# Cube-Panel.net
KiCad netlist of a schematic drawn in EAGLE
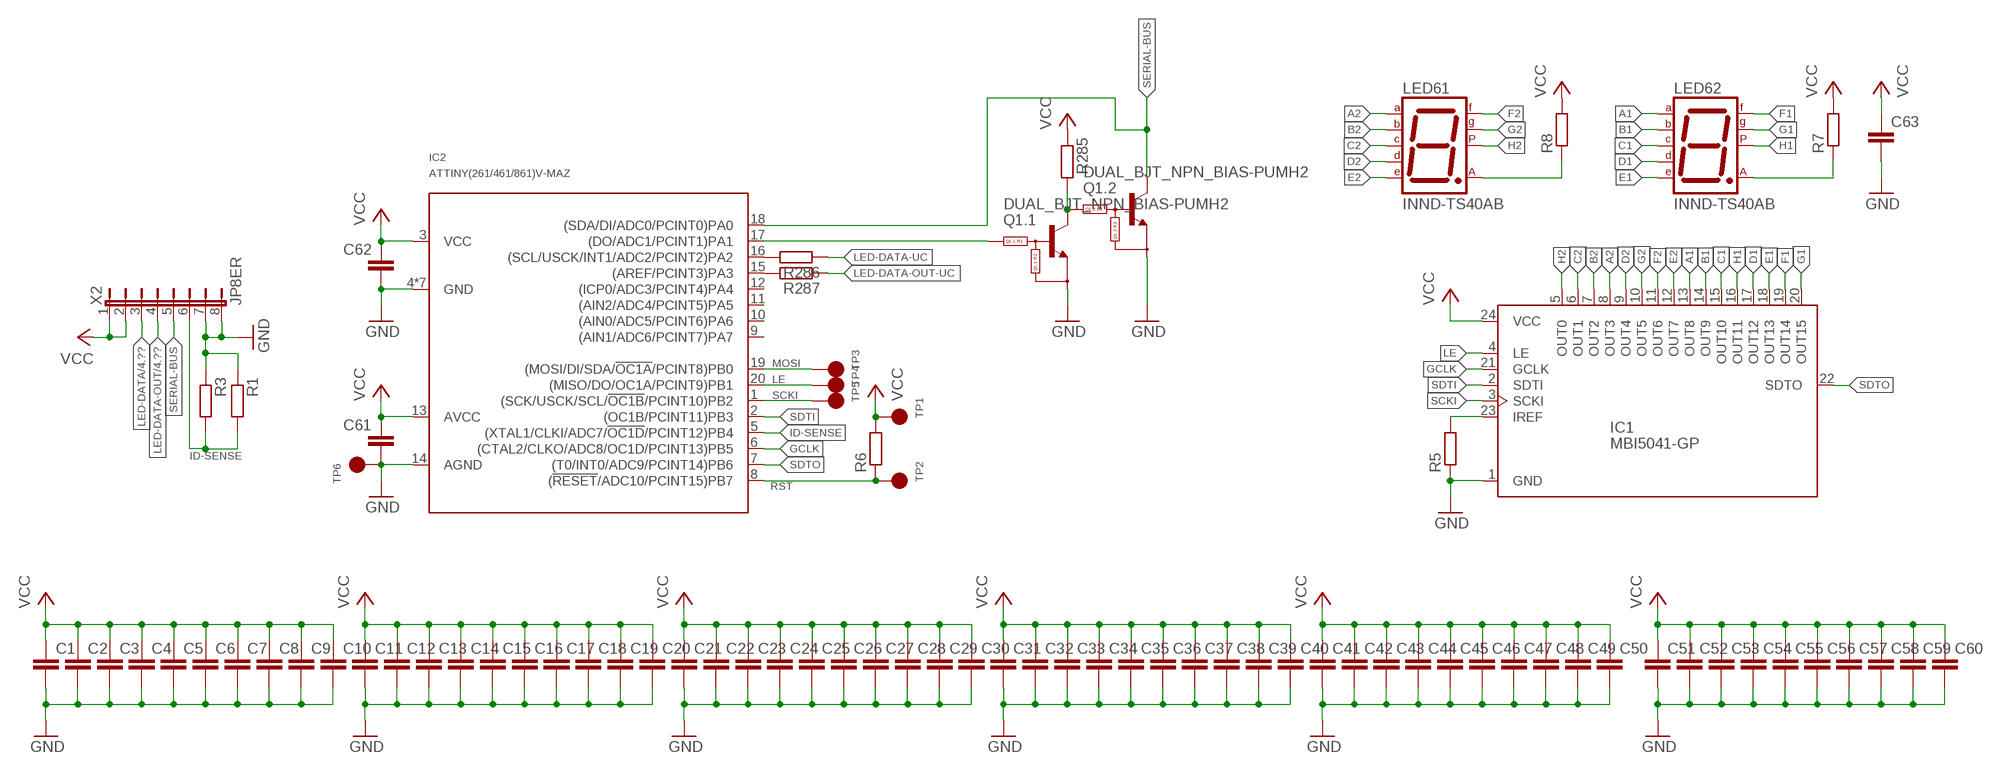
[diagram p0: schematic, sheet 1]
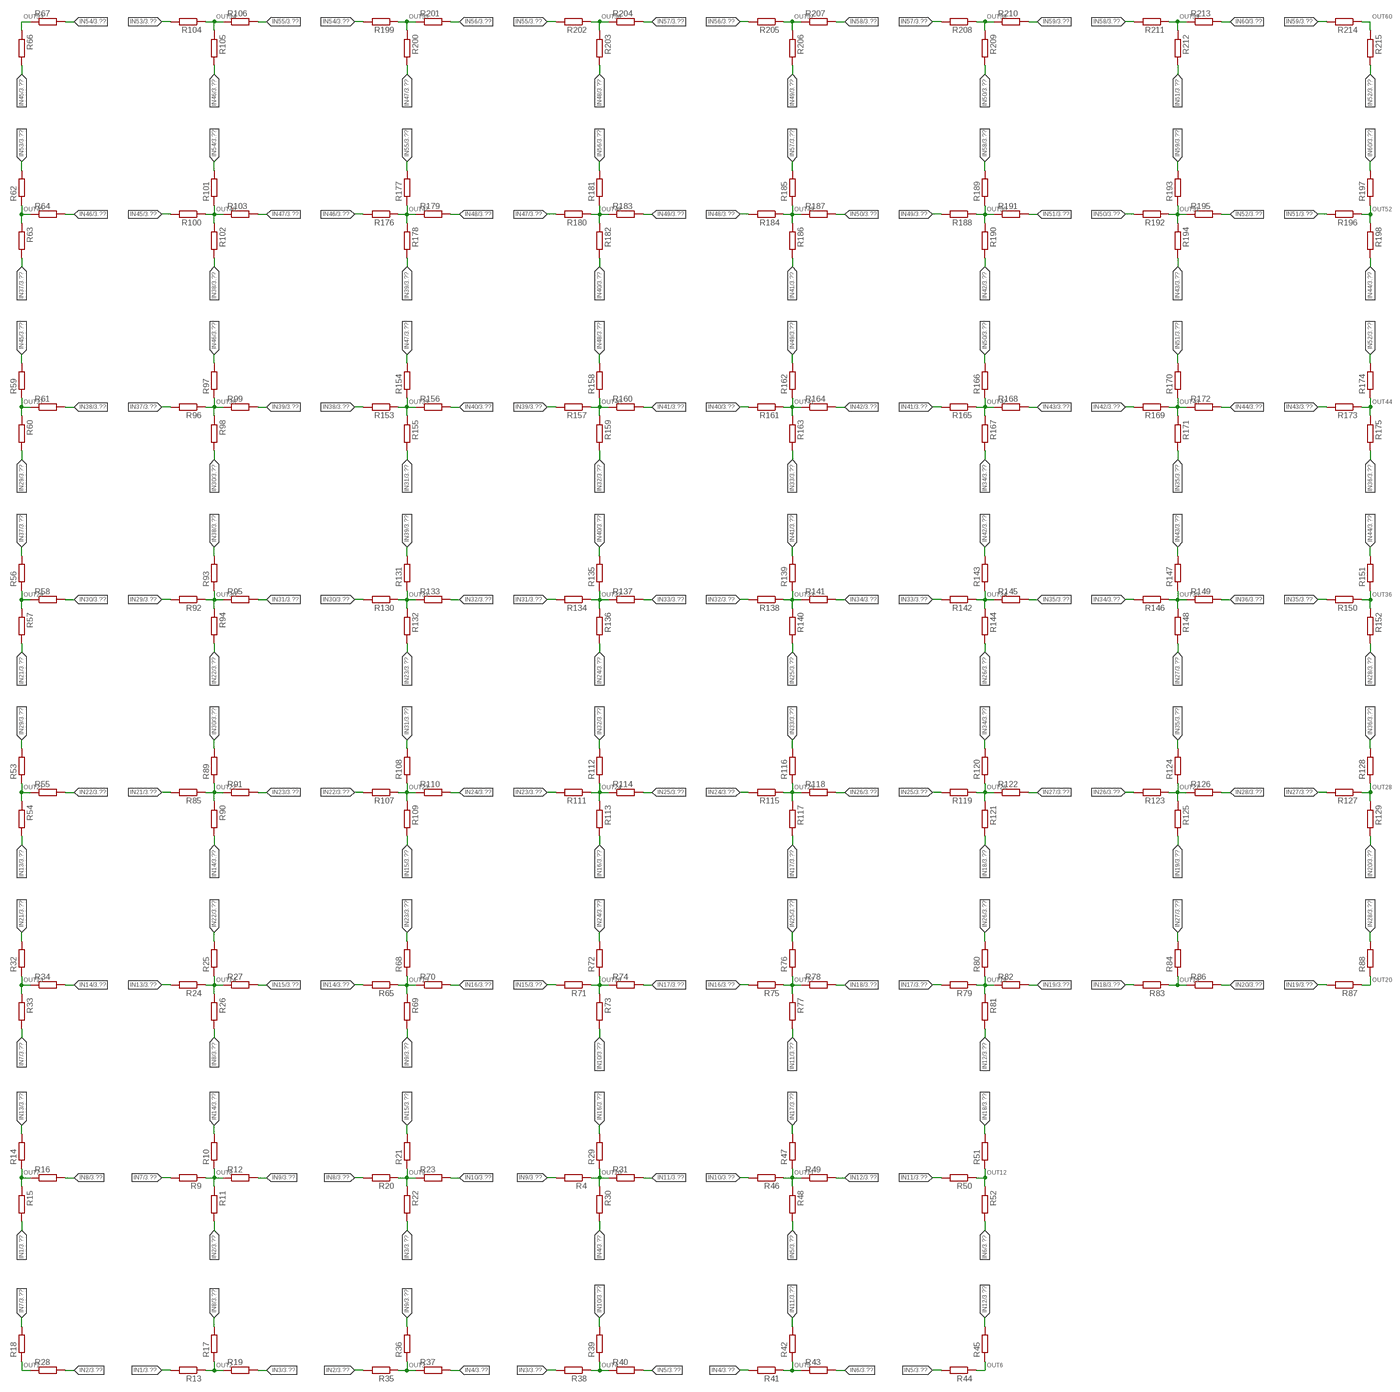
[diagram p1: schematic, sheet 2, overview]
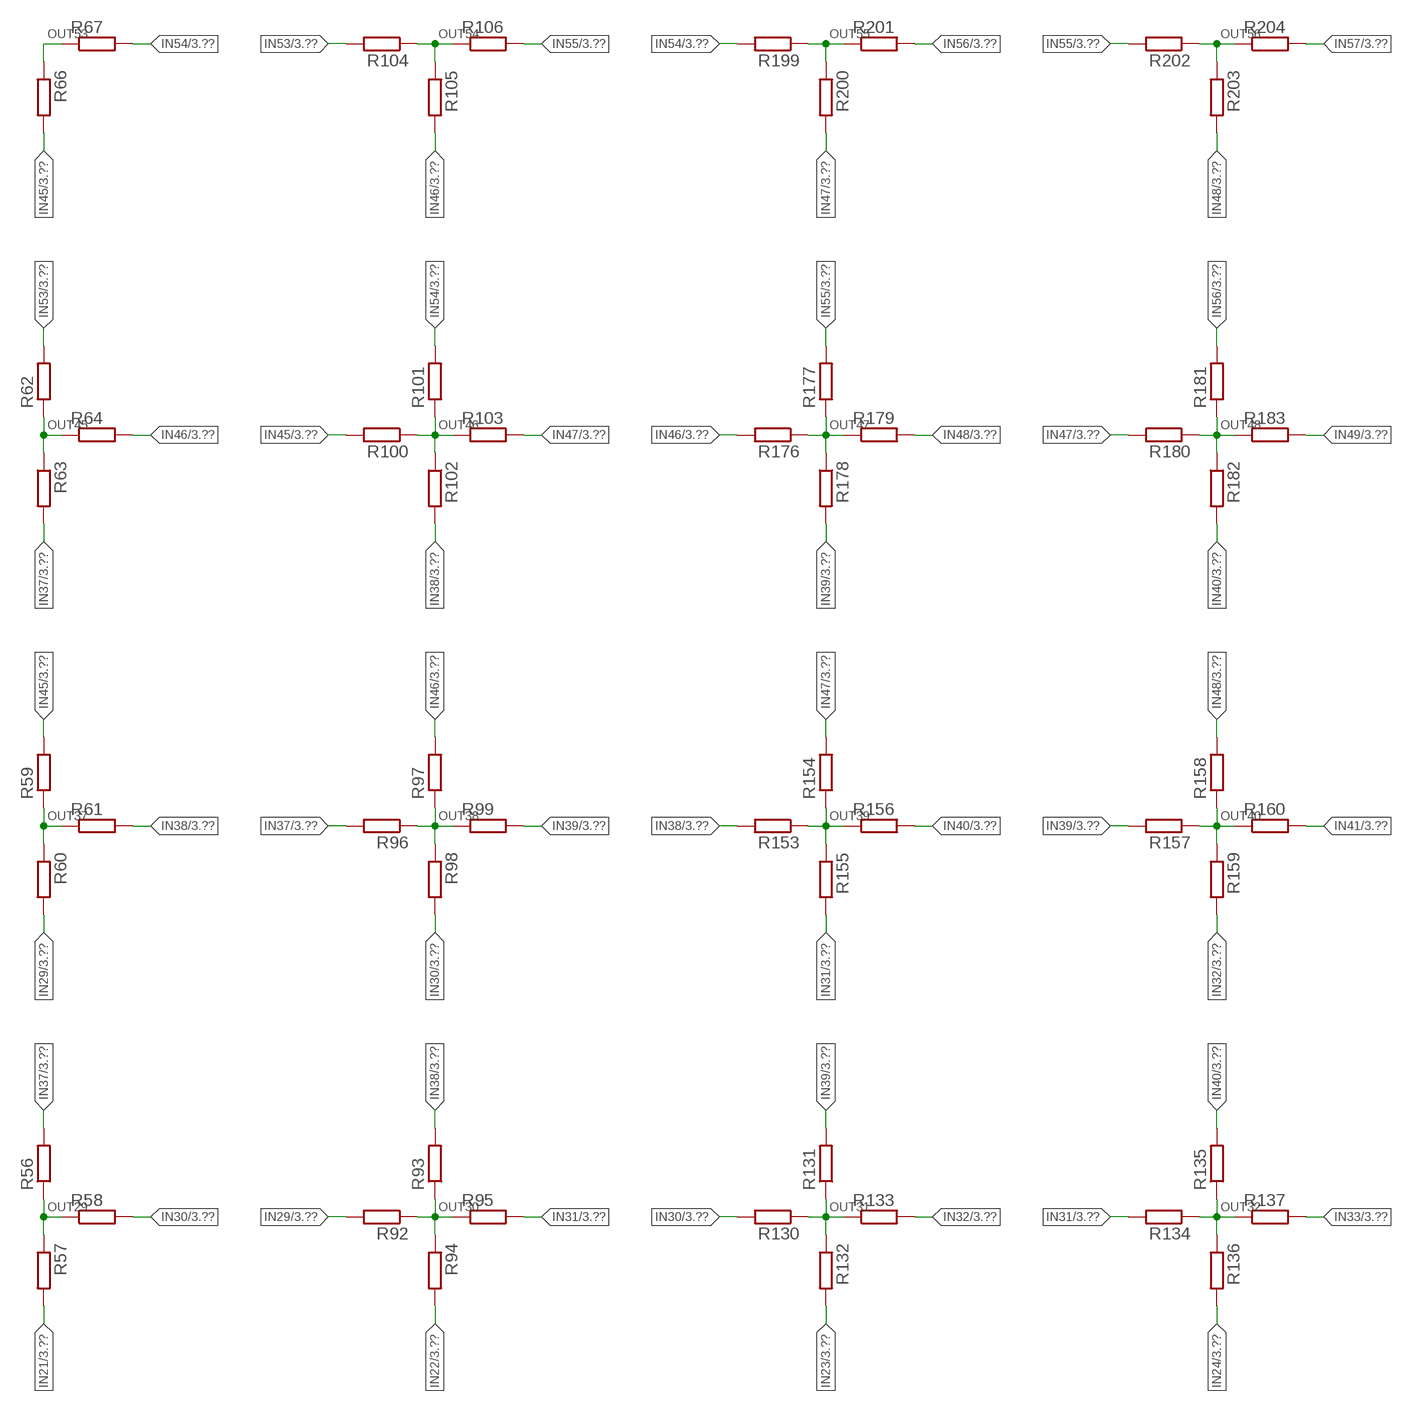
[diagram p2: schematic, sheet 2, part 1 of 4]
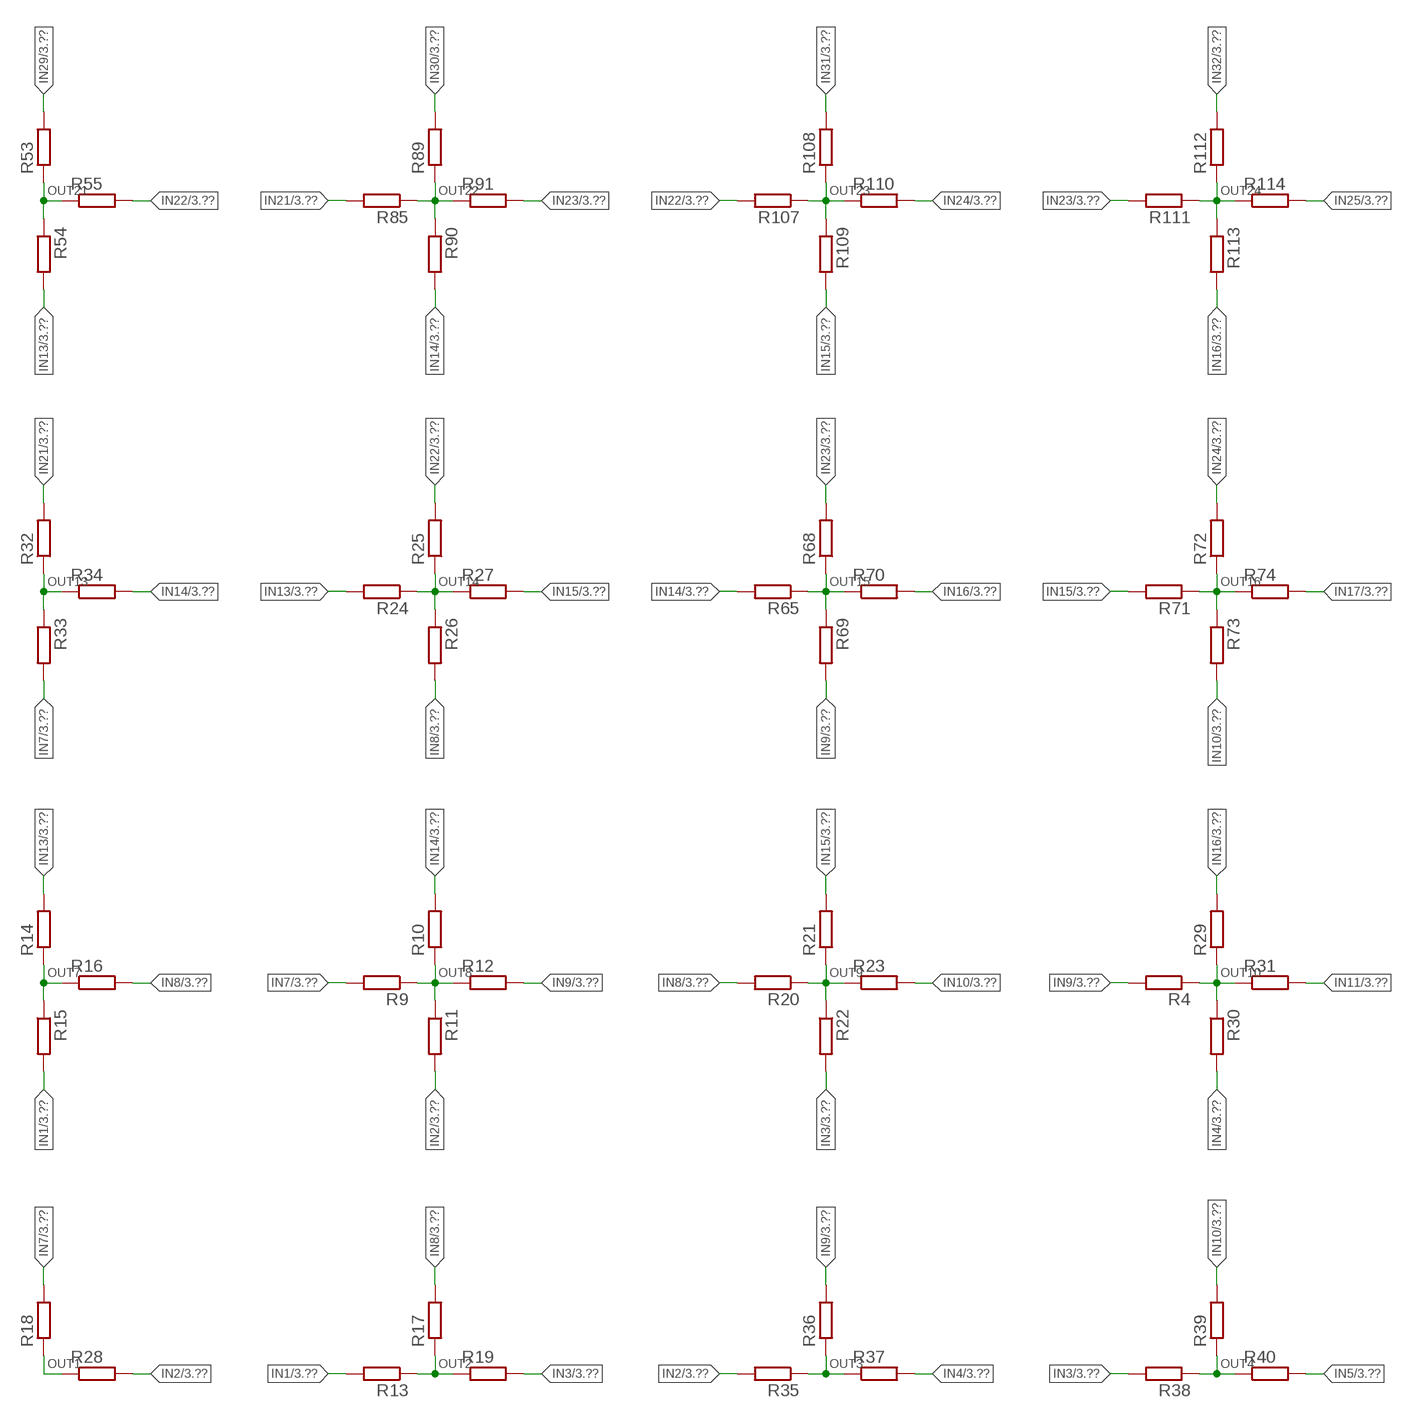
[diagram p3: schematic, sheet 2, part 2 of 4]
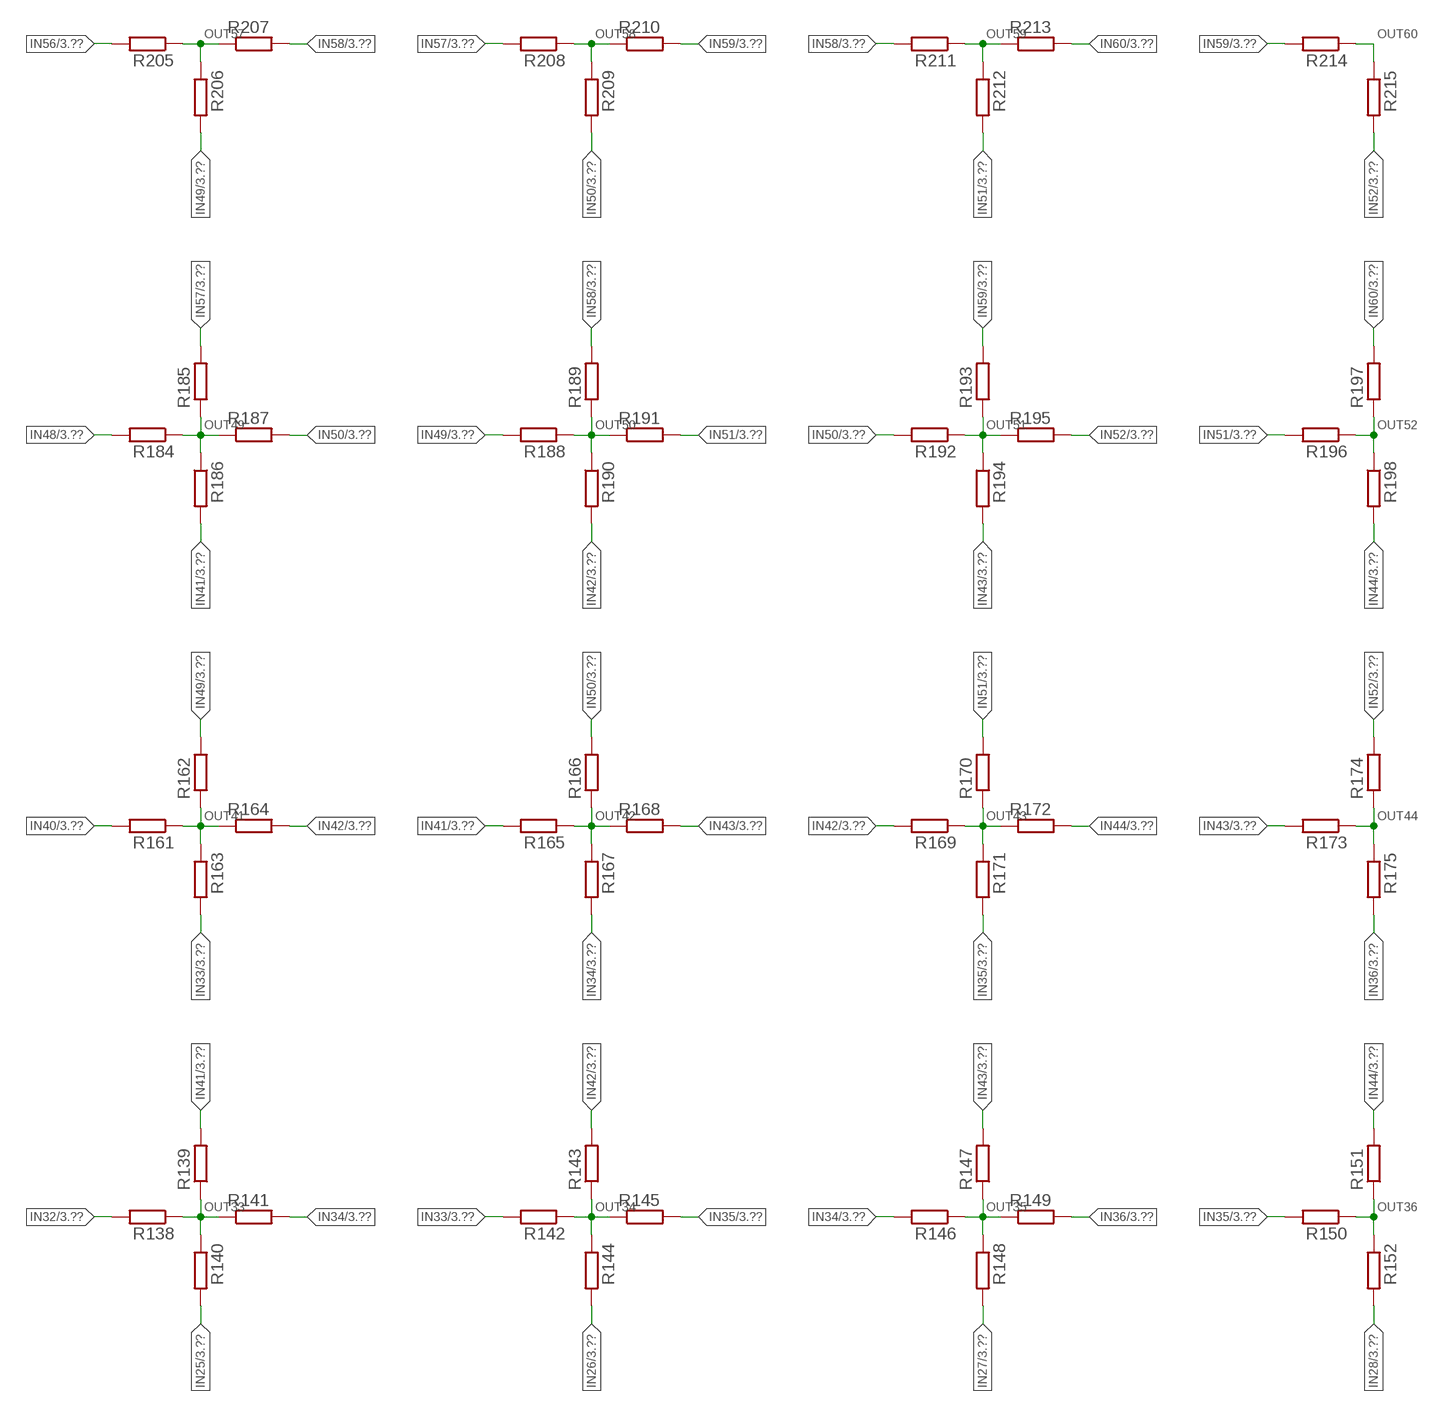
[diagram p4: schematic, sheet 2, part 3 of 4]
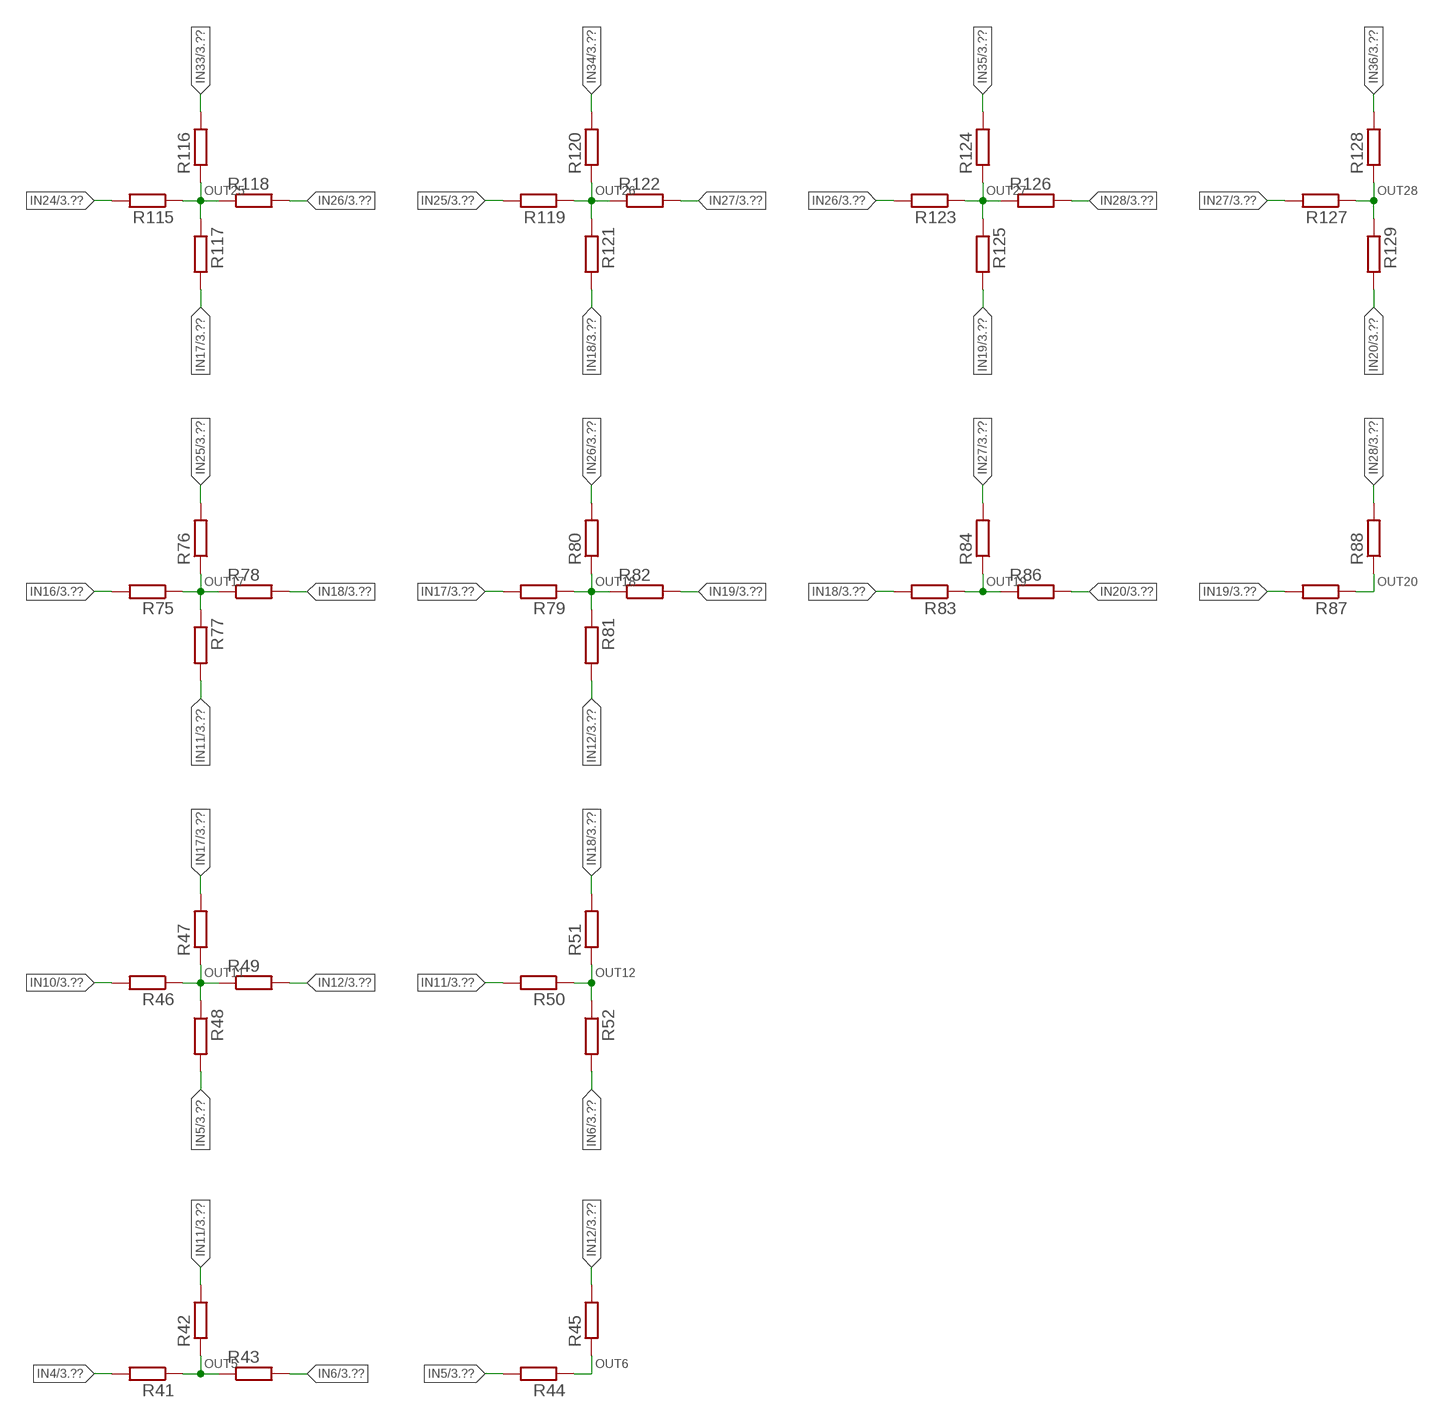
[diagram p5: schematic, sheet 2, part 4 of 4]
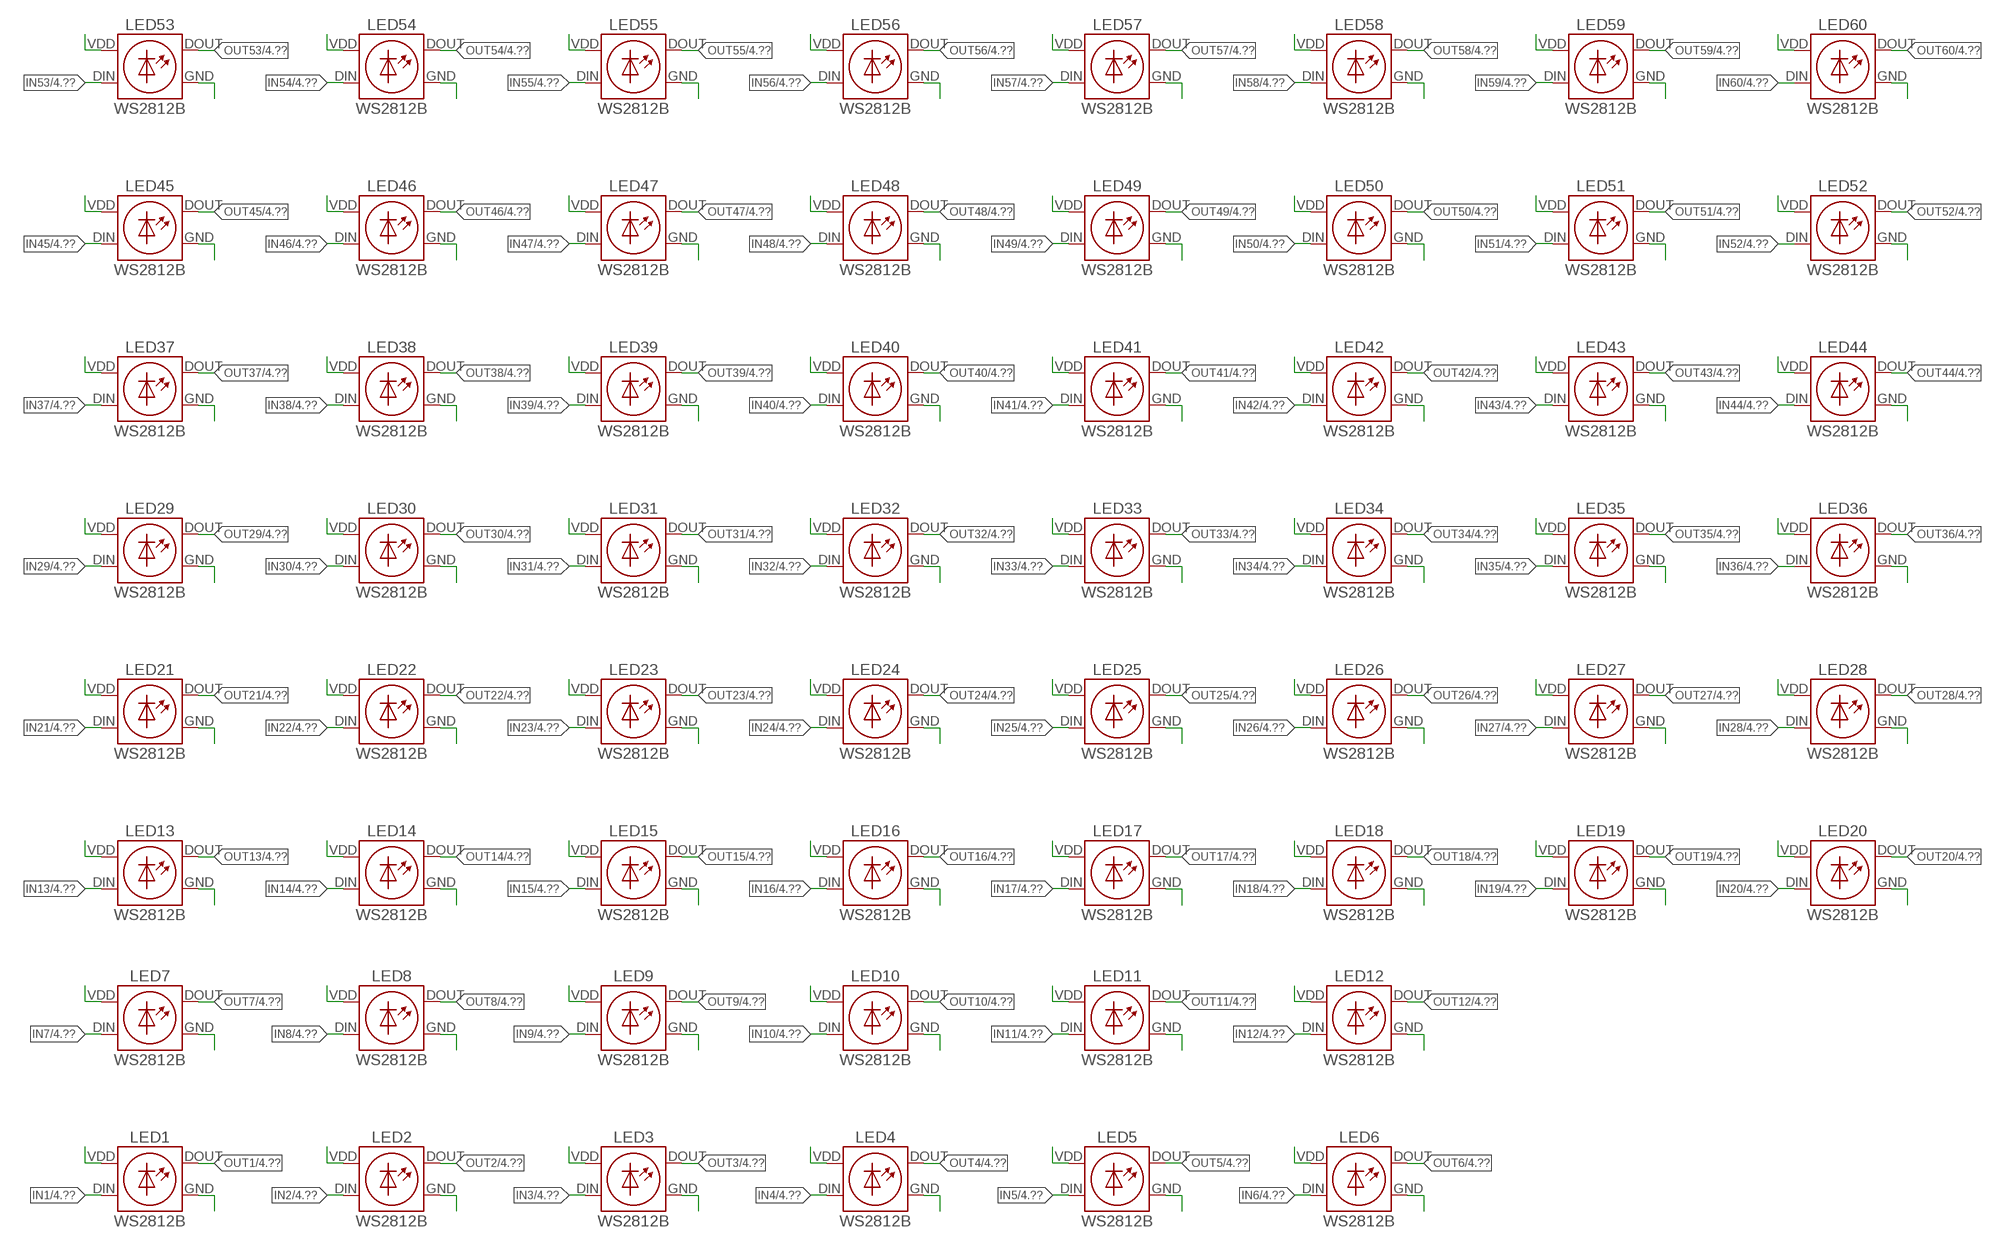
[diagram p6: schematic, sheet 3]
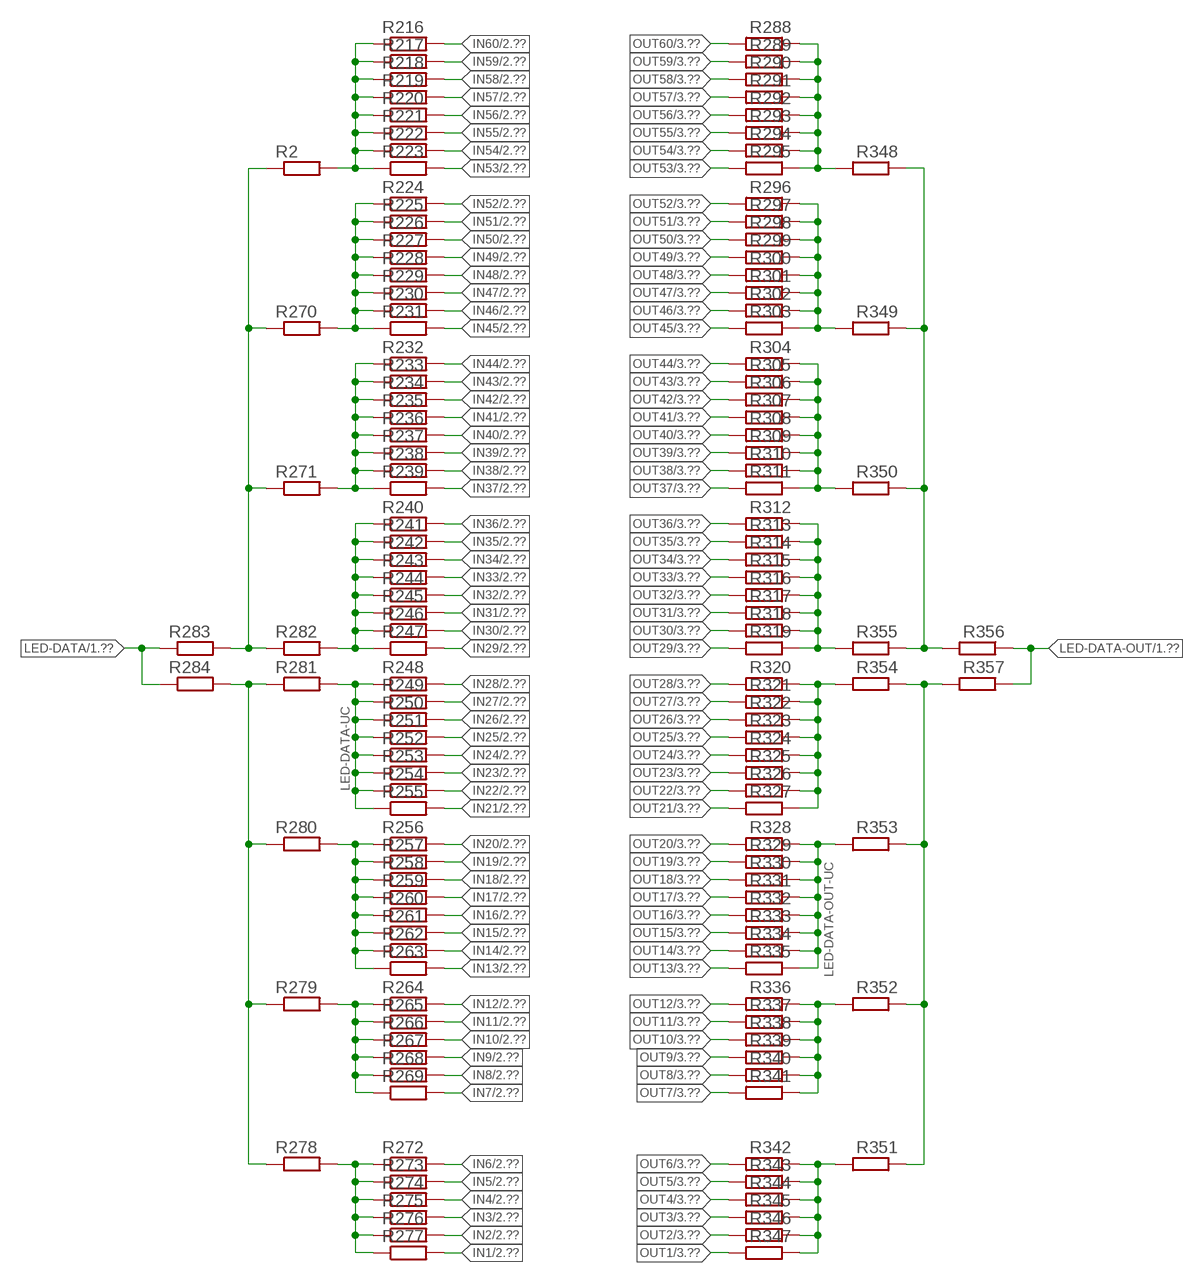
[diagram p7: schematic, sheet 4]

(export (version "E")
  (design (tool "Eeschema 10.0.6"))
  (components
    (comp (ref "R4")
      (value "WIDERSTAND-0603")
      (footprint "eagle-import:0603")
      (libsource (lib "eagle-import") (part "WIDERSTAND-0603"))
    )
    (comp (ref "R9")
      (value "WIDERSTAND-0603")
      (footprint "eagle-import:0603")
      (libsource (lib "eagle-import") (part "WIDERSTAND-0603"))
    )
    (comp (ref "R10")
      (value "WIDERSTAND-0603")
      (footprint "eagle-import:0603")
      (libsource (lib "eagle-import") (part "WIDERSTAND-0603"))
    )
    (comp (ref "R11")
      (value "WIDERSTAND-0603")
      (footprint "eagle-import:0603")
      (libsource (lib "eagle-import") (part "WIDERSTAND-0603"))
    )
    (comp (ref "R12")
      (value "WIDERSTAND-0603")
      (footprint "eagle-import:0603")
      (libsource (lib "eagle-import") (part "WIDERSTAND-0603"))
    )
    (comp (ref "R13")
      (value "WIDERSTAND-0603")
      (footprint "eagle-import:0603")
      (libsource (lib "eagle-import") (part "WIDERSTAND-0603"))
    )
    (comp (ref "R14")
      (value "WIDERSTAND-0603")
      (footprint "eagle-import:0603")
      (libsource (lib "eagle-import") (part "WIDERSTAND-0603"))
    )
    (comp (ref "R15")
      (value "WIDERSTAND-0603")
      (footprint "eagle-import:0603")
      (libsource (lib "eagle-import") (part "WIDERSTAND-0603"))
    )
    (comp (ref "R16")
      (value "WIDERSTAND-0603")
      (footprint "eagle-import:0603")
      (libsource (lib "eagle-import") (part "WIDERSTAND-0603"))
    )
    (comp (ref "R17")
      (value "WIDERSTAND-0603")
      (footprint "eagle-import:0603")
      (libsource (lib "eagle-import") (part "WIDERSTAND-0603"))
    )
    (comp (ref "R18")
      (value "WIDERSTAND-0603")
      (footprint "eagle-import:0603")
      (libsource (lib "eagle-import") (part "WIDERSTAND-0603"))
    )
    (comp (ref "R19")
      (value "WIDERSTAND-0603")
      (footprint "eagle-import:0603")
      (libsource (lib "eagle-import") (part "WIDERSTAND-0603"))
    )
    (comp (ref "R20")
      (value "WIDERSTAND-0603")
      (footprint "eagle-import:0603")
      (libsource (lib "eagle-import") (part "WIDERSTAND-0603"))
    )
    (comp (ref "R21")
      (value "WIDERSTAND-0603")
      (footprint "eagle-import:0603")
      (libsource (lib "eagle-import") (part "WIDERSTAND-0603"))
    )
    (comp (ref "R22")
      (value "WIDERSTAND-0603")
      (footprint "eagle-import:0603")
      (libsource (lib "eagle-import") (part "WIDERSTAND-0603"))
    )
    (comp (ref "R23")
      (value "WIDERSTAND-0603")
      (footprint "eagle-import:0603")
      (libsource (lib "eagle-import") (part "WIDERSTAND-0603"))
    )
    (comp (ref "R24")
      (value "WIDERSTAND-0603")
      (footprint "eagle-import:0603")
      (libsource (lib "eagle-import") (part "WIDERSTAND-0603"))
    )
    (comp (ref "R25")
      (value "WIDERSTAND-0603")
      (footprint "eagle-import:0603")
      (libsource (lib "eagle-import") (part "WIDERSTAND-0603"))
    )
    (comp (ref "R26")
      (value "WIDERSTAND-0603")
      (footprint "eagle-import:0603")
      (libsource (lib "eagle-import") (part "WIDERSTAND-0603"))
    )
    (comp (ref "R27")
      (value "WIDERSTAND-0603")
      (footprint "eagle-import:0603")
      (libsource (lib "eagle-import") (part "WIDERSTAND-0603"))
    )
    (comp (ref "R28")
      (value "WIDERSTAND-0603")
      (footprint "eagle-import:0603")
      (libsource (lib "eagle-import") (part "WIDERSTAND-0603"))
    )
    (comp (ref "R29")
      (value "WIDERSTAND-0603")
      (footprint "eagle-import:0603")
      (libsource (lib "eagle-import") (part "WIDERSTAND-0603"))
    )
    (comp (ref "R30")
      (value "WIDERSTAND-0603")
      (footprint "eagle-import:0603")
      (libsource (lib "eagle-import") (part "WIDERSTAND-0603"))
    )
    (comp (ref "R31")
      (value "WIDERSTAND-0603")
      (footprint "eagle-import:0603")
      (libsource (lib "eagle-import") (part "WIDERSTAND-0603"))
    )
    (comp (ref "R32")
      (value "WIDERSTAND-0603")
      (footprint "eagle-import:0603")
      (libsource (lib "eagle-import") (part "WIDERSTAND-0603"))
    )
    (comp (ref "R33")
      (value "WIDERSTAND-0603")
      (footprint "eagle-import:0603")
      (libsource (lib "eagle-import") (part "WIDERSTAND-0603"))
    )
    (comp (ref "R34")
      (value "WIDERSTAND-0603")
      (footprint "eagle-import:0603")
      (libsource (lib "eagle-import") (part "WIDERSTAND-0603"))
    )
    (comp (ref "R35")
      (value "WIDERSTAND-0603")
      (footprint "eagle-import:0603")
      (libsource (lib "eagle-import") (part "WIDERSTAND-0603"))
    )
    (comp (ref "R36")
      (value "WIDERSTAND-0603")
      (footprint "eagle-import:0603")
      (libsource (lib "eagle-import") (part "WIDERSTAND-0603"))
    )
    (comp (ref "R37")
      (value "WIDERSTAND-0603")
      (footprint "eagle-import:0603")
      (libsource (lib "eagle-import") (part "WIDERSTAND-0603"))
    )
    (comp (ref "R38")
      (value "WIDERSTAND-0603")
      (footprint "eagle-import:0603")
      (libsource (lib "eagle-import") (part "WIDERSTAND-0603"))
    )
    (comp (ref "R39")
      (value "WIDERSTAND-0603")
      (footprint "eagle-import:0603")
      (libsource (lib "eagle-import") (part "WIDERSTAND-0603"))
    )
    (comp (ref "R40")
      (value "WIDERSTAND-0603")
      (footprint "eagle-import:0603")
      (libsource (lib "eagle-import") (part "WIDERSTAND-0603"))
    )
    (comp (ref "R41")
      (value "WIDERSTAND-0603")
      (footprint "eagle-import:0603")
      (libsource (lib "eagle-import") (part "WIDERSTAND-0603"))
    )
    (comp (ref "R42")
      (value "WIDERSTAND-0603")
      (footprint "eagle-import:0603")
      (libsource (lib "eagle-import") (part "WIDERSTAND-0603"))
    )
    (comp (ref "R43")
      (value "WIDERSTAND-0603")
      (footprint "eagle-import:0603")
      (libsource (lib "eagle-import") (part "WIDERSTAND-0603"))
    )
    (comp (ref "R44")
      (value "WIDERSTAND-0603")
      (footprint "eagle-import:0603")
      (libsource (lib "eagle-import") (part "WIDERSTAND-0603"))
    )
    (comp (ref "R45")
      (value "WIDERSTAND-0603")
      (footprint "eagle-import:0603")
      (libsource (lib "eagle-import") (part "WIDERSTAND-0603"))
    )
    (comp (ref "R46")
      (value "WIDERSTAND-0603")
      (footprint "eagle-import:0603")
      (libsource (lib "eagle-import") (part "WIDERSTAND-0603"))
    )
    (comp (ref "R47")
      (value "WIDERSTAND-0603")
      (footprint "eagle-import:0603")
      (libsource (lib "eagle-import") (part "WIDERSTAND-0603"))
    )
    (comp (ref "R48")
      (value "WIDERSTAND-0603")
      (footprint "eagle-import:0603")
      (libsource (lib "eagle-import") (part "WIDERSTAND-0603"))
    )
    (comp (ref "R49")
      (value "WIDERSTAND-0603")
      (footprint "eagle-import:0603")
      (libsource (lib "eagle-import") (part "WIDERSTAND-0603"))
    )
    (comp (ref "R50")
      (value "WIDERSTAND-0603")
      (footprint "eagle-import:0603")
      (libsource (lib "eagle-import") (part "WIDERSTAND-0603"))
    )
    (comp (ref "R51")
      (value "WIDERSTAND-0603")
      (footprint "eagle-import:0603")
      (libsource (lib "eagle-import") (part "WIDERSTAND-0603"))
    )
    (comp (ref "R52")
      (value "WIDERSTAND-0603")
      (footprint "eagle-import:0603")
      (libsource (lib "eagle-import") (part "WIDERSTAND-0603"))
    )
    (comp (ref "R53")
      (value "WIDERSTAND-0603")
      (footprint "eagle-import:0603")
      (libsource (lib "eagle-import") (part "WIDERSTAND-0603"))
    )
    (comp (ref "R54")
      (value "WIDERSTAND-0603")
      (footprint "eagle-import:0603")
      (libsource (lib "eagle-import") (part "WIDERSTAND-0603"))
    )
    (comp (ref "R55")
      (value "WIDERSTAND-0603")
      (footprint "eagle-import:0603")
      (libsource (lib "eagle-import") (part "WIDERSTAND-0603"))
    )
    (comp (ref "R56")
      (value "WIDERSTAND-0603")
      (footprint "eagle-import:0603")
      (libsource (lib "eagle-import") (part "WIDERSTAND-0603"))
    )
    (comp (ref "R57")
      (value "WIDERSTAND-0603")
      (footprint "eagle-import:0603")
      (libsource (lib "eagle-import") (part "WIDERSTAND-0603"))
    )
    (comp (ref "R58")
      (value "WIDERSTAND-0603")
      (footprint "eagle-import:0603")
      (libsource (lib "eagle-import") (part "WIDERSTAND-0603"))
    )
    (comp (ref "R59")
      (value "WIDERSTAND-0603")
      (footprint "eagle-import:0603")
      (libsource (lib "eagle-import") (part "WIDERSTAND-0603"))
    )
    (comp (ref "R60")
      (value "WIDERSTAND-0603")
      (footprint "eagle-import:0603")
      (libsource (lib "eagle-import") (part "WIDERSTAND-0603"))
    )
    (comp (ref "R61")
      (value "WIDERSTAND-0603")
      (footprint "eagle-import:0603")
      (libsource (lib "eagle-import") (part "WIDERSTAND-0603"))
    )
    (comp (ref "R62")
      (value "WIDERSTAND-0603")
      (footprint "eagle-import:0603")
      (libsource (lib "eagle-import") (part "WIDERSTAND-0603"))
    )
    (comp (ref "R63")
      (value "WIDERSTAND-0603")
      (footprint "eagle-import:0603")
      (libsource (lib "eagle-import") (part "WIDERSTAND-0603"))
    )
    (comp (ref "R64")
      (value "WIDERSTAND-0603")
      (footprint "eagle-import:0603")
      (libsource (lib "eagle-import") (part "WIDERSTAND-0603"))
    )
    (comp (ref "R65")
      (value "WIDERSTAND-0603")
      (footprint "eagle-import:0603")
      (libsource (lib "eagle-import") (part "WIDERSTAND-0603"))
    )
    (comp (ref "R66")
      (value "WIDERSTAND-0603")
      (footprint "eagle-import:0603")
      (libsource (lib "eagle-import") (part "WIDERSTAND-0603"))
    )
    (comp (ref "R67")
      (value "WIDERSTAND-0603")
      (footprint "eagle-import:0603")
      (libsource (lib "eagle-import") (part "WIDERSTAND-0603"))
    )
    (comp (ref "R68")
      (value "WIDERSTAND-0603")
      (footprint "eagle-import:0603")
      (libsource (lib "eagle-import") (part "WIDERSTAND-0603"))
    )
    (comp (ref "R69")
      (value "WIDERSTAND-0603")
      (footprint "eagle-import:0603")
      (libsource (lib "eagle-import") (part "WIDERSTAND-0603"))
    )
    (comp (ref "R70")
      (value "WIDERSTAND-0603")
      (footprint "eagle-import:0603")
      (libsource (lib "eagle-import") (part "WIDERSTAND-0603"))
    )
    (comp (ref "R71")
      (value "WIDERSTAND-0603")
      (footprint "eagle-import:0603")
      (libsource (lib "eagle-import") (part "WIDERSTAND-0603"))
    )
    (comp (ref "R72")
      (value "WIDERSTAND-0603")
      (footprint "eagle-import:0603")
      (libsource (lib "eagle-import") (part "WIDERSTAND-0603"))
    )
    (comp (ref "R73")
      (value "WIDERSTAND-0603")
      (footprint "eagle-import:0603")
      (libsource (lib "eagle-import") (part "WIDERSTAND-0603"))
    )
    (comp (ref "R74")
      (value "WIDERSTAND-0603")
      (footprint "eagle-import:0603")
      (libsource (lib "eagle-import") (part "WIDERSTAND-0603"))
    )
    (comp (ref "R75")
      (value "WIDERSTAND-0603")
      (footprint "eagle-import:0603")
      (libsource (lib "eagle-import") (part "WIDERSTAND-0603"))
    )
    (comp (ref "R76")
      (value "WIDERSTAND-0603")
      (footprint "eagle-import:0603")
      (libsource (lib "eagle-import") (part "WIDERSTAND-0603"))
    )
    (comp (ref "R77")
      (value "WIDERSTAND-0603")
      (footprint "eagle-import:0603")
      (libsource (lib "eagle-import") (part "WIDERSTAND-0603"))
    )
    (comp (ref "R78")
      (value "WIDERSTAND-0603")
      (footprint "eagle-import:0603")
      (libsource (lib "eagle-import") (part "WIDERSTAND-0603"))
    )
    (comp (ref "R79")
      (value "WIDERSTAND-0603")
      (footprint "eagle-import:0603")
      (libsource (lib "eagle-import") (part "WIDERSTAND-0603"))
    )
    (comp (ref "R80")
      (value "WIDERSTAND-0603")
      (footprint "eagle-import:0603")
      (libsource (lib "eagle-import") (part "WIDERSTAND-0603"))
    )
    (comp (ref "R81")
      (value "WIDERSTAND-0603")
      (footprint "eagle-import:0603")
      (libsource (lib "eagle-import") (part "WIDERSTAND-0603"))
    )
    (comp (ref "R82")
      (value "WIDERSTAND-0603")
      (footprint "eagle-import:0603")
      (libsource (lib "eagle-import") (part "WIDERSTAND-0603"))
    )
    (comp (ref "R83")
      (value "WIDERSTAND-0603")
      (footprint "eagle-import:0603")
      (libsource (lib "eagle-import") (part "WIDERSTAND-0603"))
    )
    (comp (ref "R84")
      (value "WIDERSTAND-0603")
      (footprint "eagle-import:0603")
      (libsource (lib "eagle-import") (part "WIDERSTAND-0603"))
    )
    (comp (ref "R85")
      (value "WIDERSTAND-0603")
      (footprint "eagle-import:0603")
      (libsource (lib "eagle-import") (part "WIDERSTAND-0603"))
    )
    (comp (ref "R86")
      (value "WIDERSTAND-0603")
      (footprint "eagle-import:0603")
      (libsource (lib "eagle-import") (part "WIDERSTAND-0603"))
    )
    (comp (ref "R87")
      (value "WIDERSTAND-0603")
      (footprint "eagle-import:0603")
      (libsource (lib "eagle-import") (part "WIDERSTAND-0603"))
    )
    (comp (ref "R88")
      (value "WIDERSTAND-0603")
      (footprint "eagle-import:0603")
      (libsource (lib "eagle-import") (part "WIDERSTAND-0603"))
    )
    (comp (ref "R89")
      (value "WIDERSTAND-0603")
      (footprint "eagle-import:0603")
      (libsource (lib "eagle-import") (part "WIDERSTAND-0603"))
    )
    (comp (ref "R90")
      (value "WIDERSTAND-0603")
      (footprint "eagle-import:0603")
      (libsource (lib "eagle-import") (part "WIDERSTAND-0603"))
    )
    (comp (ref "R91")
      (value "WIDERSTAND-0603")
      (footprint "eagle-import:0603")
      (libsource (lib "eagle-import") (part "WIDERSTAND-0603"))
    )
    (comp (ref "R92")
      (value "WIDERSTAND-0603")
      (footprint "eagle-import:0603")
      (libsource (lib "eagle-import") (part "WIDERSTAND-0603"))
    )
    (comp (ref "R93")
      (value "WIDERSTAND-0603")
      (footprint "eagle-import:0603")
      (libsource (lib "eagle-import") (part "WIDERSTAND-0603"))
    )
    (comp (ref "R94")
      (value "WIDERSTAND-0603")
      (footprint "eagle-import:0603")
      (libsource (lib "eagle-import") (part "WIDERSTAND-0603"))
    )
    (comp (ref "R95")
      (value "WIDERSTAND-0603")
      (footprint "eagle-import:0603")
      (libsource (lib "eagle-import") (part "WIDERSTAND-0603"))
    )
    (comp (ref "R96")
      (value "WIDERSTAND-0603")
      (footprint "eagle-import:0603")
      (libsource (lib "eagle-import") (part "WIDERSTAND-0603"))
    )
    (comp (ref "R97")
      (value "WIDERSTAND-0603")
      (footprint "eagle-import:0603")
      (libsource (lib "eagle-import") (part "WIDERSTAND-0603"))
    )
    (comp (ref "R98")
      (value "WIDERSTAND-0603")
      (footprint "eagle-import:0603")
      (libsource (lib "eagle-import") (part "WIDERSTAND-0603"))
    )
    (comp (ref "R99")
      (value "WIDERSTAND-0603")
      (footprint "eagle-import:0603")
      (libsource (lib "eagle-import") (part "WIDERSTAND-0603"))
    )
    (comp (ref "R100")
      (value "WIDERSTAND-0603")
      (footprint "eagle-import:0603")
      (libsource (lib "eagle-import") (part "WIDERSTAND-0603"))
    )
    (comp (ref "R101")
      (value "WIDERSTAND-0603")
      (footprint "eagle-import:0603")
      (libsource (lib "eagle-import") (part "WIDERSTAND-0603"))
    )
    (comp (ref "R102")
      (value "WIDERSTAND-0603")
      (footprint "eagle-import:0603")
      (libsource (lib "eagle-import") (part "WIDERSTAND-0603"))
    )
    (comp (ref "R103")
      (value "WIDERSTAND-0603")
      (footprint "eagle-import:0603")
      (libsource (lib "eagle-import") (part "WIDERSTAND-0603"))
    )
    (comp (ref "R104")
      (value "WIDERSTAND-0603")
      (footprint "eagle-import:0603")
      (libsource (lib "eagle-import") (part "WIDERSTAND-0603"))
    )
    (comp (ref "R105")
      (value "WIDERSTAND-0603")
      (footprint "eagle-import:0603")
      (libsource (lib "eagle-import") (part "WIDERSTAND-0603"))
    )
    (comp (ref "R106")
      (value "WIDERSTAND-0603")
      (footprint "eagle-import:0603")
      (libsource (lib "eagle-import") (part "WIDERSTAND-0603"))
    )
    (comp (ref "R107")
      (value "WIDERSTAND-0603")
      (footprint "eagle-import:0603")
      (libsource (lib "eagle-import") (part "WIDERSTAND-0603"))
    )
    (comp (ref "R108")
      (value "WIDERSTAND-0603")
      (footprint "eagle-import:0603")
      (libsource (lib "eagle-import") (part "WIDERSTAND-0603"))
    )
    (comp (ref "R109")
      (value "WIDERSTAND-0603")
      (footprint "eagle-import:0603")
      (libsource (lib "eagle-import") (part "WIDERSTAND-0603"))
    )
    (comp (ref "R110")
      (value "WIDERSTAND-0603")
      (footprint "eagle-import:0603")
      (libsource (lib "eagle-import") (part "WIDERSTAND-0603"))
    )
    (comp (ref "R111")
      (value "WIDERSTAND-0603")
      (footprint "eagle-import:0603")
      (libsource (lib "eagle-import") (part "WIDERSTAND-0603"))
    )
    (comp (ref "R112")
      (value "WIDERSTAND-0603")
      (footprint "eagle-import:0603")
      (libsource (lib "eagle-import") (part "WIDERSTAND-0603"))
    )
    (comp (ref "R113")
      (value "WIDERSTAND-0603")
      (footprint "eagle-import:0603")
      (libsource (lib "eagle-import") (part "WIDERSTAND-0603"))
    )
    (comp (ref "R114")
      (value "WIDERSTAND-0603")
      (footprint "eagle-import:0603")
      (libsource (lib "eagle-import") (part "WIDERSTAND-0603"))
    )
    (comp (ref "R115")
      (value "WIDERSTAND-0603")
      (footprint "eagle-import:0603")
      (libsource (lib "eagle-import") (part "WIDERSTAND-0603"))
    )
    (comp (ref "R116")
      (value "WIDERSTAND-0603")
      (footprint "eagle-import:0603")
      (libsource (lib "eagle-import") (part "WIDERSTAND-0603"))
    )
    (comp (ref "R117")
      (value "WIDERSTAND-0603")
      (footprint "eagle-import:0603")
      (libsource (lib "eagle-import") (part "WIDERSTAND-0603"))
    )
    (comp (ref "R118")
      (value "WIDERSTAND-0603")
      (footprint "eagle-import:0603")
      (libsource (lib "eagle-import") (part "WIDERSTAND-0603"))
    )
    (comp (ref "R119")
      (value "WIDERSTAND-0603")
      (footprint "eagle-import:0603")
      (libsource (lib "eagle-import") (part "WIDERSTAND-0603"))
    )
    (comp (ref "R120")
      (value "WIDERSTAND-0603")
      (footprint "eagle-import:0603")
      (libsource (lib "eagle-import") (part "WIDERSTAND-0603"))
    )
    (comp (ref "R121")
      (value "WIDERSTAND-0603")
      (footprint "eagle-import:0603")
      (libsource (lib "eagle-import") (part "WIDERSTAND-0603"))
    )
    (comp (ref "R122")
      (value "WIDERSTAND-0603")
      (footprint "eagle-import:0603")
      (libsource (lib "eagle-import") (part "WIDERSTAND-0603"))
    )
    (comp (ref "R123")
      (value "WIDERSTAND-0603")
      (footprint "eagle-import:0603")
      (libsource (lib "eagle-import") (part "WIDERSTAND-0603"))
    )
    (comp (ref "R124")
      (value "WIDERSTAND-0603")
      (footprint "eagle-import:0603")
      (libsource (lib "eagle-import") (part "WIDERSTAND-0603"))
    )
    (comp (ref "R125")
      (value "WIDERSTAND-0603")
      (footprint "eagle-import:0603")
      (libsource (lib "eagle-import") (part "WIDERSTAND-0603"))
    )
    (comp (ref "R126")
      (value "WIDERSTAND-0603")
      (footprint "eagle-import:0603")
      (libsource (lib "eagle-import") (part "WIDERSTAND-0603"))
    )
    (comp (ref "R127")
      (value "WIDERSTAND-0603")
      (footprint "eagle-import:0603")
      (libsource (lib "eagle-import") (part "WIDERSTAND-0603"))
    )
    (comp (ref "R128")
      (value "WIDERSTAND-0603")
      (footprint "eagle-import:0603")
      (libsource (lib "eagle-import") (part "WIDERSTAND-0603"))
    )
    (comp (ref "R129")
      (value "WIDERSTAND-0603")
      (footprint "eagle-import:0603")
      (libsource (lib "eagle-import") (part "WIDERSTAND-0603"))
    )
    (comp (ref "R130")
      (value "WIDERSTAND-0603")
      (footprint "eagle-import:0603")
      (libsource (lib "eagle-import") (part "WIDERSTAND-0603"))
    )
    (comp (ref "R131")
      (value "WIDERSTAND-0603")
      (footprint "eagle-import:0603")
      (libsource (lib "eagle-import") (part "WIDERSTAND-0603"))
    )
    (comp (ref "R132")
      (value "WIDERSTAND-0603")
      (footprint "eagle-import:0603")
      (libsource (lib "eagle-import") (part "WIDERSTAND-0603"))
    )
    (comp (ref "R133")
      (value "WIDERSTAND-0603")
      (footprint "eagle-import:0603")
      (libsource (lib "eagle-import") (part "WIDERSTAND-0603"))
    )
    (comp (ref "R134")
      (value "WIDERSTAND-0603")
      (footprint "eagle-import:0603")
      (libsource (lib "eagle-import") (part "WIDERSTAND-0603"))
    )
    (comp (ref "R135")
      (value "WIDERSTAND-0603")
      (footprint "eagle-import:0603")
      (libsource (lib "eagle-import") (part "WIDERSTAND-0603"))
    )
    (comp (ref "R136")
      (value "WIDERSTAND-0603")
      (footprint "eagle-import:0603")
      (libsource (lib "eagle-import") (part "WIDERSTAND-0603"))
    )
    (comp (ref "R137")
      (value "WIDERSTAND-0603")
      (footprint "eagle-import:0603")
      (libsource (lib "eagle-import") (part "WIDERSTAND-0603"))
    )
    (comp (ref "R138")
      (value "WIDERSTAND-0603")
      (footprint "eagle-import:0603")
      (libsource (lib "eagle-import") (part "WIDERSTAND-0603"))
    )
    (comp (ref "R139")
      (value "WIDERSTAND-0603")
      (footprint "eagle-import:0603")
      (libsource (lib "eagle-import") (part "WIDERSTAND-0603"))
    )
    (comp (ref "R140")
      (value "WIDERSTAND-0603")
      (footprint "eagle-import:0603")
      (libsource (lib "eagle-import") (part "WIDERSTAND-0603"))
    )
    (comp (ref "R141")
      (value "WIDERSTAND-0603")
      (footprint "eagle-import:0603")
      (libsource (lib "eagle-import") (part "WIDERSTAND-0603"))
    )
    (comp (ref "R142")
      (value "WIDERSTAND-0603")
      (footprint "eagle-import:0603")
      (libsource (lib "eagle-import") (part "WIDERSTAND-0603"))
    )
    (comp (ref "R143")
      (value "WIDERSTAND-0603")
      (footprint "eagle-import:0603")
      (libsource (lib "eagle-import") (part "WIDERSTAND-0603"))
    )
    (comp (ref "R144")
      (value "WIDERSTAND-0603")
      (footprint "eagle-import:0603")
      (libsource (lib "eagle-import") (part "WIDERSTAND-0603"))
    )
    (comp (ref "R145")
      (value "WIDERSTAND-0603")
      (footprint "eagle-import:0603")
      (libsource (lib "eagle-import") (part "WIDERSTAND-0603"))
    )
    (comp (ref "R146")
      (value "WIDERSTAND-0603")
      (footprint "eagle-import:0603")
      (libsource (lib "eagle-import") (part "WIDERSTAND-0603"))
    )
    (comp (ref "R147")
      (value "WIDERSTAND-0603")
      (footprint "eagle-import:0603")
      (libsource (lib "eagle-import") (part "WIDERSTAND-0603"))
    )
    (comp (ref "R148")
      (value "WIDERSTAND-0603")
      (footprint "eagle-import:0603")
      (libsource (lib "eagle-import") (part "WIDERSTAND-0603"))
    )
    (comp (ref "R149")
      (value "WIDERSTAND-0603")
      (footprint "eagle-import:0603")
      (libsource (lib "eagle-import") (part "WIDERSTAND-0603"))
    )
    (comp (ref "R150")
      (value "WIDERSTAND-0603")
      (footprint "eagle-import:0603")
      (libsource (lib "eagle-import") (part "WIDERSTAND-0603"))
    )
    (comp (ref "R151")
      (value "WIDERSTAND-0603")
      (footprint "eagle-import:0603")
      (libsource (lib "eagle-import") (part "WIDERSTAND-0603"))
    )
    (comp (ref "R152")
      (value "WIDERSTAND-0603")
      (footprint "eagle-import:0603")
      (libsource (lib "eagle-import") (part "WIDERSTAND-0603"))
    )
    (comp (ref "R153")
      (value "WIDERSTAND-0603")
      (footprint "eagle-import:0603")
      (libsource (lib "eagle-import") (part "WIDERSTAND-0603"))
    )
    (comp (ref "R154")
      (value "WIDERSTAND-0603")
      (footprint "eagle-import:0603")
      (libsource (lib "eagle-import") (part "WIDERSTAND-0603"))
    )
    (comp (ref "R155")
      (value "WIDERSTAND-0603")
      (footprint "eagle-import:0603")
      (libsource (lib "eagle-import") (part "WIDERSTAND-0603"))
    )
    (comp (ref "R156")
      (value "WIDERSTAND-0603")
      (footprint "eagle-import:0603")
      (libsource (lib "eagle-import") (part "WIDERSTAND-0603"))
    )
    (comp (ref "R157")
      (value "WIDERSTAND-0603")
      (footprint "eagle-import:0603")
      (libsource (lib "eagle-import") (part "WIDERSTAND-0603"))
    )
    (comp (ref "R158")
      (value "WIDERSTAND-0603")
      (footprint "eagle-import:0603")
      (libsource (lib "eagle-import") (part "WIDERSTAND-0603"))
    )
    (comp (ref "R159")
      (value "WIDERSTAND-0603")
      (footprint "eagle-import:0603")
      (libsource (lib "eagle-import") (part "WIDERSTAND-0603"))
    )
    (comp (ref "R160")
      (value "WIDERSTAND-0603")
      (footprint "eagle-import:0603")
      (libsource (lib "eagle-import") (part "WIDERSTAND-0603"))
    )
    (comp (ref "R161")
      (value "WIDERSTAND-0603")
      (footprint "eagle-import:0603")
      (libsource (lib "eagle-import") (part "WIDERSTAND-0603"))
    )
    (comp (ref "R162")
      (value "WIDERSTAND-0603")
      (footprint "eagle-import:0603")
      (libsource (lib "eagle-import") (part "WIDERSTAND-0603"))
    )
    (comp (ref "R163")
      (value "WIDERSTAND-0603")
      (footprint "eagle-import:0603")
      (libsource (lib "eagle-import") (part "WIDERSTAND-0603"))
    )
    (comp (ref "R164")
      (value "WIDERSTAND-0603")
      (footprint "eagle-import:0603")
      (libsource (lib "eagle-import") (part "WIDERSTAND-0603"))
    )
    (comp (ref "R165")
      (value "WIDERSTAND-0603")
      (footprint "eagle-import:0603")
      (libsource (lib "eagle-import") (part "WIDERSTAND-0603"))
    )
    (comp (ref "R166")
      (value "WIDERSTAND-0603")
      (footprint "eagle-import:0603")
      (libsource (lib "eagle-import") (part "WIDERSTAND-0603"))
    )
    (comp (ref "R167")
      (value "WIDERSTAND-0603")
      (footprint "eagle-import:0603")
      (libsource (lib "eagle-import") (part "WIDERSTAND-0603"))
    )
    (comp (ref "R168")
      (value "WIDERSTAND-0603")
      (footprint "eagle-import:0603")
      (libsource (lib "eagle-import") (part "WIDERSTAND-0603"))
    )
    (comp (ref "R169")
      (value "WIDERSTAND-0603")
      (footprint "eagle-import:0603")
      (libsource (lib "eagle-import") (part "WIDERSTAND-0603"))
    )
    (comp (ref "R170")
      (value "WIDERSTAND-0603")
      (footprint "eagle-import:0603")
      (libsource (lib "eagle-import") (part "WIDERSTAND-0603"))
    )
    (comp (ref "R171")
      (value "WIDERSTAND-0603")
      (footprint "eagle-import:0603")
      (libsource (lib "eagle-import") (part "WIDERSTAND-0603"))
    )
    (comp (ref "R172")
      (value "WIDERSTAND-0603")
      (footprint "eagle-import:0603")
      (libsource (lib "eagle-import") (part "WIDERSTAND-0603"))
    )
    (comp (ref "R173")
      (value "WIDERSTAND-0603")
      (footprint "eagle-import:0603")
      (libsource (lib "eagle-import") (part "WIDERSTAND-0603"))
    )
    (comp (ref "R174")
      (value "WIDERSTAND-0603")
      (footprint "eagle-import:0603")
      (libsource (lib "eagle-import") (part "WIDERSTAND-0603"))
    )
    (comp (ref "R175")
      (value "WIDERSTAND-0603")
      (footprint "eagle-import:0603")
      (libsource (lib "eagle-import") (part "WIDERSTAND-0603"))
    )
    (comp (ref "R176")
      (value "WIDERSTAND-0603")
      (footprint "eagle-import:0603")
      (libsource (lib "eagle-import") (part "WIDERSTAND-0603"))
    )
    (comp (ref "R177")
      (value "WIDERSTAND-0603")
      (footprint "eagle-import:0603")
      (libsource (lib "eagle-import") (part "WIDERSTAND-0603"))
    )
    (comp (ref "R178")
      (value "WIDERSTAND-0603")
      (footprint "eagle-import:0603")
      (libsource (lib "eagle-import") (part "WIDERSTAND-0603"))
    )
    (comp (ref "R179")
      (value "WIDERSTAND-0603")
      (footprint "eagle-import:0603")
      (libsource (lib "eagle-import") (part "WIDERSTAND-0603"))
    )
    (comp (ref "R180")
      (value "WIDERSTAND-0603")
      (footprint "eagle-import:0603")
      (libsource (lib "eagle-import") (part "WIDERSTAND-0603"))
    )
    (comp (ref "R181")
      (value "WIDERSTAND-0603")
      (footprint "eagle-import:0603")
      (libsource (lib "eagle-import") (part "WIDERSTAND-0603"))
    )
    (comp (ref "R182")
      (value "WIDERSTAND-0603")
      (footprint "eagle-import:0603")
      (libsource (lib "eagle-import") (part "WIDERSTAND-0603"))
    )
    (comp (ref "R183")
      (value "WIDERSTAND-0603")
      (footprint "eagle-import:0603")
      (libsource (lib "eagle-import") (part "WIDERSTAND-0603"))
    )
    (comp (ref "R184")
      (value "WIDERSTAND-0603")
      (footprint "eagle-import:0603")
      (libsource (lib "eagle-import") (part "WIDERSTAND-0603"))
    )
    (comp (ref "R185")
      (value "WIDERSTAND-0603")
      (footprint "eagle-import:0603")
      (libsource (lib "eagle-import") (part "WIDERSTAND-0603"))
    )
    (comp (ref "R186")
      (value "WIDERSTAND-0603")
      (footprint "eagle-import:0603")
      (libsource (lib "eagle-import") (part "WIDERSTAND-0603"))
    )
    (comp (ref "R187")
      (value "WIDERSTAND-0603")
      (footprint "eagle-import:0603")
      (libsource (lib "eagle-import") (part "WIDERSTAND-0603"))
    )
    (comp (ref "R188")
      (value "WIDERSTAND-0603")
      (footprint "eagle-import:0603")
      (libsource (lib "eagle-import") (part "WIDERSTAND-0603"))
    )
    (comp (ref "R189")
      (value "WIDERSTAND-0603")
      (footprint "eagle-import:0603")
      (libsource (lib "eagle-import") (part "WIDERSTAND-0603"))
    )
    (comp (ref "R190")
      (value "WIDERSTAND-0603")
      (footprint "eagle-import:0603")
      (libsource (lib "eagle-import") (part "WIDERSTAND-0603"))
    )
    (comp (ref "R191")
      (value "WIDERSTAND-0603")
      (footprint "eagle-import:0603")
      (libsource (lib "eagle-import") (part "WIDERSTAND-0603"))
    )
    (comp (ref "R192")
      (value "WIDERSTAND-0603")
      (footprint "eagle-import:0603")
      (libsource (lib "eagle-import") (part "WIDERSTAND-0603"))
    )
    (comp (ref "R193")
      (value "WIDERSTAND-0603")
      (footprint "eagle-import:0603")
      (libsource (lib "eagle-import") (part "WIDERSTAND-0603"))
    )
    (comp (ref "R194")
      (value "WIDERSTAND-0603")
      (footprint "eagle-import:0603")
      (libsource (lib "eagle-import") (part "WIDERSTAND-0603"))
    )
    (comp (ref "R195")
      (value "WIDERSTAND-0603")
      (footprint "eagle-import:0603")
      (libsource (lib "eagle-import") (part "WIDERSTAND-0603"))
    )
    (comp (ref "R196")
      (value "WIDERSTAND-0603")
      (footprint "eagle-import:0603")
      (libsource (lib "eagle-import") (part "WIDERSTAND-0603"))
    )
    (comp (ref "R197")
      (value "WIDERSTAND-0603")
      (footprint "eagle-import:0603")
      (libsource (lib "eagle-import") (part "WIDERSTAND-0603"))
    )
    (comp (ref "R198")
      (value "WIDERSTAND-0603")
      (footprint "eagle-import:0603")
      (libsource (lib "eagle-import") (part "WIDERSTAND-0603"))
    )
    (comp (ref "R199")
      (value "WIDERSTAND-0603")
      (footprint "eagle-import:0603")
      (libsource (lib "eagle-import") (part "WIDERSTAND-0603"))
    )
    (comp (ref "R200")
      (value "WIDERSTAND-0603")
      (footprint "eagle-import:0603")
      (libsource (lib "eagle-import") (part "WIDERSTAND-0603"))
    )
    (comp (ref "R201")
      (value "WIDERSTAND-0603")
      (footprint "eagle-import:0603")
      (libsource (lib "eagle-import") (part "WIDERSTAND-0603"))
    )
    (comp (ref "R202")
      (value "WIDERSTAND-0603")
      (footprint "eagle-import:0603")
      (libsource (lib "eagle-import") (part "WIDERSTAND-0603"))
    )
    (comp (ref "R203")
      (value "WIDERSTAND-0603")
      (footprint "eagle-import:0603")
      (libsource (lib "eagle-import") (part "WIDERSTAND-0603"))
    )
    (comp (ref "R204")
      (value "WIDERSTAND-0603")
      (footprint "eagle-import:0603")
      (libsource (lib "eagle-import") (part "WIDERSTAND-0603"))
    )
    (comp (ref "R205")
      (value "WIDERSTAND-0603")
      (footprint "eagle-import:0603")
      (libsource (lib "eagle-import") (part "WIDERSTAND-0603"))
    )
    (comp (ref "R206")
      (value "WIDERSTAND-0603")
      (footprint "eagle-import:0603")
      (libsource (lib "eagle-import") (part "WIDERSTAND-0603"))
    )
    (comp (ref "R207")
      (value "WIDERSTAND-0603")
      (footprint "eagle-import:0603")
      (libsource (lib "eagle-import") (part "WIDERSTAND-0603"))
    )
    (comp (ref "R208")
      (value "WIDERSTAND-0603")
      (footprint "eagle-import:0603")
      (libsource (lib "eagle-import") (part "WIDERSTAND-0603"))
    )
    (comp (ref "R209")
      (value "WIDERSTAND-0603")
      (footprint "eagle-import:0603")
      (libsource (lib "eagle-import") (part "WIDERSTAND-0603"))
    )
    (comp (ref "R210")
      (value "WIDERSTAND-0603")
      (footprint "eagle-import:0603")
      (libsource (lib "eagle-import") (part "WIDERSTAND-0603"))
    )
    (comp (ref "R211")
      (value "WIDERSTAND-0603")
      (footprint "eagle-import:0603")
      (libsource (lib "eagle-import") (part "WIDERSTAND-0603"))
    )
    (comp (ref "R212")
      (value "WIDERSTAND-0603")
      (footprint "eagle-import:0603")
      (libsource (lib "eagle-import") (part "WIDERSTAND-0603"))
    )
    (comp (ref "R213")
      (value "WIDERSTAND-0603")
      (footprint "eagle-import:0603")
      (libsource (lib "eagle-import") (part "WIDERSTAND-0603"))
    )
    (comp (ref "R214")
      (value "WIDERSTAND-0603")
      (footprint "eagle-import:0603")
      (libsource (lib "eagle-import") (part "WIDERSTAND-0603"))
    )
    (comp (ref "R215")
      (value "WIDERSTAND-0603")
      (footprint "eagle-import:0603")
      (libsource (lib "eagle-import") (part "WIDERSTAND-0603"))
    )
    (comp (ref "LED1")
      (value "WS2812B")
      (footprint "eagle-import:WS2812B")
      (libsource (lib "eagle-import") (part "WS2812B"))
    )
    (comp (ref "LED2")
      (value "WS2812B")
      (footprint "eagle-import:WS2812B")
      (libsource (lib "eagle-import") (part "WS2812B"))
    )
    (comp (ref "LED3")
      (value "WS2812B")
      (footprint "eagle-import:WS2812B")
      (libsource (lib "eagle-import") (part "WS2812B"))
    )
    (comp (ref "LED4")
      (value "WS2812B")
      (footprint "eagle-import:WS2812B")
      (libsource (lib "eagle-import") (part "WS2812B"))
    )
    (comp (ref "LED5")
      (value "WS2812B")
      (footprint "eagle-import:WS2812B")
      (libsource (lib "eagle-import") (part "WS2812B"))
    )
    (comp (ref "LED6")
      (value "WS2812B")
      (footprint "eagle-import:WS2812B")
      (libsource (lib "eagle-import") (part "WS2812B"))
    )
    (comp (ref "LED7")
      (value "WS2812B")
      (footprint "eagle-import:WS2812B")
      (libsource (lib "eagle-import") (part "WS2812B"))
    )
    (comp (ref "LED8")
      (value "WS2812B")
      (footprint "eagle-import:WS2812B")
      (libsource (lib "eagle-import") (part "WS2812B"))
    )
    (comp (ref "LED9")
      (value "WS2812B")
      (footprint "eagle-import:WS2812B")
      (libsource (lib "eagle-import") (part "WS2812B"))
    )
    (comp (ref "LED10")
      (value "WS2812B")
      (footprint "eagle-import:WS2812B")
      (libsource (lib "eagle-import") (part "WS2812B"))
    )
    (comp (ref "LED11")
      (value "WS2812B")
      (footprint "eagle-import:WS2812B")
      (libsource (lib "eagle-import") (part "WS2812B"))
    )
    (comp (ref "LED12")
      (value "WS2812B")
      (footprint "eagle-import:WS2812B")
      (libsource (lib "eagle-import") (part "WS2812B"))
    )
    (comp (ref "LED13")
      (value "WS2812B")
      (footprint "eagle-import:WS2812B")
      (libsource (lib "eagle-import") (part "WS2812B"))
    )
    (comp (ref "LED14")
      (value "WS2812B")
      (footprint "eagle-import:WS2812B")
      (libsource (lib "eagle-import") (part "WS2812B"))
    )
    (comp (ref "LED15")
      (value "WS2812B")
      (footprint "eagle-import:WS2812B")
      (libsource (lib "eagle-import") (part "WS2812B"))
    )
    (comp (ref "LED16")
      (value "WS2812B")
      (footprint "eagle-import:WS2812B")
      (libsource (lib "eagle-import") (part "WS2812B"))
    )
    (comp (ref "LED17")
      (value "WS2812B")
      (footprint "eagle-import:WS2812B")
      (libsource (lib "eagle-import") (part "WS2812B"))
    )
    (comp (ref "LED18")
      (value "WS2812B")
      (footprint "eagle-import:WS2812B")
      (libsource (lib "eagle-import") (part "WS2812B"))
    )
    (comp (ref "LED19")
      (value "WS2812B")
      (footprint "eagle-import:WS2812B")
      (libsource (lib "eagle-import") (part "WS2812B"))
    )
    (comp (ref "LED20")
      (value "WS2812B")
      (footprint "eagle-import:WS2812B")
      (libsource (lib "eagle-import") (part "WS2812B"))
    )
    (comp (ref "LED21")
      (value "WS2812B")
      (footprint "eagle-import:WS2812B")
      (libsource (lib "eagle-import") (part "WS2812B"))
    )
    (comp (ref "LED22")
      (value "WS2812B")
      (footprint "eagle-import:WS2812B")
      (libsource (lib "eagle-import") (part "WS2812B"))
    )
    (comp (ref "LED23")
      (value "WS2812B")
      (footprint "eagle-import:WS2812B")
      (libsource (lib "eagle-import") (part "WS2812B"))
    )
    (comp (ref "LED24")
      (value "WS2812B")
      (footprint "eagle-import:WS2812B")
      (libsource (lib "eagle-import") (part "WS2812B"))
    )
    (comp (ref "LED25")
      (value "WS2812B")
      (footprint "eagle-import:WS2812B")
      (libsource (lib "eagle-import") (part "WS2812B"))
    )
    (comp (ref "LED26")
      (value "WS2812B")
      (footprint "eagle-import:WS2812B")
      (libsource (lib "eagle-import") (part "WS2812B"))
    )
    (comp (ref "LED27")
      (value "WS2812B")
      (footprint "eagle-import:WS2812B")
      (libsource (lib "eagle-import") (part "WS2812B"))
    )
    (comp (ref "LED28")
      (value "WS2812B")
      (footprint "eagle-import:WS2812B")
      (libsource (lib "eagle-import") (part "WS2812B"))
    )
    (comp (ref "LED29")
      (value "WS2812B")
      (footprint "eagle-import:WS2812B")
      (libsource (lib "eagle-import") (part "WS2812B"))
    )
    (comp (ref "LED30")
      (value "WS2812B")
      (footprint "eagle-import:WS2812B")
      (libsource (lib "eagle-import") (part "WS2812B"))
    )
    (comp (ref "LED31")
      (value "WS2812B")
      (footprint "eagle-import:WS2812B")
      (libsource (lib "eagle-import") (part "WS2812B"))
    )
    (comp (ref "LED32")
      (value "WS2812B")
      (footprint "eagle-import:WS2812B")
      (libsource (lib "eagle-import") (part "WS2812B"))
    )
    (comp (ref "LED33")
      (value "WS2812B")
      (footprint "eagle-import:WS2812B")
      (libsource (lib "eagle-import") (part "WS2812B"))
    )
    (comp (ref "LED34")
      (value "WS2812B")
      (footprint "eagle-import:WS2812B")
      (libsource (lib "eagle-import") (part "WS2812B"))
    )
    (comp (ref "LED35")
      (value "WS2812B")
      (footprint "eagle-import:WS2812B")
      (libsource (lib "eagle-import") (part "WS2812B"))
    )
    (comp (ref "LED36")
      (value "WS2812B")
      (footprint "eagle-import:WS2812B")
      (libsource (lib "eagle-import") (part "WS2812B"))
    )
    (comp (ref "LED37")
      (value "WS2812B")
      (footprint "eagle-import:WS2812B")
      (libsource (lib "eagle-import") (part "WS2812B"))
    )
    (comp (ref "LED38")
      (value "WS2812B")
      (footprint "eagle-import:WS2812B")
      (libsource (lib "eagle-import") (part "WS2812B"))
    )
    (comp (ref "LED39")
      (value "WS2812B")
      (footprint "eagle-import:WS2812B")
      (libsource (lib "eagle-import") (part "WS2812B"))
    )
    (comp (ref "LED40")
      (value "WS2812B")
      (footprint "eagle-import:WS2812B")
      (libsource (lib "eagle-import") (part "WS2812B"))
    )
    (comp (ref "LED41")
      (value "WS2812B")
      (footprint "eagle-import:WS2812B")
      (libsource (lib "eagle-import") (part "WS2812B"))
    )
    (comp (ref "LED42")
      (value "WS2812B")
      (footprint "eagle-import:WS2812B")
      (libsource (lib "eagle-import") (part "WS2812B"))
    )
    (comp (ref "LED43")
      (value "WS2812B")
      (footprint "eagle-import:WS2812B")
      (libsource (lib "eagle-import") (part "WS2812B"))
    )
    (comp (ref "LED44")
      (value "WS2812B")
      (footprint "eagle-import:WS2812B")
      (libsource (lib "eagle-import") (part "WS2812B"))
    )
    (comp (ref "LED45")
      (value "WS2812B")
      (footprint "eagle-import:WS2812B")
      (libsource (lib "eagle-import") (part "WS2812B"))
    )
    (comp (ref "LED46")
      (value "WS2812B")
      (footprint "eagle-import:WS2812B")
      (libsource (lib "eagle-import") (part "WS2812B"))
    )
    (comp (ref "LED47")
      (value "WS2812B")
      (footprint "eagle-import:WS2812B")
      (libsource (lib "eagle-import") (part "WS2812B"))
    )
    (comp (ref "LED48")
      (value "WS2812B")
      (footprint "eagle-import:WS2812B")
      (libsource (lib "eagle-import") (part "WS2812B"))
    )
    (comp (ref "LED49")
      (value "WS2812B")
      (footprint "eagle-import:WS2812B")
      (libsource (lib "eagle-import") (part "WS2812B"))
    )
    (comp (ref "LED50")
      (value "WS2812B")
      (footprint "eagle-import:WS2812B")
      (libsource (lib "eagle-import") (part "WS2812B"))
    )
    (comp (ref "LED51")
      (value "WS2812B")
      (footprint "eagle-import:WS2812B")
      (libsource (lib "eagle-import") (part "WS2812B"))
    )
    (comp (ref "LED52")
      (value "WS2812B")
      (footprint "eagle-import:WS2812B")
      (libsource (lib "eagle-import") (part "WS2812B"))
    )
    (comp (ref "LED53")
      (value "WS2812B")
      (footprint "eagle-import:WS2812B")
      (libsource (lib "eagle-import") (part "WS2812B"))
    )
    (comp (ref "LED54")
      (value "WS2812B")
      (footprint "eagle-import:WS2812B")
      (libsource (lib "eagle-import") (part "WS2812B"))
    )
    (comp (ref "LED55")
      (value "WS2812B")
      (footprint "eagle-import:WS2812B")
      (libsource (lib "eagle-import") (part "WS2812B"))
    )
    (comp (ref "LED56")
      (value "WS2812B")
      (footprint "eagle-import:WS2812B")
      (libsource (lib "eagle-import") (part "WS2812B"))
    )
    (comp (ref "LED57")
      (value "WS2812B")
      (footprint "eagle-import:WS2812B")
      (libsource (lib "eagle-import") (part "WS2812B"))
    )
    (comp (ref "LED58")
      (value "WS2812B")
      (footprint "eagle-import:WS2812B")
      (libsource (lib "eagle-import") (part "WS2812B"))
    )
    (comp (ref "LED59")
      (value "WS2812B")
      (footprint "eagle-import:WS2812B")
      (libsource (lib "eagle-import") (part "WS2812B"))
    )
    (comp (ref "LED60")
      (value "WS2812B")
      (footprint "eagle-import:WS2812B")
      (libsource (lib "eagle-import") (part "WS2812B"))
    )
    (comp (ref "R2")
      (value "WIDERSTAND-0603")
      (footprint "eagle-import:0603")
      (libsource (lib "eagle-import") (part "WIDERSTAND-0603"))
    )
    (comp (ref "R216")
      (value "WIDERSTAND-0603")
      (footprint "eagle-import:0603")
      (libsource (lib "eagle-import") (part "WIDERSTAND-0603"))
    )
    (comp (ref "R217")
      (value "WIDERSTAND-0603")
      (footprint "eagle-import:0603")
      (libsource (lib "eagle-import") (part "WIDERSTAND-0603"))
    )
    (comp (ref "R218")
      (value "WIDERSTAND-0603")
      (footprint "eagle-import:0603")
      (libsource (lib "eagle-import") (part "WIDERSTAND-0603"))
    )
    (comp (ref "R219")
      (value "WIDERSTAND-0603")
      (footprint "eagle-import:0603")
      (libsource (lib "eagle-import") (part "WIDERSTAND-0603"))
    )
    (comp (ref "R220")
      (value "WIDERSTAND-0603")
      (footprint "eagle-import:0603")
      (libsource (lib "eagle-import") (part "WIDERSTAND-0603"))
    )
    (comp (ref "R221")
      (value "WIDERSTAND-0603")
      (footprint "eagle-import:0603")
      (libsource (lib "eagle-import") (part "WIDERSTAND-0603"))
    )
    (comp (ref "R222")
      (value "WIDERSTAND-0603")
      (footprint "eagle-import:0603")
      (libsource (lib "eagle-import") (part "WIDERSTAND-0603"))
    )
    (comp (ref "R223")
      (value "WIDERSTAND-0603")
      (footprint "eagle-import:0603")
      (libsource (lib "eagle-import") (part "WIDERSTAND-0603"))
    )
    (comp (ref "R224")
      (value "WIDERSTAND-0603")
      (footprint "eagle-import:0603")
      (libsource (lib "eagle-import") (part "WIDERSTAND-0603"))
    )
    (comp (ref "R225")
      (value "WIDERSTAND-0603")
      (footprint "eagle-import:0603")
      (libsource (lib "eagle-import") (part "WIDERSTAND-0603"))
    )
    (comp (ref "R226")
      (value "WIDERSTAND-0603")
      (footprint "eagle-import:0603")
      (libsource (lib "eagle-import") (part "WIDERSTAND-0603"))
    )
    (comp (ref "R227")
      (value "WIDERSTAND-0603")
      (footprint "eagle-import:0603")
      (libsource (lib "eagle-import") (part "WIDERSTAND-0603"))
    )
    (comp (ref "R228")
      (value "WIDERSTAND-0603")
      (footprint "eagle-import:0603")
      (libsource (lib "eagle-import") (part "WIDERSTAND-0603"))
    )
    (comp (ref "R229")
      (value "WIDERSTAND-0603")
      (footprint "eagle-import:0603")
      (libsource (lib "eagle-import") (part "WIDERSTAND-0603"))
    )
    (comp (ref "R230")
      (value "WIDERSTAND-0603")
      (footprint "eagle-import:0603")
      (libsource (lib "eagle-import") (part "WIDERSTAND-0603"))
    )
    (comp (ref "R231")
      (value "WIDERSTAND-0603")
      (footprint "eagle-import:0603")
      (libsource (lib "eagle-import") (part "WIDERSTAND-0603"))
    )
    (comp (ref "R232")
      (value "WIDERSTAND-0603")
      (footprint "eagle-import:0603")
      (libsource (lib "eagle-import") (part "WIDERSTAND-0603"))
    )
    (comp (ref "R233")
      (value "WIDERSTAND-0603")
      (footprint "eagle-import:0603")
      (libsource (lib "eagle-import") (part "WIDERSTAND-0603"))
    )
    (comp (ref "R234")
      (value "WIDERSTAND-0603")
      (footprint "eagle-import:0603")
      (libsource (lib "eagle-import") (part "WIDERSTAND-0603"))
    )
    (comp (ref "R235")
      (value "WIDERSTAND-0603")
      (footprint "eagle-import:0603")
      (libsource (lib "eagle-import") (part "WIDERSTAND-0603"))
    )
    (comp (ref "R236")
      (value "WIDERSTAND-0603")
      (footprint "eagle-import:0603")
      (libsource (lib "eagle-import") (part "WIDERSTAND-0603"))
    )
    (comp (ref "R237")
      (value "WIDERSTAND-0603")
      (footprint "eagle-import:0603")
      (libsource (lib "eagle-import") (part "WIDERSTAND-0603"))
    )
    (comp (ref "R238")
      (value "WIDERSTAND-0603")
      (footprint "eagle-import:0603")
      (libsource (lib "eagle-import") (part "WIDERSTAND-0603"))
    )
    (comp (ref "R239")
      (value "WIDERSTAND-0603")
      (footprint "eagle-import:0603")
      (libsource (lib "eagle-import") (part "WIDERSTAND-0603"))
    )
    (comp (ref "R240")
      (value "WIDERSTAND-0603")
      (footprint "eagle-import:0603")
      (libsource (lib "eagle-import") (part "WIDERSTAND-0603"))
    )
    (comp (ref "R241")
      (value "WIDERSTAND-0603")
      (footprint "eagle-import:0603")
      (libsource (lib "eagle-import") (part "WIDERSTAND-0603"))
    )
    (comp (ref "R242")
      (value "WIDERSTAND-0603")
      (footprint "eagle-import:0603")
      (libsource (lib "eagle-import") (part "WIDERSTAND-0603"))
    )
    (comp (ref "R243")
      (value "WIDERSTAND-0603")
      (footprint "eagle-import:0603")
      (libsource (lib "eagle-import") (part "WIDERSTAND-0603"))
    )
    (comp (ref "R244")
      (value "WIDERSTAND-0603")
      (footprint "eagle-import:0603")
      (libsource (lib "eagle-import") (part "WIDERSTAND-0603"))
    )
    (comp (ref "R245")
      (value "WIDERSTAND-0603")
      (footprint "eagle-import:0603")
      (libsource (lib "eagle-import") (part "WIDERSTAND-0603"))
    )
    (comp (ref "R246")
      (value "WIDERSTAND-0603")
      (footprint "eagle-import:0603")
      (libsource (lib "eagle-import") (part "WIDERSTAND-0603"))
    )
    (comp (ref "R247")
      (value "WIDERSTAND-0603")
      (footprint "eagle-import:0603")
      (libsource (lib "eagle-import") (part "WIDERSTAND-0603"))
    )
    (comp (ref "R248")
      (value "WIDERSTAND-0603")
      (footprint "eagle-import:0603")
      (libsource (lib "eagle-import") (part "WIDERSTAND-0603"))
    )
    (comp (ref "R249")
      (value "WIDERSTAND-0603")
      (footprint "eagle-import:0603")
      (libsource (lib "eagle-import") (part "WIDERSTAND-0603"))
    )
    (comp (ref "R250")
      (value "WIDERSTAND-0603")
      (footprint "eagle-import:0603")
      (libsource (lib "eagle-import") (part "WIDERSTAND-0603"))
    )
    (comp (ref "R251")
      (value "WIDERSTAND-0603")
      (footprint "eagle-import:0603")
      (libsource (lib "eagle-import") (part "WIDERSTAND-0603"))
    )
    (comp (ref "R252")
      (value "WIDERSTAND-0603")
      (footprint "eagle-import:0603")
      (libsource (lib "eagle-import") (part "WIDERSTAND-0603"))
    )
    (comp (ref "R253")
      (value "WIDERSTAND-0603")
      (footprint "eagle-import:0603")
      (libsource (lib "eagle-import") (part "WIDERSTAND-0603"))
    )
    (comp (ref "R254")
      (value "WIDERSTAND-0603")
      (footprint "eagle-import:0603")
      (libsource (lib "eagle-import") (part "WIDERSTAND-0603"))
    )
    (comp (ref "R255")
      (value "WIDERSTAND-0603")
      (footprint "eagle-import:0603")
      (libsource (lib "eagle-import") (part "WIDERSTAND-0603"))
    )
    (comp (ref "R256")
      (value "WIDERSTAND-0603")
      (footprint "eagle-import:0603")
      (libsource (lib "eagle-import") (part "WIDERSTAND-0603"))
    )
    (comp (ref "R257")
      (value "WIDERSTAND-0603")
      (footprint "eagle-import:0603")
      (libsource (lib "eagle-import") (part "WIDERSTAND-0603"))
    )
    (comp (ref "R258")
      (value "WIDERSTAND-0603")
      (footprint "eagle-import:0603")
      (libsource (lib "eagle-import") (part "WIDERSTAND-0603"))
    )
    (comp (ref "R259")
      (value "WIDERSTAND-0603")
      (footprint "eagle-import:0603")
      (libsource (lib "eagle-import") (part "WIDERSTAND-0603"))
    )
    (comp (ref "R260")
      (value "WIDERSTAND-0603")
      (footprint "eagle-import:0603")
      (libsource (lib "eagle-import") (part "WIDERSTAND-0603"))
    )
    (comp (ref "R261")
      (value "WIDERSTAND-0603")
      (footprint "eagle-import:0603")
      (libsource (lib "eagle-import") (part "WIDERSTAND-0603"))
    )
    (comp (ref "R262")
      (value "WIDERSTAND-0603")
      (footprint "eagle-import:0603")
      (libsource (lib "eagle-import") (part "WIDERSTAND-0603"))
    )
    (comp (ref "R263")
      (value "WIDERSTAND-0603")
      (footprint "eagle-import:0603")
      (libsource (lib "eagle-import") (part "WIDERSTAND-0603"))
    )
    (comp (ref "R264")
      (value "WIDERSTAND-0603")
      (footprint "eagle-import:0603")
      (libsource (lib "eagle-import") (part "WIDERSTAND-0603"))
    )
    (comp (ref "R265")
      (value "WIDERSTAND-0603")
      (footprint "eagle-import:0603")
      (libsource (lib "eagle-import") (part "WIDERSTAND-0603"))
    )
    (comp (ref "R266")
      (value "WIDERSTAND-0603")
      (footprint "eagle-import:0603")
      (libsource (lib "eagle-import") (part "WIDERSTAND-0603"))
    )
    (comp (ref "R267")
      (value "WIDERSTAND-0603")
      (footprint "eagle-import:0603")
      (libsource (lib "eagle-import") (part "WIDERSTAND-0603"))
    )
    (comp (ref "R268")
      (value "WIDERSTAND-0603")
      (footprint "eagle-import:0603")
      (libsource (lib "eagle-import") (part "WIDERSTAND-0603"))
    )
    (comp (ref "R269")
      (value "WIDERSTAND-0603")
      (footprint "eagle-import:0603")
      (libsource (lib "eagle-import") (part "WIDERSTAND-0603"))
    )
    (comp (ref "R270")
      (value "WIDERSTAND-0603")
      (footprint "eagle-import:0603")
      (libsource (lib "eagle-import") (part "WIDERSTAND-0603"))
    )
    (comp (ref "R271")
      (value "WIDERSTAND-0603")
      (footprint "eagle-import:0603")
      (libsource (lib "eagle-import") (part "WIDERSTAND-0603"))
    )
    (comp (ref "R272")
      (value "WIDERSTAND-0603")
      (footprint "eagle-import:0603")
      (libsource (lib "eagle-import") (part "WIDERSTAND-0603"))
    )
    (comp (ref "R273")
      (value "WIDERSTAND-0603")
      (footprint "eagle-import:0603")
      (libsource (lib "eagle-import") (part "WIDERSTAND-0603"))
    )
    (comp (ref "R274")
      (value "WIDERSTAND-0603")
      (footprint "eagle-import:0603")
      (libsource (lib "eagle-import") (part "WIDERSTAND-0603"))
    )
    (comp (ref "R275")
      (value "WIDERSTAND-0603")
      (footprint "eagle-import:0603")
      (libsource (lib "eagle-import") (part "WIDERSTAND-0603"))
    )
    (comp (ref "R276")
      (value "WIDERSTAND-0603")
      (footprint "eagle-import:0603")
      (libsource (lib "eagle-import") (part "WIDERSTAND-0603"))
    )
    (comp (ref "R277")
      (value "WIDERSTAND-0603")
      (footprint "eagle-import:0603")
      (libsource (lib "eagle-import") (part "WIDERSTAND-0603"))
    )
    (comp (ref "R278")
      (value "WIDERSTAND-0603")
      (footprint "eagle-import:0603")
      (libsource (lib "eagle-import") (part "WIDERSTAND-0603"))
    )
    (comp (ref "R279")
      (value "WIDERSTAND-0603")
      (footprint "eagle-import:0603")
      (libsource (lib "eagle-import") (part "WIDERSTAND-0603"))
    )
    (comp (ref "R280")
      (value "WIDERSTAND-0603")
      (footprint "eagle-import:0603")
      (libsource (lib "eagle-import") (part "WIDERSTAND-0603"))
    )
    (comp (ref "R281")
      (value "WIDERSTAND-0603")
      (footprint "eagle-import:0603")
      (libsource (lib "eagle-import") (part "WIDERSTAND-0603"))
    )
    (comp (ref "R282")
      (value "WIDERSTAND-0603")
      (footprint "eagle-import:0603")
      (libsource (lib "eagle-import") (part "WIDERSTAND-0603"))
    )
    (comp (ref "R283")
      (value "WIDERSTAND-0603")
      (footprint "eagle-import:0603")
      (libsource (lib "eagle-import") (part "WIDERSTAND-0603"))
    )
    (comp (ref "R284")
      (value "WIDERSTAND-0603")
      (footprint "eagle-import:0603")
      (libsource (lib "eagle-import") (part "WIDERSTAND-0603"))
    )
    (comp (ref "R288")
      (value "WIDERSTAND-0603")
      (footprint "eagle-import:0603")
      (libsource (lib "eagle-import") (part "WIDERSTAND-0603"))
    )
    (comp (ref "R289")
      (value "WIDERSTAND-0603")
      (footprint "eagle-import:0603")
      (libsource (lib "eagle-import") (part "WIDERSTAND-0603"))
    )
    (comp (ref "R290")
      (value "WIDERSTAND-0603")
      (footprint "eagle-import:0603")
      (libsource (lib "eagle-import") (part "WIDERSTAND-0603"))
    )
    (comp (ref "R291")
      (value "WIDERSTAND-0603")
      (footprint "eagle-import:0603")
      (libsource (lib "eagle-import") (part "WIDERSTAND-0603"))
    )
    (comp (ref "R292")
      (value "WIDERSTAND-0603")
      (footprint "eagle-import:0603")
      (libsource (lib "eagle-import") (part "WIDERSTAND-0603"))
    )
    (comp (ref "R293")
      (value "WIDERSTAND-0603")
      (footprint "eagle-import:0603")
      (libsource (lib "eagle-import") (part "WIDERSTAND-0603"))
    )
    (comp (ref "R294")
      (value "WIDERSTAND-0603")
      (footprint "eagle-import:0603")
      (libsource (lib "eagle-import") (part "WIDERSTAND-0603"))
    )
    (comp (ref "R295")
      (value "WIDERSTAND-0603")
      (footprint "eagle-import:0603")
      (libsource (lib "eagle-import") (part "WIDERSTAND-0603"))
    )
    (comp (ref "R296")
      (value "WIDERSTAND-0603")
      (footprint "eagle-import:0603")
      (libsource (lib "eagle-import") (part "WIDERSTAND-0603"))
    )
    (comp (ref "R297")
      (value "WIDERSTAND-0603")
      (footprint "eagle-import:0603")
      (libsource (lib "eagle-import") (part "WIDERSTAND-0603"))
    )
    (comp (ref "R298")
      (value "WIDERSTAND-0603")
      (footprint "eagle-import:0603")
      (libsource (lib "eagle-import") (part "WIDERSTAND-0603"))
    )
    (comp (ref "R299")
      (value "WIDERSTAND-0603")
      (footprint "eagle-import:0603")
      (libsource (lib "eagle-import") (part "WIDERSTAND-0603"))
    )
    (comp (ref "R300")
      (value "WIDERSTAND-0603")
      (footprint "eagle-import:0603")
      (libsource (lib "eagle-import") (part "WIDERSTAND-0603"))
    )
    (comp (ref "R301")
      (value "WIDERSTAND-0603")
      (footprint "eagle-import:0603")
      (libsource (lib "eagle-import") (part "WIDERSTAND-0603"))
    )
    (comp (ref "R302")
      (value "WIDERSTAND-0603")
      (footprint "eagle-import:0603")
      (libsource (lib "eagle-import") (part "WIDERSTAND-0603"))
    )
    (comp (ref "R303")
      (value "WIDERSTAND-0603")
      (footprint "eagle-import:0603")
      (libsource (lib "eagle-import") (part "WIDERSTAND-0603"))
    )
    (comp (ref "R304")
      (value "WIDERSTAND-0603")
      (footprint "eagle-import:0603")
      (libsource (lib "eagle-import") (part "WIDERSTAND-0603"))
    )
    (comp (ref "R305")
      (value "WIDERSTAND-0603")
      (footprint "eagle-import:0603")
      (libsource (lib "eagle-import") (part "WIDERSTAND-0603"))
    )
    (comp (ref "R306")
      (value "WIDERSTAND-0603")
      (footprint "eagle-import:0603")
      (libsource (lib "eagle-import") (part "WIDERSTAND-0603"))
    )
    (comp (ref "R307")
      (value "WIDERSTAND-0603")
      (footprint "eagle-import:0603")
      (libsource (lib "eagle-import") (part "WIDERSTAND-0603"))
    )
    (comp (ref "R308")
      (value "WIDERSTAND-0603")
      (footprint "eagle-import:0603")
      (libsource (lib "eagle-import") (part "WIDERSTAND-0603"))
    )
    (comp (ref "R309")
      (value "WIDERSTAND-0603")
      (footprint "eagle-import:0603")
      (libsource (lib "eagle-import") (part "WIDERSTAND-0603"))
    )
    (comp (ref "R310")
      (value "WIDERSTAND-0603")
      (footprint "eagle-import:0603")
      (libsource (lib "eagle-import") (part "WIDERSTAND-0603"))
    )
    (comp (ref "R311")
      (value "WIDERSTAND-0603")
      (footprint "eagle-import:0603")
      (libsource (lib "eagle-import") (part "WIDERSTAND-0603"))
    )
    (comp (ref "R312")
      (value "WIDERSTAND-0603")
      (footprint "eagle-import:0603")
      (libsource (lib "eagle-import") (part "WIDERSTAND-0603"))
    )
    (comp (ref "R313")
      (value "WIDERSTAND-0603")
      (footprint "eagle-import:0603")
      (libsource (lib "eagle-import") (part "WIDERSTAND-0603"))
    )
    (comp (ref "R314")
      (value "WIDERSTAND-0603")
      (footprint "eagle-import:0603")
      (libsource (lib "eagle-import") (part "WIDERSTAND-0603"))
    )
    (comp (ref "R315")
      (value "WIDERSTAND-0603")
      (footprint "eagle-import:0603")
      (libsource (lib "eagle-import") (part "WIDERSTAND-0603"))
    )
    (comp (ref "R316")
      (value "WIDERSTAND-0603")
      (footprint "eagle-import:0603")
      (libsource (lib "eagle-import") (part "WIDERSTAND-0603"))
    )
    (comp (ref "R317")
      (value "WIDERSTAND-0603")
      (footprint "eagle-import:0603")
      (libsource (lib "eagle-import") (part "WIDERSTAND-0603"))
    )
    (comp (ref "R318")
      (value "WIDERSTAND-0603")
      (footprint "eagle-import:0603")
      (libsource (lib "eagle-import") (part "WIDERSTAND-0603"))
    )
    (comp (ref "R319")
      (value "WIDERSTAND-0603")
      (footprint "eagle-import:0603")
      (libsource (lib "eagle-import") (part "WIDERSTAND-0603"))
    )
    (comp (ref "R320")
      (value "WIDERSTAND-0603")
      (footprint "eagle-import:0603")
      (libsource (lib "eagle-import") (part "WIDERSTAND-0603"))
    )
    (comp (ref "R321")
      (value "WIDERSTAND-0603")
      (footprint "eagle-import:0603")
      (libsource (lib "eagle-import") (part "WIDERSTAND-0603"))
    )
    (comp (ref "R322")
      (value "WIDERSTAND-0603")
      (footprint "eagle-import:0603")
      (libsource (lib "eagle-import") (part "WIDERSTAND-0603"))
    )
    (comp (ref "R323")
      (value "WIDERSTAND-0603")
      (footprint "eagle-import:0603")
      (libsource (lib "eagle-import") (part "WIDERSTAND-0603"))
    )
    (comp (ref "R324")
      (value "WIDERSTAND-0603")
      (footprint "eagle-import:0603")
      (libsource (lib "eagle-import") (part "WIDERSTAND-0603"))
    )
    (comp (ref "R325")
      (value "WIDERSTAND-0603")
      (footprint "eagle-import:0603")
      (libsource (lib "eagle-import") (part "WIDERSTAND-0603"))
    )
    (comp (ref "R326")
      (value "WIDERSTAND-0603")
      (footprint "eagle-import:0603")
      (libsource (lib "eagle-import") (part "WIDERSTAND-0603"))
    )
    (comp (ref "R327")
      (value "WIDERSTAND-0603")
      (footprint "eagle-import:0603")
      (libsource (lib "eagle-import") (part "WIDERSTAND-0603"))
    )
    (comp (ref "R328")
      (value "WIDERSTAND-0603")
      (footprint "eagle-import:0603")
      (libsource (lib "eagle-import") (part "WIDERSTAND-0603"))
    )
    (comp (ref "R329")
      (value "WIDERSTAND-0603")
      (footprint "eagle-import:0603")
      (libsource (lib "eagle-import") (part "WIDERSTAND-0603"))
    )
    (comp (ref "R330")
      (value "WIDERSTAND-0603")
      (footprint "eagle-import:0603")
      (libsource (lib "eagle-import") (part "WIDERSTAND-0603"))
    )
    (comp (ref "R331")
      (value "WIDERSTAND-0603")
      (footprint "eagle-import:0603")
      (libsource (lib "eagle-import") (part "WIDERSTAND-0603"))
    )
    (comp (ref "R332")
      (value "WIDERSTAND-0603")
      (footprint "eagle-import:0603")
      (libsource (lib "eagle-import") (part "WIDERSTAND-0603"))
    )
    (comp (ref "R333")
      (value "WIDERSTAND-0603")
      (footprint "eagle-import:0603")
      (libsource (lib "eagle-import") (part "WIDERSTAND-0603"))
    )
    (comp (ref "R334")
      (value "WIDERSTAND-0603")
      (footprint "eagle-import:0603")
      (libsource (lib "eagle-import") (part "WIDERSTAND-0603"))
    )
    (comp (ref "R335")
      (value "WIDERSTAND-0603")
      (footprint "eagle-import:0603")
      (libsource (lib "eagle-import") (part "WIDERSTAND-0603"))
    )
    (comp (ref "R336")
      (value "WIDERSTAND-0603")
      (footprint "eagle-import:0603")
      (libsource (lib "eagle-import") (part "WIDERSTAND-0603"))
    )
    (comp (ref "R337")
      (value "WIDERSTAND-0603")
      (footprint "eagle-import:0603")
      (libsource (lib "eagle-import") (part "WIDERSTAND-0603"))
    )
    (comp (ref "R338")
      (value "WIDERSTAND-0603")
      (footprint "eagle-import:0603")
      (libsource (lib "eagle-import") (part "WIDERSTAND-0603"))
    )
    (comp (ref "R339")
      (value "WIDERSTAND-0603")
      (footprint "eagle-import:0603")
      (libsource (lib "eagle-import") (part "WIDERSTAND-0603"))
    )
    (comp (ref "R340")
      (value "WIDERSTAND-0603")
      (footprint "eagle-import:0603")
      (libsource (lib "eagle-import") (part "WIDERSTAND-0603"))
    )
    (comp (ref "R341")
      (value "WIDERSTAND-0603")
      (footprint "eagle-import:0603")
      (libsource (lib "eagle-import") (part "WIDERSTAND-0603"))
    )
    (comp (ref "R342")
      (value "WIDERSTAND-0603")
      (footprint "eagle-import:0603")
      (libsource (lib "eagle-import") (part "WIDERSTAND-0603"))
    )
    (comp (ref "R343")
      (value "WIDERSTAND-0603")
      (footprint "eagle-import:0603")
      (libsource (lib "eagle-import") (part "WIDERSTAND-0603"))
    )
    (comp (ref "R344")
      (value "WIDERSTAND-0603")
      (footprint "eagle-import:0603")
      (libsource (lib "eagle-import") (part "WIDERSTAND-0603"))
    )
    (comp (ref "R345")
      (value "WIDERSTAND-0603")
      (footprint "eagle-import:0603")
      (libsource (lib "eagle-import") (part "WIDERSTAND-0603"))
    )
    (comp (ref "R346")
      (value "WIDERSTAND-0603")
      (footprint "eagle-import:0603")
      (libsource (lib "eagle-import") (part "WIDERSTAND-0603"))
    )
    (comp (ref "R347")
      (value "WIDERSTAND-0603")
      (footprint "eagle-import:0603")
      (libsource (lib "eagle-import") (part "WIDERSTAND-0603"))
    )
    (comp (ref "R348")
      (value "WIDERSTAND-0603")
      (footprint "eagle-import:0603")
      (libsource (lib "eagle-import") (part "WIDERSTAND-0603"))
    )
    (comp (ref "R349")
      (value "WIDERSTAND-0603")
      (footprint "eagle-import:0603")
      (libsource (lib "eagle-import") (part "WIDERSTAND-0603"))
    )
    (comp (ref "R350")
      (value "WIDERSTAND-0603")
      (footprint "eagle-import:0603")
      (libsource (lib "eagle-import") (part "WIDERSTAND-0603"))
    )
    (comp (ref "R351")
      (value "WIDERSTAND-0603")
      (footprint "eagle-import:0603")
      (libsource (lib "eagle-import") (part "WIDERSTAND-0603"))
    )
    (comp (ref "R352")
      (value "WIDERSTAND-0603")
      (footprint "eagle-import:0603")
      (libsource (lib "eagle-import") (part "WIDERSTAND-0603"))
    )
    (comp (ref "R353")
      (value "WIDERSTAND-0603")
      (footprint "eagle-import:0603")
      (libsource (lib "eagle-import") (part "WIDERSTAND-0603"))
    )
    (comp (ref "R354")
      (value "WIDERSTAND-0603")
      (footprint "eagle-import:0603")
      (libsource (lib "eagle-import") (part "WIDERSTAND-0603"))
    )
    (comp (ref "R355")
      (value "WIDERSTAND-0603")
      (footprint "eagle-import:0603")
      (libsource (lib "eagle-import") (part "WIDERSTAND-0603"))
    )
    (comp (ref "R356")
      (value "WIDERSTAND-0603")
      (footprint "eagle-import:0603")
      (libsource (lib "eagle-import") (part "WIDERSTAND-0603"))
    )
    (comp (ref "R357")
      (value "WIDERSTAND-0603")
      (footprint "eagle-import:0603")
      (libsource (lib "eagle-import") (part "WIDERSTAND-0603"))
    )
    (comp (ref "C1")
      (value "KONDENSATOR-0603")
      (footprint "eagle-import:0603")
      (libsource (lib "eagle-import") (part "KONDENSATOR-0603"))
    )
    (comp (ref "C2")
      (value "KONDENSATOR-0603")
      (footprint "eagle-import:0603")
      (libsource (lib "eagle-import") (part "KONDENSATOR-0603"))
    )
    (comp (ref "C3")
      (value "KONDENSATOR-0603")
      (footprint "eagle-import:0603")
      (libsource (lib "eagle-import") (part "KONDENSATOR-0603"))
    )
    (comp (ref "C4")
      (value "KONDENSATOR-0603")
      (footprint "eagle-import:0603")
      (libsource (lib "eagle-import") (part "KONDENSATOR-0603"))
    )
    (comp (ref "C5")
      (value "KONDENSATOR-0603")
      (footprint "eagle-import:0603")
      (libsource (lib "eagle-import") (part "KONDENSATOR-0603"))
    )
    (comp (ref "C6")
      (value "KONDENSATOR-0603")
      (footprint "eagle-import:0603")
      (libsource (lib "eagle-import") (part "KONDENSATOR-0603"))
    )
    (comp (ref "C7")
      (value "KONDENSATOR-0603")
      (footprint "eagle-import:0603")
      (libsource (lib "eagle-import") (part "KONDENSATOR-0603"))
    )
    (comp (ref "C8")
      (value "KONDENSATOR-0603")
      (footprint "eagle-import:0603")
      (libsource (lib "eagle-import") (part "KONDENSATOR-0603"))
    )
    (comp (ref "C9")
      (value "KONDENSATOR-0603")
      (footprint "eagle-import:0603")
      (libsource (lib "eagle-import") (part "KONDENSATOR-0603"))
    )
    (comp (ref "C10")
      (value "KONDENSATOR-0603")
      (footprint "eagle-import:0603")
      (libsource (lib "eagle-import") (part "KONDENSATOR-0603"))
    )
    (comp (ref "C11")
      (value "KONDENSATOR-0603")
      (footprint "eagle-import:0603")
      (libsource (lib "eagle-import") (part "KONDENSATOR-0603"))
    )
    (comp (ref "C12")
      (value "KONDENSATOR-0603")
      (footprint "eagle-import:0603")
      (libsource (lib "eagle-import") (part "KONDENSATOR-0603"))
    )
    (comp (ref "C13")
      (value "KONDENSATOR-0603")
      (footprint "eagle-import:0603")
      (libsource (lib "eagle-import") (part "KONDENSATOR-0603"))
    )
    (comp (ref "C14")
      (value "KONDENSATOR-0603")
      (footprint "eagle-import:0603")
      (libsource (lib "eagle-import") (part "KONDENSATOR-0603"))
    )
    (comp (ref "C15")
      (value "KONDENSATOR-0603")
      (footprint "eagle-import:0603")
      (libsource (lib "eagle-import") (part "KONDENSATOR-0603"))
    )
    (comp (ref "C16")
      (value "KONDENSATOR-0603")
      (footprint "eagle-import:0603")
      (libsource (lib "eagle-import") (part "KONDENSATOR-0603"))
    )
    (comp (ref "C17")
      (value "KONDENSATOR-0603")
      (footprint "eagle-import:0603")
      (libsource (lib "eagle-import") (part "KONDENSATOR-0603"))
    )
    (comp (ref "C18")
      (value "KONDENSATOR-0603")
      (footprint "eagle-import:0603")
      (libsource (lib "eagle-import") (part "KONDENSATOR-0603"))
    )
    (comp (ref "C19")
      (value "KONDENSATOR-0603")
      (footprint "eagle-import:0603")
      (libsource (lib "eagle-import") (part "KONDENSATOR-0603"))
    )
    (comp (ref "C20")
      (value "KONDENSATOR-0603")
      (footprint "eagle-import:0603")
      (libsource (lib "eagle-import") (part "KONDENSATOR-0603"))
    )
    (comp (ref "C21")
      (value "KONDENSATOR-0603")
      (footprint "eagle-import:0603")
      (libsource (lib "eagle-import") (part "KONDENSATOR-0603"))
    )
    (comp (ref "C22")
      (value "KONDENSATOR-0603")
      (footprint "eagle-import:0603")
      (libsource (lib "eagle-import") (part "KONDENSATOR-0603"))
    )
    (comp (ref "C23")
      (value "KONDENSATOR-0603")
      (footprint "eagle-import:0603")
      (libsource (lib "eagle-import") (part "KONDENSATOR-0603"))
    )
    (comp (ref "C24")
      (value "KONDENSATOR-0603")
      (footprint "eagle-import:0603")
      (libsource (lib "eagle-import") (part "KONDENSATOR-0603"))
    )
    (comp (ref "C25")
      (value "KONDENSATOR-0603")
      (footprint "eagle-import:0603")
      (libsource (lib "eagle-import") (part "KONDENSATOR-0603"))
    )
    (comp (ref "C26")
      (value "KONDENSATOR-0603")
      (footprint "eagle-import:0603")
      (libsource (lib "eagle-import") (part "KONDENSATOR-0603"))
    )
    (comp (ref "C27")
      (value "KONDENSATOR-0603")
      (footprint "eagle-import:0603")
      (libsource (lib "eagle-import") (part "KONDENSATOR-0603"))
    )
    (comp (ref "C28")
      (value "KONDENSATOR-0603")
      (footprint "eagle-import:0603")
      (libsource (lib "eagle-import") (part "KONDENSATOR-0603"))
    )
    (comp (ref "C29")
      (value "KONDENSATOR-0603")
      (footprint "eagle-import:0603")
      (libsource (lib "eagle-import") (part "KONDENSATOR-0603"))
    )
    (comp (ref "C30")
      (value "KONDENSATOR-0603")
      (footprint "eagle-import:0603")
      (libsource (lib "eagle-import") (part "KONDENSATOR-0603"))
    )
    (comp (ref "C31")
      (value "KONDENSATOR-0603")
      (footprint "eagle-import:0603")
      (libsource (lib "eagle-import") (part "KONDENSATOR-0603"))
    )
    (comp (ref "C32")
      (value "KONDENSATOR-0603")
      (footprint "eagle-import:0603")
      (libsource (lib "eagle-import") (part "KONDENSATOR-0603"))
    )
    (comp (ref "C33")
      (value "KONDENSATOR-0603")
      (footprint "eagle-import:0603")
      (libsource (lib "eagle-import") (part "KONDENSATOR-0603"))
    )
    (comp (ref "C34")
      (value "KONDENSATOR-0603")
      (footprint "eagle-import:0603")
      (libsource (lib "eagle-import") (part "KONDENSATOR-0603"))
    )
    (comp (ref "C35")
      (value "KONDENSATOR-0603")
      (footprint "eagle-import:0603")
      (libsource (lib "eagle-import") (part "KONDENSATOR-0603"))
    )
    (comp (ref "C36")
      (value "KONDENSATOR-0603")
      (footprint "eagle-import:0603")
      (libsource (lib "eagle-import") (part "KONDENSATOR-0603"))
    )
    (comp (ref "C37")
      (value "KONDENSATOR-0603")
      (footprint "eagle-import:0603")
      (libsource (lib "eagle-import") (part "KONDENSATOR-0603"))
    )
    (comp (ref "C38")
      (value "KONDENSATOR-0603")
      (footprint "eagle-import:0603")
      (libsource (lib "eagle-import") (part "KONDENSATOR-0603"))
    )
    (comp (ref "C39")
      (value "KONDENSATOR-0603")
      (footprint "eagle-import:0603")
      (libsource (lib "eagle-import") (part "KONDENSATOR-0603"))
    )
    (comp (ref "C40")
      (value "KONDENSATOR-0603")
      (footprint "eagle-import:0603")
      (libsource (lib "eagle-import") (part "KONDENSATOR-0603"))
    )
    (comp (ref "C41")
      (value "KONDENSATOR-0603")
      (footprint "eagle-import:0603")
      (libsource (lib "eagle-import") (part "KONDENSATOR-0603"))
    )
    (comp (ref "C42")
      (value "KONDENSATOR-0603")
      (footprint "eagle-import:0603")
      (libsource (lib "eagle-import") (part "KONDENSATOR-0603"))
    )
    (comp (ref "C43")
      (value "KONDENSATOR-0603")
      (footprint "eagle-import:0603")
      (libsource (lib "eagle-import") (part "KONDENSATOR-0603"))
    )
    (comp (ref "C44")
      (value "KONDENSATOR-0603")
      (footprint "eagle-import:0603")
      (libsource (lib "eagle-import") (part "KONDENSATOR-0603"))
    )
    (comp (ref "C45")
      (value "KONDENSATOR-0603")
      (footprint "eagle-import:0603")
      (libsource (lib "eagle-import") (part "KONDENSATOR-0603"))
    )
    (comp (ref "C46")
      (value "KONDENSATOR-0603")
      (footprint "eagle-import:0603")
      (libsource (lib "eagle-import") (part "KONDENSATOR-0603"))
    )
    (comp (ref "C47")
      (value "KONDENSATOR-0603")
      (footprint "eagle-import:0603")
      (libsource (lib "eagle-import") (part "KONDENSATOR-0603"))
    )
    (comp (ref "C48")
      (value "KONDENSATOR-0603")
      (footprint "eagle-import:0603")
      (libsource (lib "eagle-import") (part "KONDENSATOR-0603"))
    )
    (comp (ref "C49")
      (value "KONDENSATOR-0603")
      (footprint "eagle-import:0603")
      (libsource (lib "eagle-import") (part "KONDENSATOR-0603"))
    )
    (comp (ref "C50")
      (value "KONDENSATOR-0603")
      (footprint "eagle-import:0603")
      (libsource (lib "eagle-import") (part "KONDENSATOR-0603"))
    )
    (comp (ref "C51")
      (value "KONDENSATOR-0603")
      (footprint "eagle-import:0603")
      (libsource (lib "eagle-import") (part "KONDENSATOR-0603"))
    )
    (comp (ref "C52")
      (value "KONDENSATOR-0603")
      (footprint "eagle-import:0603")
      (libsource (lib "eagle-import") (part "KONDENSATOR-0603"))
    )
    (comp (ref "C53")
      (value "KONDENSATOR-0603")
      (footprint "eagle-import:0603")
      (libsource (lib "eagle-import") (part "KONDENSATOR-0603"))
    )
    (comp (ref "C54")
      (value "KONDENSATOR-0603")
      (footprint "eagle-import:0603")
      (libsource (lib "eagle-import") (part "KONDENSATOR-0603"))
    )
    (comp (ref "C55")
      (value "KONDENSATOR-0603")
      (footprint "eagle-import:0603")
      (libsource (lib "eagle-import") (part "KONDENSATOR-0603"))
    )
    (comp (ref "C56")
      (value "KONDENSATOR-0603")
      (footprint "eagle-import:0603")
      (libsource (lib "eagle-import") (part "KONDENSATOR-0603"))
    )
    (comp (ref "C57")
      (value "KONDENSATOR-0603")
      (footprint "eagle-import:0603")
      (libsource (lib "eagle-import") (part "KONDENSATOR-0603"))
    )
    (comp (ref "C58")
      (value "KONDENSATOR-0603")
      (footprint "eagle-import:0603")
      (libsource (lib "eagle-import") (part "KONDENSATOR-0603"))
    )
    (comp (ref "C59")
      (value "KONDENSATOR-0603")
      (footprint "eagle-import:0603")
      (libsource (lib "eagle-import") (part "KONDENSATOR-0603"))
    )
    (comp (ref "C60")
      (value "KONDENSATOR-0603")
      (footprint "eagle-import:0603")
      (libsource (lib "eagle-import") (part "KONDENSATOR-0603"))
    )
    (comp (ref "C61")
      (value "KONDENSATOR-0603")
      (footprint "eagle-import:0603")
      (libsource (lib "eagle-import") (part "KONDENSATOR-0603"))
    )
    (comp (ref "C62")
      (value "KONDENSATOR-0603")
      (footprint "eagle-import:0603")
      (libsource (lib "eagle-import") (part "KONDENSATOR-0603"))
    )
    (comp (ref "C63")
      (value "KONDENSATOR-0603")
      (footprint "eagle-import:0603")
      (libsource (lib "eagle-import") (part "KONDENSATOR-0603"))
    )
    (comp (ref "IC1")
      (value "MBI5041-GP")
      (footprint "eagle-import:SSOP24-150-0.635")
      (libsource (lib "eagle-import") (part "MBI5041-GP"))
    )
    (comp (ref "IC2")
      (value "ATTINY(261/461/861)V-MAZ")
      (footprint "eagle-import:QFN-20")
      (libsource (lib "eagle-import") (part "ATTINY(261/461/861)V-MAZ"))
    )
    (comp (ref "LED61")
      (value "INND-TS40AB")
      (footprint "eagle-import:7SEG-13")
      (libsource (lib "eagle-import") (part "INND-TS40AB"))
    )
    (comp (ref "LED62")
      (value "INND-TS40AB")
      (footprint "eagle-import:7SEG-13")
      (libsource (lib "eagle-import") (part "INND-TS40AB"))
    )
    (comp (ref "Q1")
      (value "DUAL_BJT_NPN_BIAS-PUMH2")
      (footprint "eagle-import:SOT-363(SC-88)")
      (fields (field (name "MF") "Nexperia") (field (name "MPN") "PUMH2,115"))
      (libsource (lib "eagle-import") (part "DUAL_BJT_NPN_BIAS-PUMH2"))
    )
    (comp (ref "R1")
      (value "WIDERSTAND-0603")
      (footprint "eagle-import:0603")
      (libsource (lib "eagle-import") (part "WIDERSTAND-0603"))
    )
    (comp (ref "R3")
      (value "WIDERSTAND-0603")
      (footprint "eagle-import:0603")
      (libsource (lib "eagle-import") (part "WIDERSTAND-0603"))
    )
    (comp (ref "R5")
      (value "WIDERSTAND-0603")
      (footprint "eagle-import:0603")
      (libsource (lib "eagle-import") (part "WIDERSTAND-0603"))
    )
    (comp (ref "R6")
      (value "WIDERSTAND-0603")
      (footprint "eagle-import:0603")
      (libsource (lib "eagle-import") (part "WIDERSTAND-0603"))
    )
    (comp (ref "R7")
      (value "WIDERSTAND-0603")
      (footprint "eagle-import:0603")
      (libsource (lib "eagle-import") (part "WIDERSTAND-0603"))
    )
    (comp (ref "R8")
      (value "WIDERSTAND-0603")
      (footprint "eagle-import:0603")
      (libsource (lib "eagle-import") (part "WIDERSTAND-0603"))
    )
    (comp (ref "R285")
      (value "WIDERSTAND-0603")
      (footprint "eagle-import:0603")
      (libsource (lib "eagle-import") (part "WIDERSTAND-0603"))
    )
    (comp (ref "R286")
      (value "WIDERSTAND-0603")
      (footprint "eagle-import:0603")
      (libsource (lib "eagle-import") (part "WIDERSTAND-0603"))
    )
    (comp (ref "R287")
      (value "WIDERSTAND-0603")
      (footprint "eagle-import:0603")
      (libsource (lib "eagle-import") (part "WIDERSTAND-0603"))
    )
    (comp (ref "TP1")
      (value "TP")
      (footprint "eagle-import:TP[1.5][R]")
      (libsource (lib "eagle-import") (part "TP"))
    )
    (comp (ref "TP2")
      (value "TP")
      (footprint "eagle-import:TP[1.5][R]")
      (libsource (lib "eagle-import") (part "TP"))
    )
    (comp (ref "TP3")
      (value "TP")
      (footprint "eagle-import:TP[1.5][R]")
      (libsource (lib "eagle-import") (part "TP"))
    )
    (comp (ref "TP4")
      (value "TP")
      (footprint "eagle-import:TP[1.5][R]")
      (libsource (lib "eagle-import") (part "TP"))
    )
    (comp (ref "TP5")
      (value "TP")
      (footprint "eagle-import:TP[1.5][R]")
      (libsource (lib "eagle-import") (part "TP"))
    )
    (comp (ref "TP6")
      (value "TP")
      (footprint "eagle-import:TP[1.5][R]")
      (libsource (lib "eagle-import") (part "TP"))
    )
    (comp (ref "X2")
      (value "JP8ER")
      (footprint "eagle-import:JP8")
      (libsource (lib "eagle-import") (part "JP8ER"))
    )
  )
  (nets
    (net (code "1") (name "A1") (class "Default")
      (node (ref "IC1") (pin "13") (pinfunction "OUT8_13") (pintype "open_collector"))
      (node (ref "LED62") (pin "10") (pinfunction "A_10") (pintype "passive"))
    )
    (net (code "2") (name "A2") (class "Default")
      (node (ref "IC1") (pin "8") (pinfunction "OUT3_8") (pintype "open_collector"))
      (node (ref "LED61") (pin "10") (pinfunction "A_10") (pintype "passive"))
    )
    (net (code "3") (name "B1") (class "Default")
      (node (ref "IC1") (pin "14") (pinfunction "OUT9_14") (pintype "open_collector"))
      (node (ref "LED62") (pin "9") (pinfunction "B_9") (pintype "passive"))
    )
    (net (code "4") (name "B2") (class "Default")
      (node (ref "IC1") (pin "7") (pinfunction "OUT2_7") (pintype "open_collector"))
      (node (ref "LED61") (pin "9") (pinfunction "B_9") (pintype "passive"))
    )
    (net (code "5") (name "C1") (class "Default")
      (node (ref "IC1") (pin "15") (pinfunction "OUT10_15") (pintype "open_collector"))
      (node (ref "LED62") (pin "8") (pinfunction "C_8") (pintype "passive"))
    )
    (net (code "6") (name "C2") (class "Default")
      (node (ref "IC1") (pin "6") (pinfunction "OUT1_6") (pintype "open_collector"))
      (node (ref "LED61") (pin "8") (pinfunction "C_8") (pintype "passive"))
    )
    (net (code "7") (name "D1") (class "Default")
      (node (ref "IC1") (pin "17") (pinfunction "OUT12_17") (pintype "open_collector"))
      (node (ref "LED62") (pin "5") (pinfunction "D_5") (pintype "passive"))
    )
    (net (code "8") (name "D2") (class "Default")
      (node (ref "IC1") (pin "9") (pinfunction "OUT4_9") (pintype "open_collector"))
      (node (ref "LED61") (pin "5") (pinfunction "D_5") (pintype "passive"))
    )
    (net (code "9") (name "E1") (class "Default")
      (node (ref "IC1") (pin "18") (pinfunction "OUT13_18") (pintype "open_collector"))
      (node (ref "LED62") (pin "1") (pinfunction "E_1") (pintype "passive"))
    )
    (net (code "10") (name "E2") (class "Default")
      (node (ref "IC1") (pin "12") (pinfunction "OUT7_12") (pintype "open_collector"))
      (node (ref "LED61") (pin "1") (pinfunction "E_1") (pintype "passive"))
    )
    (net (code "11") (name "F1") (class "Default")
      (node (ref "IC1") (pin "19") (pinfunction "OUT14_19") (pintype "open_collector"))
      (node (ref "LED62") (pin "2") (pinfunction "F_2") (pintype "passive"))
    )
    (net (code "12") (name "F2") (class "Default")
      (node (ref "IC1") (pin "11") (pinfunction "OUT6_11") (pintype "open_collector"))
      (node (ref "LED61") (pin "2") (pinfunction "F_2") (pintype "passive"))
    )
    (net (code "13") (name "G1") (class "Default")
      (node (ref "IC1") (pin "20") (pinfunction "OUT15_20") (pintype "open_collector"))
      (node (ref "LED62") (pin "3") (pinfunction "G_3") (pintype "passive"))
    )
    (net (code "14") (name "G2") (class "Default")
      (node (ref "IC1") (pin "10") (pinfunction "OUT5_10") (pintype "open_collector"))
      (node (ref "LED61") (pin "3") (pinfunction "G_3") (pintype "passive"))
    )
    (net (code "15") (name "GCLK") (class "Default")
      (node (ref "IC1") (pin "21") (pinfunction "GCLK_21") (pintype "input"))
      (node (ref "IC2") (pin "6") (pinfunction "(CTAL2/CLKO/ADC8/OC1D/PCINT13)PB5_6") (pintype "bidirectional"))
    )
    (net (code "16") (name "GND") (class "Default")
      (node (ref "C1") (pin "P$2") (pinfunction "2_P$2") (pintype "passive"))
      (node (ref "C10") (pin "P$2") (pinfunction "2_P$2") (pintype "passive"))
      (node (ref "C11") (pin "P$2") (pinfunction "2_P$2") (pintype "passive"))
      (node (ref "C12") (pin "P$2") (pinfunction "2_P$2") (pintype "passive"))
      (node (ref "C13") (pin "P$2") (pinfunction "2_P$2") (pintype "passive"))
      (node (ref "C14") (pin "P$2") (pinfunction "2_P$2") (pintype "passive"))
      (node (ref "C15") (pin "P$2") (pinfunction "2_P$2") (pintype "passive"))
      (node (ref "C16") (pin "P$2") (pinfunction "2_P$2") (pintype "passive"))
      (node (ref "C17") (pin "P$2") (pinfunction "2_P$2") (pintype "passive"))
      (node (ref "C18") (pin "P$2") (pinfunction "2_P$2") (pintype "passive"))
      (node (ref "C19") (pin "P$2") (pinfunction "2_P$2") (pintype "passive"))
      (node (ref "C2") (pin "P$2") (pinfunction "2_P$2") (pintype "passive"))
      (node (ref "C20") (pin "P$2") (pinfunction "2_P$2") (pintype "passive"))
      (node (ref "C21") (pin "P$2") (pinfunction "2_P$2") (pintype "passive"))
      (node (ref "C22") (pin "P$2") (pinfunction "2_P$2") (pintype "passive"))
      (node (ref "C23") (pin "P$2") (pinfunction "2_P$2") (pintype "passive"))
      (node (ref "C24") (pin "P$2") (pinfunction "2_P$2") (pintype "passive"))
      (node (ref "C25") (pin "P$2") (pinfunction "2_P$2") (pintype "passive"))
      (node (ref "C26") (pin "P$2") (pinfunction "2_P$2") (pintype "passive"))
      (node (ref "C27") (pin "P$2") (pinfunction "2_P$2") (pintype "passive"))
      (node (ref "C28") (pin "P$2") (pinfunction "2_P$2") (pintype "passive"))
      (node (ref "C29") (pin "P$2") (pinfunction "2_P$2") (pintype "passive"))
      (node (ref "C3") (pin "P$2") (pinfunction "2_P$2") (pintype "passive"))
      (node (ref "C30") (pin "P$2") (pinfunction "2_P$2") (pintype "passive"))
      (node (ref "C31") (pin "P$2") (pinfunction "2_P$2") (pintype "passive"))
      (node (ref "C32") (pin "P$2") (pinfunction "2_P$2") (pintype "passive"))
      (node (ref "C33") (pin "P$2") (pinfunction "2_P$2") (pintype "passive"))
      (node (ref "C34") (pin "P$2") (pinfunction "2_P$2") (pintype "passive"))
      (node (ref "C35") (pin "P$2") (pinfunction "2_P$2") (pintype "passive"))
      (node (ref "C36") (pin "P$2") (pinfunction "2_P$2") (pintype "passive"))
      (node (ref "C37") (pin "P$2") (pinfunction "2_P$2") (pintype "passive"))
      (node (ref "C38") (pin "P$2") (pinfunction "2_P$2") (pintype "passive"))
      (node (ref "C39") (pin "P$2") (pinfunction "2_P$2") (pintype "passive"))
      (node (ref "C4") (pin "P$2") (pinfunction "2_P$2") (pintype "passive"))
      (node (ref "C40") (pin "P$2") (pinfunction "2_P$2") (pintype "passive"))
      (node (ref "C41") (pin "P$2") (pinfunction "2_P$2") (pintype "passive"))
      (node (ref "C42") (pin "P$2") (pinfunction "2_P$2") (pintype "passive"))
      (node (ref "C43") (pin "P$2") (pinfunction "2_P$2") (pintype "passive"))
      (node (ref "C44") (pin "P$2") (pinfunction "2_P$2") (pintype "passive"))
      (node (ref "C45") (pin "P$2") (pinfunction "2_P$2") (pintype "passive"))
      (node (ref "C46") (pin "P$2") (pinfunction "2_P$2") (pintype "passive"))
      (node (ref "C47") (pin "P$2") (pinfunction "2_P$2") (pintype "passive"))
      (node (ref "C48") (pin "P$2") (pinfunction "2_P$2") (pintype "passive"))
      (node (ref "C49") (pin "P$2") (pinfunction "2_P$2") (pintype "passive"))
      (node (ref "C5") (pin "P$2") (pinfunction "2_P$2") (pintype "passive"))
      (node (ref "C50") (pin "P$2") (pinfunction "2_P$2") (pintype "passive"))
      (node (ref "C51") (pin "P$2") (pinfunction "2_P$2") (pintype "passive"))
      (node (ref "C52") (pin "P$2") (pinfunction "2_P$2") (pintype "passive"))
      (node (ref "C53") (pin "P$2") (pinfunction "2_P$2") (pintype "passive"))
      (node (ref "C54") (pin "P$2") (pinfunction "2_P$2") (pintype "passive"))
      (node (ref "C55") (pin "P$2") (pinfunction "2_P$2") (pintype "passive"))
      (node (ref "C56") (pin "P$2") (pinfunction "2_P$2") (pintype "passive"))
      (node (ref "C57") (pin "P$2") (pinfunction "2_P$2") (pintype "passive"))
      (node (ref "C58") (pin "P$2") (pinfunction "2_P$2") (pintype "passive"))
      (node (ref "C59") (pin "P$2") (pinfunction "2_P$2") (pintype "passive"))
      (node (ref "C6") (pin "P$2") (pinfunction "2_P$2") (pintype "passive"))
      (node (ref "C60") (pin "P$2") (pinfunction "2_P$2") (pintype "passive"))
      (node (ref "C61") (pin "P$2") (pinfunction "2_P$2") (pintype "passive"))
      (node (ref "C62") (pin "P$2") (pinfunction "2_P$2") (pintype "passive"))
      (node (ref "C63") (pin "P$2") (pinfunction "2_P$2") (pintype "passive"))
      (node (ref "C7") (pin "P$2") (pinfunction "2_P$2") (pintype "passive"))
      (node (ref "C8") (pin "P$2") (pinfunction "2_P$2") (pintype "passive"))
      (node (ref "C9") (pin "P$2") (pinfunction "2_P$2") (pintype "passive"))
      (node (ref "IC1") (pin "1") (pinfunction "GND_1") (pintype "power_in"))
      (node (ref "IC2") (pin "14") (pinfunction "AGND_14") (pintype "bidirectional"))
      (node (ref "IC2") (pin "4") (pinfunction "GND_4") (pintype "bidirectional"))
      (node (ref "IC2") (pin "PAD") (pinfunction "GND_PAD") (pintype "bidirectional"))
      (node (ref "IC2") (pin "PAD$1") (pinfunction "GND_PAD$1") (pintype "bidirectional"))
      (node (ref "IC2") (pin "PAD$2") (pinfunction "GND_PAD$2") (pintype "bidirectional"))
      (node (ref "IC2") (pin "PAD$3") (pinfunction "GND_PAD$3") (pintype "bidirectional"))
      (node (ref "IC2") (pin "PAD$4") (pinfunction "GND_PAD$4") (pintype "bidirectional"))
      (node (ref "IC2") (pin "PAD$5") (pinfunction "GND_PAD$5") (pintype "bidirectional"))
      (node (ref "LED1") (pin "GND") (pinfunction "GND_GND") (pintype "power_in"))
      (node (ref "LED10") (pin "GND") (pinfunction "GND_GND") (pintype "power_in"))
      (node (ref "LED11") (pin "GND") (pinfunction "GND_GND") (pintype "power_in"))
      (node (ref "LED12") (pin "GND") (pinfunction "GND_GND") (pintype "power_in"))
      (node (ref "LED13") (pin "GND") (pinfunction "GND_GND") (pintype "power_in"))
      (node (ref "LED14") (pin "GND") (pinfunction "GND_GND") (pintype "power_in"))
      (node (ref "LED15") (pin "GND") (pinfunction "GND_GND") (pintype "power_in"))
      (node (ref "LED16") (pin "GND") (pinfunction "GND_GND") (pintype "power_in"))
      (node (ref "LED17") (pin "GND") (pinfunction "GND_GND") (pintype "power_in"))
      (node (ref "LED18") (pin "GND") (pinfunction "GND_GND") (pintype "power_in"))
      (node (ref "LED19") (pin "GND") (pinfunction "GND_GND") (pintype "power_in"))
      (node (ref "LED2") (pin "GND") (pinfunction "GND_GND") (pintype "power_in"))
      (node (ref "LED20") (pin "GND") (pinfunction "GND_GND") (pintype "power_in"))
      (node (ref "LED21") (pin "GND") (pinfunction "GND_GND") (pintype "power_in"))
      (node (ref "LED22") (pin "GND") (pinfunction "GND_GND") (pintype "power_in"))
      (node (ref "LED23") (pin "GND") (pinfunction "GND_GND") (pintype "power_in"))
      (node (ref "LED24") (pin "GND") (pinfunction "GND_GND") (pintype "power_in"))
      (node (ref "LED25") (pin "GND") (pinfunction "GND_GND") (pintype "power_in"))
      (node (ref "LED26") (pin "GND") (pinfunction "GND_GND") (pintype "power_in"))
      (node (ref "LED27") (pin "GND") (pinfunction "GND_GND") (pintype "power_in"))
      (node (ref "LED28") (pin "GND") (pinfunction "GND_GND") (pintype "power_in"))
      (node (ref "LED29") (pin "GND") (pinfunction "GND_GND") (pintype "power_in"))
      (node (ref "LED3") (pin "GND") (pinfunction "GND_GND") (pintype "power_in"))
      (node (ref "LED30") (pin "GND") (pinfunction "GND_GND") (pintype "power_in"))
      (node (ref "LED31") (pin "GND") (pinfunction "GND_GND") (pintype "power_in"))
      (node (ref "LED32") (pin "GND") (pinfunction "GND_GND") (pintype "power_in"))
      (node (ref "LED33") (pin "GND") (pinfunction "GND_GND") (pintype "power_in"))
      (node (ref "LED34") (pin "GND") (pinfunction "GND_GND") (pintype "power_in"))
      (node (ref "LED35") (pin "GND") (pinfunction "GND_GND") (pintype "power_in"))
      (node (ref "LED36") (pin "GND") (pinfunction "GND_GND") (pintype "power_in"))
      (node (ref "LED37") (pin "GND") (pinfunction "GND_GND") (pintype "power_in"))
      (node (ref "LED38") (pin "GND") (pinfunction "GND_GND") (pintype "power_in"))
      (node (ref "LED39") (pin "GND") (pinfunction "GND_GND") (pintype "power_in"))
      (node (ref "LED4") (pin "GND") (pinfunction "GND_GND") (pintype "power_in"))
      (node (ref "LED40") (pin "GND") (pinfunction "GND_GND") (pintype "power_in"))
      (node (ref "LED41") (pin "GND") (pinfunction "GND_GND") (pintype "power_in"))
      (node (ref "LED42") (pin "GND") (pinfunction "GND_GND") (pintype "power_in"))
      (node (ref "LED43") (pin "GND") (pinfunction "GND_GND") (pintype "power_in"))
      (node (ref "LED44") (pin "GND") (pinfunction "GND_GND") (pintype "power_in"))
      (node (ref "LED45") (pin "GND") (pinfunction "GND_GND") (pintype "power_in"))
      (node (ref "LED46") (pin "GND") (pinfunction "GND_GND") (pintype "power_in"))
      (node (ref "LED47") (pin "GND") (pinfunction "GND_GND") (pintype "power_in"))
      (node (ref "LED48") (pin "GND") (pinfunction "GND_GND") (pintype "power_in"))
      (node (ref "LED49") (pin "GND") (pinfunction "GND_GND") (pintype "power_in"))
      (node (ref "LED5") (pin "GND") (pinfunction "GND_GND") (pintype "power_in"))
      (node (ref "LED50") (pin "GND") (pinfunction "GND_GND") (pintype "power_in"))
      (node (ref "LED51") (pin "GND") (pinfunction "GND_GND") (pintype "power_in"))
      (node (ref "LED52") (pin "GND") (pinfunction "GND_GND") (pintype "power_in"))
      (node (ref "LED53") (pin "GND") (pinfunction "GND_GND") (pintype "power_in"))
      (node (ref "LED54") (pin "GND") (pinfunction "GND_GND") (pintype "power_in"))
      (node (ref "LED55") (pin "GND") (pinfunction "GND_GND") (pintype "power_in"))
      (node (ref "LED56") (pin "GND") (pinfunction "GND_GND") (pintype "power_in"))
      (node (ref "LED57") (pin "GND") (pinfunction "GND_GND") (pintype "power_in"))
      (node (ref "LED58") (pin "GND") (pinfunction "GND_GND") (pintype "power_in"))
      (node (ref "LED59") (pin "GND") (pinfunction "GND_GND") (pintype "power_in"))
      (node (ref "LED6") (pin "GND") (pinfunction "GND_GND") (pintype "power_in"))
      (node (ref "LED60") (pin "GND") (pinfunction "GND_GND") (pintype "power_in"))
      (node (ref "LED7") (pin "GND") (pinfunction "GND_GND") (pintype "power_in"))
      (node (ref "LED8") (pin "GND") (pinfunction "GND_GND") (pintype "power_in"))
      (node (ref "LED9") (pin "GND") (pinfunction "GND_GND") (pintype "power_in"))
      (node (ref "Q1") (pin "1") (pinfunction "E_1") (pintype "passive"))
      (node (ref "Q1") (pin "4") (pinfunction "E_4") (pintype "passive"))
      (node (ref "R1") (pin "P$1") (pinfunction "1_P$1") (pintype "passive"))
      (node (ref "R3") (pin "P$1") (pinfunction "1_P$1") (pintype "passive"))
      (node (ref "R5") (pin "P$1") (pinfunction "1_P$1") (pintype "passive"))
      (node (ref "TP6") (pin "P$1") (pinfunction "P$1_P$1") (pintype "bidirectional"))
      (node (ref "X2") (pin "7") (pinfunction "7_7") (pintype "passive"))
      (node (ref "X2") (pin "8") (pinfunction "8_8") (pintype "passive"))
    )
    (net (code "17") (name "H1") (class "Default")
      (node (ref "IC1") (pin "16") (pinfunction "OUT11_16") (pintype "open_collector"))
      (node (ref "LED62") (pin "7") (pinfunction "DP_7") (pintype "passive"))
    )
    (net (code "18") (name "H2") (class "Default")
      (node (ref "IC1") (pin "5") (pinfunction "OUT0_5") (pintype "open_collector"))
      (node (ref "LED61") (pin "7") (pinfunction "DP_7") (pintype "passive"))
    )
    (net (code "19") (name "ID-SENSE") (class "Default")
      (node (ref "IC2") (pin "5") (pinfunction "(XTAL1/CLKI/ADC7/~{OC1D}/PCINT12)PB4_5") (pintype "bidirectional"))
      (node (ref "R1") (pin "P$2") (pinfunction "2_P$2") (pintype "passive"))
      (node (ref "R3") (pin "P$2") (pinfunction "2_P$2") (pintype "passive"))
      (node (ref "X2") (pin "6") (pinfunction "6_6") (pintype "passive"))
    )
    (net (code "20") (name "IN1") (class "Default")
      (node (ref "LED1") (pin "DIN") (pinfunction "DIN_DIN") (pintype "input"))
      (node (ref "R13") (pin "P$2") (pinfunction "2_P$2") (pintype "passive"))
      (node (ref "R15") (pin "P$2") (pinfunction "2_P$2") (pintype "passive"))
      (node (ref "R277") (pin "P$2") (pinfunction "2_P$2") (pintype "passive"))
    )
    (net (code "21") (name "IN2") (class "Default")
      (node (ref "LED2") (pin "DIN") (pinfunction "DIN_DIN") (pintype "input"))
      (node (ref "R11") (pin "P$2") (pinfunction "2_P$2") (pintype "passive"))
      (node (ref "R276") (pin "P$2") (pinfunction "2_P$2") (pintype "passive"))
      (node (ref "R28") (pin "P$2") (pinfunction "2_P$2") (pintype "passive"))
      (node (ref "R35") (pin "P$2") (pinfunction "2_P$2") (pintype "passive"))
    )
    (net (code "22") (name "IN3") (class "Default")
      (node (ref "LED3") (pin "DIN") (pinfunction "DIN_DIN") (pintype "input"))
      (node (ref "R19") (pin "P$2") (pinfunction "2_P$2") (pintype "passive"))
      (node (ref "R22") (pin "P$2") (pinfunction "2_P$2") (pintype "passive"))
      (node (ref "R275") (pin "P$2") (pinfunction "2_P$2") (pintype "passive"))
      (node (ref "R38") (pin "P$2") (pinfunction "2_P$2") (pintype "passive"))
    )
    (net (code "23") (name "IN4") (class "Default")
      (node (ref "LED4") (pin "DIN") (pinfunction "DIN_DIN") (pintype "input"))
      (node (ref "R274") (pin "P$2") (pinfunction "2_P$2") (pintype "passive"))
      (node (ref "R30") (pin "P$2") (pinfunction "2_P$2") (pintype "passive"))
      (node (ref "R37") (pin "P$2") (pinfunction "2_P$2") (pintype "passive"))
      (node (ref "R41") (pin "P$2") (pinfunction "2_P$2") (pintype "passive"))
    )
    (net (code "24") (name "IN5") (class "Default")
      (node (ref "LED5") (pin "DIN") (pinfunction "DIN_DIN") (pintype "input"))
      (node (ref "R273") (pin "P$2") (pinfunction "2_P$2") (pintype "passive"))
      (node (ref "R40") (pin "P$2") (pinfunction "2_P$2") (pintype "passive"))
      (node (ref "R44") (pin "P$2") (pinfunction "2_P$2") (pintype "passive"))
      (node (ref "R48") (pin "P$2") (pinfunction "2_P$2") (pintype "passive"))
    )
    (net (code "25") (name "IN6") (class "Default")
      (node (ref "LED6") (pin "DIN") (pinfunction "DIN_DIN") (pintype "input"))
      (node (ref "R272") (pin "P$2") (pinfunction "2_P$2") (pintype "passive"))
      (node (ref "R43") (pin "P$2") (pinfunction "2_P$2") (pintype "passive"))
      (node (ref "R52") (pin "P$2") (pinfunction "2_P$2") (pintype "passive"))
    )
    (net (code "26") (name "IN7") (class "Default")
      (node (ref "LED7") (pin "DIN") (pinfunction "DIN_DIN") (pintype "input"))
      (node (ref "R18") (pin "P$2") (pinfunction "2_P$2") (pintype "passive"))
      (node (ref "R269") (pin "P$2") (pinfunction "2_P$2") (pintype "passive"))
      (node (ref "R33") (pin "P$2") (pinfunction "2_P$2") (pintype "passive"))
      (node (ref "R9") (pin "P$2") (pinfunction "2_P$2") (pintype "passive"))
    )
    (net (code "27") (name "IN8") (class "Default")
      (node (ref "LED8") (pin "DIN") (pinfunction "DIN_DIN") (pintype "input"))
      (node (ref "R16") (pin "P$2") (pinfunction "2_P$2") (pintype "passive"))
      (node (ref "R17") (pin "P$2") (pinfunction "2_P$2") (pintype "passive"))
      (node (ref "R20") (pin "P$2") (pinfunction "2_P$2") (pintype "passive"))
      (node (ref "R26") (pin "P$2") (pinfunction "2_P$2") (pintype "passive"))
      (node (ref "R268") (pin "P$2") (pinfunction "2_P$2") (pintype "passive"))
    )
    (net (code "28") (name "IN9") (class "Default")
      (node (ref "LED9") (pin "DIN") (pinfunction "DIN_DIN") (pintype "input"))
      (node (ref "R12") (pin "P$2") (pinfunction "2_P$2") (pintype "passive"))
      (node (ref "R267") (pin "P$2") (pinfunction "2_P$2") (pintype "passive"))
      (node (ref "R36") (pin "P$2") (pinfunction "2_P$2") (pintype "passive"))
      (node (ref "R4") (pin "P$2") (pinfunction "2_P$2") (pintype "passive"))
      (node (ref "R69") (pin "P$2") (pinfunction "2_P$2") (pintype "passive"))
    )
    (net (code "29") (name "IN10") (class "Default")
      (node (ref "LED10") (pin "DIN") (pinfunction "DIN_DIN") (pintype "input"))
      (node (ref "R23") (pin "P$2") (pinfunction "2_P$2") (pintype "passive"))
      (node (ref "R266") (pin "P$2") (pinfunction "2_P$2") (pintype "passive"))
      (node (ref "R39") (pin "P$2") (pinfunction "2_P$2") (pintype "passive"))
      (node (ref "R46") (pin "P$2") (pinfunction "2_P$2") (pintype "passive"))
      (node (ref "R73") (pin "P$2") (pinfunction "2_P$2") (pintype "passive"))
    )
    (net (code "30") (name "IN11") (class "Default")
      (node (ref "LED11") (pin "DIN") (pinfunction "DIN_DIN") (pintype "input"))
      (node (ref "R265") (pin "P$2") (pinfunction "2_P$2") (pintype "passive"))
      (node (ref "R31") (pin "P$2") (pinfunction "2_P$2") (pintype "passive"))
      (node (ref "R42") (pin "P$2") (pinfunction "2_P$2") (pintype "passive"))
      (node (ref "R50") (pin "P$2") (pinfunction "2_P$2") (pintype "passive"))
      (node (ref "R77") (pin "P$2") (pinfunction "2_P$2") (pintype "passive"))
    )
    (net (code "31") (name "IN12") (class "Default")
      (node (ref "LED12") (pin "DIN") (pinfunction "DIN_DIN") (pintype "input"))
      (node (ref "R264") (pin "P$2") (pinfunction "2_P$2") (pintype "passive"))
      (node (ref "R45") (pin "P$2") (pinfunction "2_P$2") (pintype "passive"))
      (node (ref "R49") (pin "P$2") (pinfunction "2_P$2") (pintype "passive"))
      (node (ref "R81") (pin "P$2") (pinfunction "2_P$2") (pintype "passive"))
    )
    (net (code "32") (name "IN13") (class "Default")
      (node (ref "LED13") (pin "DIN") (pinfunction "DIN_DIN") (pintype "input"))
      (node (ref "R14") (pin "P$2") (pinfunction "2_P$2") (pintype "passive"))
      (node (ref "R24") (pin "P$2") (pinfunction "2_P$2") (pintype "passive"))
      (node (ref "R263") (pin "P$2") (pinfunction "2_P$2") (pintype "passive"))
      (node (ref "R54") (pin "P$2") (pinfunction "2_P$2") (pintype "passive"))
    )
    (net (code "33") (name "IN14") (class "Default")
      (node (ref "LED14") (pin "DIN") (pinfunction "DIN_DIN") (pintype "input"))
      (node (ref "R10") (pin "P$2") (pinfunction "2_P$2") (pintype "passive"))
      (node (ref "R262") (pin "P$2") (pinfunction "2_P$2") (pintype "passive"))
      (node (ref "R34") (pin "P$2") (pinfunction "2_P$2") (pintype "passive"))
      (node (ref "R65") (pin "P$2") (pinfunction "2_P$2") (pintype "passive"))
      (node (ref "R90") (pin "P$2") (pinfunction "2_P$2") (pintype "passive"))
    )
    (net (code "34") (name "IN15") (class "Default")
      (node (ref "LED15") (pin "DIN") (pinfunction "DIN_DIN") (pintype "input"))
      (node (ref "R109") (pin "P$2") (pinfunction "2_P$2") (pintype "passive"))
      (node (ref "R21") (pin "P$2") (pinfunction "2_P$2") (pintype "passive"))
      (node (ref "R261") (pin "P$2") (pinfunction "2_P$2") (pintype "passive"))
      (node (ref "R27") (pin "P$2") (pinfunction "2_P$2") (pintype "passive"))
      (node (ref "R71") (pin "P$2") (pinfunction "2_P$2") (pintype "passive"))
    )
    (net (code "35") (name "IN16") (class "Default")
      (node (ref "LED16") (pin "DIN") (pinfunction "DIN_DIN") (pintype "input"))
      (node (ref "R113") (pin "P$2") (pinfunction "2_P$2") (pintype "passive"))
      (node (ref "R260") (pin "P$2") (pinfunction "2_P$2") (pintype "passive"))
      (node (ref "R29") (pin "P$2") (pinfunction "2_P$2") (pintype "passive"))
      (node (ref "R70") (pin "P$2") (pinfunction "2_P$2") (pintype "passive"))
      (node (ref "R75") (pin "P$2") (pinfunction "2_P$2") (pintype "passive"))
    )
    (net (code "36") (name "IN17") (class "Default")
      (node (ref "LED17") (pin "DIN") (pinfunction "DIN_DIN") (pintype "input"))
      (node (ref "R117") (pin "P$2") (pinfunction "2_P$2") (pintype "passive"))
      (node (ref "R259") (pin "P$2") (pinfunction "2_P$2") (pintype "passive"))
      (node (ref "R47") (pin "P$2") (pinfunction "2_P$2") (pintype "passive"))
      (node (ref "R74") (pin "P$2") (pinfunction "2_P$2") (pintype "passive"))
      (node (ref "R79") (pin "P$2") (pinfunction "2_P$2") (pintype "passive"))
    )
    (net (code "37") (name "IN18") (class "Default")
      (node (ref "LED18") (pin "DIN") (pinfunction "DIN_DIN") (pintype "input"))
      (node (ref "R121") (pin "P$2") (pinfunction "2_P$2") (pintype "passive"))
      (node (ref "R258") (pin "P$2") (pinfunction "2_P$2") (pintype "passive"))
      (node (ref "R51") (pin "P$2") (pinfunction "2_P$2") (pintype "passive"))
      (node (ref "R78") (pin "P$2") (pinfunction "2_P$2") (pintype "passive"))
      (node (ref "R83") (pin "P$2") (pinfunction "2_P$2") (pintype "passive"))
    )
    (net (code "38") (name "IN19") (class "Default")
      (node (ref "LED19") (pin "DIN") (pinfunction "DIN_DIN") (pintype "input"))
      (node (ref "R125") (pin "P$2") (pinfunction "2_P$2") (pintype "passive"))
      (node (ref "R257") (pin "P$2") (pinfunction "2_P$2") (pintype "passive"))
      (node (ref "R82") (pin "P$2") (pinfunction "2_P$2") (pintype "passive"))
      (node (ref "R87") (pin "P$2") (pinfunction "2_P$2") (pintype "passive"))
    )
    (net (code "39") (name "IN20") (class "Default")
      (node (ref "LED20") (pin "DIN") (pinfunction "DIN_DIN") (pintype "input"))
      (node (ref "R129") (pin "P$2") (pinfunction "2_P$2") (pintype "passive"))
      (node (ref "R256") (pin "P$2") (pinfunction "2_P$2") (pintype "passive"))
      (node (ref "R86") (pin "P$2") (pinfunction "2_P$2") (pintype "passive"))
    )
    (net (code "40") (name "IN21") (class "Default")
      (node (ref "LED21") (pin "DIN") (pinfunction "DIN_DIN") (pintype "input"))
      (node (ref "R255") (pin "P$2") (pinfunction "2_P$2") (pintype "passive"))
      (node (ref "R32") (pin "P$2") (pinfunction "2_P$2") (pintype "passive"))
      (node (ref "R57") (pin "P$2") (pinfunction "2_P$2") (pintype "passive"))
      (node (ref "R85") (pin "P$2") (pinfunction "2_P$2") (pintype "passive"))
    )
    (net (code "41") (name "IN22") (class "Default")
      (node (ref "LED22") (pin "DIN") (pinfunction "DIN_DIN") (pintype "input"))
      (node (ref "R107") (pin "P$2") (pinfunction "2_P$2") (pintype "passive"))
      (node (ref "R25") (pin "P$2") (pinfunction "2_P$2") (pintype "passive"))
      (node (ref "R254") (pin "P$2") (pinfunction "2_P$2") (pintype "passive"))
      (node (ref "R55") (pin "P$2") (pinfunction "2_P$2") (pintype "passive"))
      (node (ref "R94") (pin "P$2") (pinfunction "2_P$2") (pintype "passive"))
    )
    (net (code "42") (name "IN23") (class "Default")
      (node (ref "LED23") (pin "DIN") (pinfunction "DIN_DIN") (pintype "input"))
      (node (ref "R111") (pin "P$2") (pinfunction "2_P$2") (pintype "passive"))
      (node (ref "R132") (pin "P$2") (pinfunction "2_P$2") (pintype "passive"))
      (node (ref "R253") (pin "P$2") (pinfunction "2_P$2") (pintype "passive"))
      (node (ref "R68") (pin "P$2") (pinfunction "2_P$2") (pintype "passive"))
      (node (ref "R91") (pin "P$2") (pinfunction "2_P$2") (pintype "passive"))
    )
    (net (code "43") (name "IN24") (class "Default")
      (node (ref "LED24") (pin "DIN") (pinfunction "DIN_DIN") (pintype "input"))
      (node (ref "R110") (pin "P$2") (pinfunction "2_P$2") (pintype "passive"))
      (node (ref "R115") (pin "P$2") (pinfunction "2_P$2") (pintype "passive"))
      (node (ref "R136") (pin "P$2") (pinfunction "2_P$2") (pintype "passive"))
      (node (ref "R252") (pin "P$2") (pinfunction "2_P$2") (pintype "passive"))
      (node (ref "R72") (pin "P$2") (pinfunction "2_P$2") (pintype "passive"))
    )
    (net (code "44") (name "IN25") (class "Default")
      (node (ref "LED25") (pin "DIN") (pinfunction "DIN_DIN") (pintype "input"))
      (node (ref "R114") (pin "P$2") (pinfunction "2_P$2") (pintype "passive"))
      (node (ref "R119") (pin "P$2") (pinfunction "2_P$2") (pintype "passive"))
      (node (ref "R140") (pin "P$2") (pinfunction "2_P$2") (pintype "passive"))
      (node (ref "R251") (pin "P$2") (pinfunction "2_P$2") (pintype "passive"))
      (node (ref "R76") (pin "P$2") (pinfunction "2_P$2") (pintype "passive"))
    )
    (net (code "45") (name "IN26") (class "Default")
      (node (ref "LED26") (pin "DIN") (pinfunction "DIN_DIN") (pintype "input"))
      (node (ref "R118") (pin "P$2") (pinfunction "2_P$2") (pintype "passive"))
      (node (ref "R123") (pin "P$2") (pinfunction "2_P$2") (pintype "passive"))
      (node (ref "R144") (pin "P$2") (pinfunction "2_P$2") (pintype "passive"))
      (node (ref "R250") (pin "P$2") (pinfunction "2_P$2") (pintype "passive"))
      (node (ref "R80") (pin "P$2") (pinfunction "2_P$2") (pintype "passive"))
    )
    (net (code "46") (name "IN27") (class "Default")
      (node (ref "LED27") (pin "DIN") (pinfunction "DIN_DIN") (pintype "input"))
      (node (ref "R122") (pin "P$2") (pinfunction "2_P$2") (pintype "passive"))
      (node (ref "R127") (pin "P$2") (pinfunction "2_P$2") (pintype "passive"))
      (node (ref "R148") (pin "P$2") (pinfunction "2_P$2") (pintype "passive"))
      (node (ref "R249") (pin "P$2") (pinfunction "2_P$2") (pintype "passive"))
      (node (ref "R84") (pin "P$2") (pinfunction "2_P$2") (pintype "passive"))
    )
    (net (code "47") (name "IN28") (class "Default")
      (node (ref "LED28") (pin "DIN") (pinfunction "DIN_DIN") (pintype "input"))
      (node (ref "R126") (pin "P$2") (pinfunction "2_P$2") (pintype "passive"))
      (node (ref "R152") (pin "P$2") (pinfunction "2_P$2") (pintype "passive"))
      (node (ref "R248") (pin "P$2") (pinfunction "2_P$2") (pintype "passive"))
      (node (ref "R88") (pin "P$2") (pinfunction "2_P$2") (pintype "passive"))
    )
    (net (code "48") (name "IN29") (class "Default")
      (node (ref "LED29") (pin "DIN") (pinfunction "DIN_DIN") (pintype "input"))
      (node (ref "R247") (pin "P$2") (pinfunction "2_P$2") (pintype "passive"))
      (node (ref "R53") (pin "P$2") (pinfunction "2_P$2") (pintype "passive"))
      (node (ref "R60") (pin "P$2") (pinfunction "2_P$2") (pintype "passive"))
      (node (ref "R92") (pin "P$2") (pinfunction "2_P$2") (pintype "passive"))
    )
    (net (code "49") (name "IN30") (class "Default")
      (node (ref "LED30") (pin "DIN") (pinfunction "DIN_DIN") (pintype "input"))
      (node (ref "R130") (pin "P$2") (pinfunction "2_P$2") (pintype "passive"))
      (node (ref "R246") (pin "P$2") (pinfunction "2_P$2") (pintype "passive"))
      (node (ref "R58") (pin "P$2") (pinfunction "2_P$2") (pintype "passive"))
      (node (ref "R89") (pin "P$2") (pinfunction "2_P$2") (pintype "passive"))
      (node (ref "R98") (pin "P$2") (pinfunction "2_P$2") (pintype "passive"))
    )
    (net (code "50") (name "IN31") (class "Default")
      (node (ref "LED31") (pin "DIN") (pinfunction "DIN_DIN") (pintype "input"))
      (node (ref "R108") (pin "P$2") (pinfunction "2_P$2") (pintype "passive"))
      (node (ref "R134") (pin "P$2") (pinfunction "2_P$2") (pintype "passive"))
      (node (ref "R155") (pin "P$2") (pinfunction "2_P$2") (pintype "passive"))
      (node (ref "R245") (pin "P$2") (pinfunction "2_P$2") (pintype "passive"))
      (node (ref "R95") (pin "P$2") (pinfunction "2_P$2") (pintype "passive"))
    )
    (net (code "51") (name "IN32") (class "Default")
      (node (ref "LED32") (pin "DIN") (pinfunction "DIN_DIN") (pintype "input"))
      (node (ref "R112") (pin "P$2") (pinfunction "2_P$2") (pintype "passive"))
      (node (ref "R133") (pin "P$2") (pinfunction "2_P$2") (pintype "passive"))
      (node (ref "R138") (pin "P$2") (pinfunction "2_P$2") (pintype "passive"))
      (node (ref "R159") (pin "P$2") (pinfunction "2_P$2") (pintype "passive"))
      (node (ref "R244") (pin "P$2") (pinfunction "2_P$2") (pintype "passive"))
    )
    (net (code "52") (name "IN33") (class "Default")
      (node (ref "LED33") (pin "DIN") (pinfunction "DIN_DIN") (pintype "input"))
      (node (ref "R116") (pin "P$2") (pinfunction "2_P$2") (pintype "passive"))
      (node (ref "R137") (pin "P$2") (pinfunction "2_P$2") (pintype "passive"))
      (node (ref "R142") (pin "P$2") (pinfunction "2_P$2") (pintype "passive"))
      (node (ref "R163") (pin "P$2") (pinfunction "2_P$2") (pintype "passive"))
      (node (ref "R243") (pin "P$2") (pinfunction "2_P$2") (pintype "passive"))
    )
    (net (code "53") (name "IN34") (class "Default")
      (node (ref "LED34") (pin "DIN") (pinfunction "DIN_DIN") (pintype "input"))
      (node (ref "R120") (pin "P$2") (pinfunction "2_P$2") (pintype "passive"))
      (node (ref "R141") (pin "P$2") (pinfunction "2_P$2") (pintype "passive"))
      (node (ref "R146") (pin "P$2") (pinfunction "2_P$2") (pintype "passive"))
      (node (ref "R167") (pin "P$2") (pinfunction "2_P$2") (pintype "passive"))
      (node (ref "R242") (pin "P$2") (pinfunction "2_P$2") (pintype "passive"))
    )
    (net (code "54") (name "IN35") (class "Default")
      (node (ref "LED35") (pin "DIN") (pinfunction "DIN_DIN") (pintype "input"))
      (node (ref "R124") (pin "P$2") (pinfunction "2_P$2") (pintype "passive"))
      (node (ref "R145") (pin "P$2") (pinfunction "2_P$2") (pintype "passive"))
      (node (ref "R150") (pin "P$2") (pinfunction "2_P$2") (pintype "passive"))
      (node (ref "R171") (pin "P$2") (pinfunction "2_P$2") (pintype "passive"))
      (node (ref "R241") (pin "P$2") (pinfunction "2_P$2") (pintype "passive"))
    )
    (net (code "55") (name "IN36") (class "Default")
      (node (ref "LED36") (pin "DIN") (pinfunction "DIN_DIN") (pintype "input"))
      (node (ref "R128") (pin "P$2") (pinfunction "2_P$2") (pintype "passive"))
      (node (ref "R149") (pin "P$2") (pinfunction "2_P$2") (pintype "passive"))
      (node (ref "R175") (pin "P$2") (pinfunction "2_P$2") (pintype "passive"))
      (node (ref "R240") (pin "P$2") (pinfunction "2_P$2") (pintype "passive"))
    )
    (net (code "56") (name "IN37") (class "Default")
      (node (ref "LED37") (pin "DIN") (pinfunction "DIN_DIN") (pintype "input"))
      (node (ref "R239") (pin "P$2") (pinfunction "2_P$2") (pintype "passive"))
      (node (ref "R56") (pin "P$2") (pinfunction "2_P$2") (pintype "passive"))
      (node (ref "R63") (pin "P$2") (pinfunction "2_P$2") (pintype "passive"))
      (node (ref "R96") (pin "P$2") (pinfunction "2_P$2") (pintype "passive"))
    )
    (net (code "57") (name "IN38") (class "Default")
      (node (ref "LED38") (pin "DIN") (pinfunction "DIN_DIN") (pintype "input"))
      (node (ref "R102") (pin "P$2") (pinfunction "2_P$2") (pintype "passive"))
      (node (ref "R153") (pin "P$2") (pinfunction "2_P$2") (pintype "passive"))
      (node (ref "R238") (pin "P$2") (pinfunction "2_P$2") (pintype "passive"))
      (node (ref "R61") (pin "P$2") (pinfunction "2_P$2") (pintype "passive"))
      (node (ref "R93") (pin "P$2") (pinfunction "2_P$2") (pintype "passive"))
    )
    (net (code "58") (name "IN39") (class "Default")
      (node (ref "LED39") (pin "DIN") (pinfunction "DIN_DIN") (pintype "input"))
      (node (ref "R131") (pin "P$2") (pinfunction "2_P$2") (pintype "passive"))
      (node (ref "R157") (pin "P$2") (pinfunction "2_P$2") (pintype "passive"))
      (node (ref "R178") (pin "P$2") (pinfunction "2_P$2") (pintype "passive"))
      (node (ref "R237") (pin "P$2") (pinfunction "2_P$2") (pintype "passive"))
      (node (ref "R99") (pin "P$2") (pinfunction "2_P$2") (pintype "passive"))
    )
    (net (code "59") (name "IN40") (class "Default")
      (node (ref "LED40") (pin "DIN") (pinfunction "DIN_DIN") (pintype "input"))
      (node (ref "R135") (pin "P$2") (pinfunction "2_P$2") (pintype "passive"))
      (node (ref "R156") (pin "P$2") (pinfunction "2_P$2") (pintype "passive"))
      (node (ref "R161") (pin "P$2") (pinfunction "2_P$2") (pintype "passive"))
      (node (ref "R182") (pin "P$2") (pinfunction "2_P$2") (pintype "passive"))
      (node (ref "R236") (pin "P$2") (pinfunction "2_P$2") (pintype "passive"))
    )
    (net (code "60") (name "IN41") (class "Default")
      (node (ref "LED41") (pin "DIN") (pinfunction "DIN_DIN") (pintype "input"))
      (node (ref "R139") (pin "P$2") (pinfunction "2_P$2") (pintype "passive"))
      (node (ref "R160") (pin "P$2") (pinfunction "2_P$2") (pintype "passive"))
      (node (ref "R165") (pin "P$2") (pinfunction "2_P$2") (pintype "passive"))
      (node (ref "R186") (pin "P$2") (pinfunction "2_P$2") (pintype "passive"))
      (node (ref "R235") (pin "P$2") (pinfunction "2_P$2") (pintype "passive"))
    )
    (net (code "61") (name "IN42") (class "Default")
      (node (ref "LED42") (pin "DIN") (pinfunction "DIN_DIN") (pintype "input"))
      (node (ref "R143") (pin "P$2") (pinfunction "2_P$2") (pintype "passive"))
      (node (ref "R164") (pin "P$2") (pinfunction "2_P$2") (pintype "passive"))
      (node (ref "R169") (pin "P$2") (pinfunction "2_P$2") (pintype "passive"))
      (node (ref "R190") (pin "P$2") (pinfunction "2_P$2") (pintype "passive"))
      (node (ref "R234") (pin "P$2") (pinfunction "2_P$2") (pintype "passive"))
    )
    (net (code "62") (name "IN43") (class "Default")
      (node (ref "LED43") (pin "DIN") (pinfunction "DIN_DIN") (pintype "input"))
      (node (ref "R147") (pin "P$2") (pinfunction "2_P$2") (pintype "passive"))
      (node (ref "R168") (pin "P$2") (pinfunction "2_P$2") (pintype "passive"))
      (node (ref "R173") (pin "P$2") (pinfunction "2_P$2") (pintype "passive"))
      (node (ref "R194") (pin "P$2") (pinfunction "2_P$2") (pintype "passive"))
      (node (ref "R233") (pin "P$2") (pinfunction "2_P$2") (pintype "passive"))
    )
    (net (code "63") (name "IN44") (class "Default")
      (node (ref "LED44") (pin "DIN") (pinfunction "DIN_DIN") (pintype "input"))
      (node (ref "R151") (pin "P$2") (pinfunction "2_P$2") (pintype "passive"))
      (node (ref "R172") (pin "P$2") (pinfunction "2_P$2") (pintype "passive"))
      (node (ref "R198") (pin "P$2") (pinfunction "2_P$2") (pintype "passive"))
      (node (ref "R232") (pin "P$2") (pinfunction "2_P$2") (pintype "passive"))
    )
    (net (code "64") (name "IN45") (class "Default")
      (node (ref "LED45") (pin "DIN") (pinfunction "DIN_DIN") (pintype "input"))
      (node (ref "R100") (pin "P$2") (pinfunction "2_P$2") (pintype "passive"))
      (node (ref "R231") (pin "P$2") (pinfunction "2_P$2") (pintype "passive"))
      (node (ref "R59") (pin "P$2") (pinfunction "2_P$2") (pintype "passive"))
      (node (ref "R66") (pin "P$2") (pinfunction "2_P$2") (pintype "passive"))
    )
    (net (code "65") (name "IN46") (class "Default")
      (node (ref "LED46") (pin "DIN") (pinfunction "DIN_DIN") (pintype "input"))
      (node (ref "R105") (pin "P$2") (pinfunction "2_P$2") (pintype "passive"))
      (node (ref "R176") (pin "P$2") (pinfunction "2_P$2") (pintype "passive"))
      (node (ref "R230") (pin "P$2") (pinfunction "2_P$2") (pintype "passive"))
      (node (ref "R64") (pin "P$2") (pinfunction "2_P$2") (pintype "passive"))
      (node (ref "R97") (pin "P$2") (pinfunction "2_P$2") (pintype "passive"))
    )
    (net (code "66") (name "IN47") (class "Default")
      (node (ref "LED47") (pin "DIN") (pinfunction "DIN_DIN") (pintype "input"))
      (node (ref "R103") (pin "P$2") (pinfunction "2_P$2") (pintype "passive"))
      (node (ref "R154") (pin "P$2") (pinfunction "2_P$2") (pintype "passive"))
      (node (ref "R180") (pin "P$2") (pinfunction "2_P$2") (pintype "passive"))
      (node (ref "R200") (pin "P$2") (pinfunction "2_P$2") (pintype "passive"))
      (node (ref "R229") (pin "P$2") (pinfunction "2_P$2") (pintype "passive"))
    )
    (net (code "67") (name "IN48") (class "Default")
      (node (ref "LED48") (pin "DIN") (pinfunction "DIN_DIN") (pintype "input"))
      (node (ref "R158") (pin "P$2") (pinfunction "2_P$2") (pintype "passive"))
      (node (ref "R179") (pin "P$2") (pinfunction "2_P$2") (pintype "passive"))
      (node (ref "R184") (pin "P$2") (pinfunction "2_P$2") (pintype "passive"))
      (node (ref "R203") (pin "P$2") (pinfunction "2_P$2") (pintype "passive"))
      (node (ref "R228") (pin "P$2") (pinfunction "2_P$2") (pintype "passive"))
    )
    (net (code "68") (name "IN49") (class "Default")
      (node (ref "LED49") (pin "DIN") (pinfunction "DIN_DIN") (pintype "input"))
      (node (ref "R162") (pin "P$2") (pinfunction "2_P$2") (pintype "passive"))
      (node (ref "R183") (pin "P$2") (pinfunction "2_P$2") (pintype "passive"))
      (node (ref "R188") (pin "P$2") (pinfunction "2_P$2") (pintype "passive"))
      (node (ref "R206") (pin "P$2") (pinfunction "2_P$2") (pintype "passive"))
      (node (ref "R227") (pin "P$2") (pinfunction "2_P$2") (pintype "passive"))
    )
    (net (code "69") (name "IN50") (class "Default")
      (node (ref "LED50") (pin "DIN") (pinfunction "DIN_DIN") (pintype "input"))
      (node (ref "R166") (pin "P$2") (pinfunction "2_P$2") (pintype "passive"))
      (node (ref "R187") (pin "P$2") (pinfunction "2_P$2") (pintype "passive"))
      (node (ref "R192") (pin "P$2") (pinfunction "2_P$2") (pintype "passive"))
      (node (ref "R209") (pin "P$2") (pinfunction "2_P$2") (pintype "passive"))
      (node (ref "R226") (pin "P$2") (pinfunction "2_P$2") (pintype "passive"))
    )
    (net (code "70") (name "IN51") (class "Default")
      (node (ref "LED51") (pin "DIN") (pinfunction "DIN_DIN") (pintype "input"))
      (node (ref "R170") (pin "P$2") (pinfunction "2_P$2") (pintype "passive"))
      (node (ref "R191") (pin "P$2") (pinfunction "2_P$2") (pintype "passive"))
      (node (ref "R196") (pin "P$2") (pinfunction "2_P$2") (pintype "passive"))
      (node (ref "R212") (pin "P$2") (pinfunction "2_P$2") (pintype "passive"))
      (node (ref "R225") (pin "P$2") (pinfunction "2_P$2") (pintype "passive"))
    )
    (net (code "71") (name "IN52") (class "Default")
      (node (ref "LED52") (pin "DIN") (pinfunction "DIN_DIN") (pintype "input"))
      (node (ref "R174") (pin "P$2") (pinfunction "2_P$2") (pintype "passive"))
      (node (ref "R195") (pin "P$2") (pinfunction "2_P$2") (pintype "passive"))
      (node (ref "R215") (pin "P$2") (pinfunction "2_P$2") (pintype "passive"))
      (node (ref "R224") (pin "P$2") (pinfunction "2_P$2") (pintype "passive"))
    )
    (net (code "72") (name "IN53") (class "Default")
      (node (ref "LED53") (pin "DIN") (pinfunction "DIN_DIN") (pintype "input"))
      (node (ref "R104") (pin "P$2") (pinfunction "2_P$2") (pintype "passive"))
      (node (ref "R223") (pin "P$2") (pinfunction "2_P$2") (pintype "passive"))
      (node (ref "R62") (pin "P$2") (pinfunction "2_P$2") (pintype "passive"))
    )
    (net (code "73") (name "IN54") (class "Default")
      (node (ref "LED54") (pin "DIN") (pinfunction "DIN_DIN") (pintype "input"))
      (node (ref "R101") (pin "P$2") (pinfunction "2_P$2") (pintype "passive"))
      (node (ref "R199") (pin "P$2") (pinfunction "2_P$2") (pintype "passive"))
      (node (ref "R222") (pin "P$2") (pinfunction "2_P$2") (pintype "passive"))
      (node (ref "R67") (pin "P$2") (pinfunction "2_P$2") (pintype "passive"))
    )
    (net (code "74") (name "IN55") (class "Default")
      (node (ref "LED55") (pin "DIN") (pinfunction "DIN_DIN") (pintype "input"))
      (node (ref "R106") (pin "P$2") (pinfunction "2_P$2") (pintype "passive"))
      (node (ref "R177") (pin "P$2") (pinfunction "2_P$2") (pintype "passive"))
      (node (ref "R202") (pin "P$2") (pinfunction "2_P$2") (pintype "passive"))
      (node (ref "R221") (pin "P$2") (pinfunction "2_P$2") (pintype "passive"))
    )
    (net (code "75") (name "IN56") (class "Default")
      (node (ref "LED56") (pin "DIN") (pinfunction "DIN_DIN") (pintype "input"))
      (node (ref "R181") (pin "P$2") (pinfunction "2_P$2") (pintype "passive"))
      (node (ref "R201") (pin "P$2") (pinfunction "2_P$2") (pintype "passive"))
      (node (ref "R205") (pin "P$2") (pinfunction "2_P$2") (pintype "passive"))
      (node (ref "R220") (pin "P$2") (pinfunction "2_P$2") (pintype "passive"))
    )
    (net (code "76") (name "IN57") (class "Default")
      (node (ref "LED57") (pin "DIN") (pinfunction "DIN_DIN") (pintype "input"))
      (node (ref "R185") (pin "P$2") (pinfunction "2_P$2") (pintype "passive"))
      (node (ref "R204") (pin "P$2") (pinfunction "2_P$2") (pintype "passive"))
      (node (ref "R208") (pin "P$2") (pinfunction "2_P$2") (pintype "passive"))
      (node (ref "R219") (pin "P$2") (pinfunction "2_P$2") (pintype "passive"))
    )
    (net (code "77") (name "IN58") (class "Default")
      (node (ref "LED58") (pin "DIN") (pinfunction "DIN_DIN") (pintype "input"))
      (node (ref "R189") (pin "P$2") (pinfunction "2_P$2") (pintype "passive"))
      (node (ref "R207") (pin "P$2") (pinfunction "2_P$2") (pintype "passive"))
      (node (ref "R211") (pin "P$2") (pinfunction "2_P$2") (pintype "passive"))
      (node (ref "R218") (pin "P$2") (pinfunction "2_P$2") (pintype "passive"))
    )
    (net (code "78") (name "IN59") (class "Default")
      (node (ref "LED59") (pin "DIN") (pinfunction "DIN_DIN") (pintype "input"))
      (node (ref "R193") (pin "P$2") (pinfunction "2_P$2") (pintype "passive"))
      (node (ref "R210") (pin "P$2") (pinfunction "2_P$2") (pintype "passive"))
      (node (ref "R214") (pin "P$2") (pinfunction "2_P$2") (pintype "passive"))
      (node (ref "R217") (pin "P$2") (pinfunction "2_P$2") (pintype "passive"))
    )
    (net (code "79") (name "IN60") (class "Default")
      (node (ref "LED60") (pin "DIN") (pinfunction "DIN_DIN") (pintype "input"))
      (node (ref "R197") (pin "P$2") (pinfunction "2_P$2") (pintype "passive"))
      (node (ref "R213") (pin "P$2") (pinfunction "2_P$2") (pintype "passive"))
      (node (ref "R216") (pin "P$2") (pinfunction "2_P$2") (pintype "passive"))
    )
    (net (code "80") (name "LE") (class "Default")
      (node (ref "IC1") (pin "4") (pinfunction "LE_4") (pintype "input"))
      (node (ref "IC2") (pin "20") (pinfunction "(MISO/DO/OC1A/PCINT9)PB1_20") (pintype "bidirectional"))
      (node (ref "TP4") (pin "P$1") (pinfunction "P$1_P$1") (pintype "bidirectional"))
    )
    (net (code "81") (name "LED-DATA") (class "Default")
      (node (ref "R283") (pin "P$1") (pinfunction "1_P$1") (pintype "passive"))
      (node (ref "R284") (pin "P$1") (pinfunction "1_P$1") (pintype "passive"))
      (node (ref "X2") (pin "3") (pinfunction "3_3") (pintype "passive"))
    )
    (net (code "82") (name "LED-DATA-OUT") (class "Default")
      (node (ref "R356") (pin "P$1") (pinfunction "1_P$1") (pintype "passive"))
      (node (ref "R357") (pin "P$1") (pinfunction "1_P$1") (pintype "passive"))
      (node (ref "X2") (pin "4") (pinfunction "4_4") (pintype "passive"))
    )
    (net (code "83") (name "LED-DATA-OUT-UC") (class "Default")
      (node (ref "R287") (pin "P$1") (pinfunction "1_P$1") (pintype "passive"))
      (node (ref "R328") (pin "P$1") (pinfunction "1_P$1") (pintype "passive"))
      (node (ref "R329") (pin "P$1") (pinfunction "1_P$1") (pintype "passive"))
      (node (ref "R330") (pin "P$1") (pinfunction "1_P$1") (pintype "passive"))
      (node (ref "R331") (pin "P$1") (pinfunction "1_P$1") (pintype "passive"))
      (node (ref "R332") (pin "P$1") (pinfunction "1_P$1") (pintype "passive"))
      (node (ref "R333") (pin "P$1") (pinfunction "1_P$1") (pintype "passive"))
      (node (ref "R334") (pin "P$1") (pinfunction "1_P$1") (pintype "passive"))
      (node (ref "R335") (pin "P$1") (pinfunction "1_P$1") (pintype "passive"))
      (node (ref "R353") (pin "P$2") (pinfunction "2_P$2") (pintype "passive"))
    )
    (net (code "84") (name "LED-DATA-UC") (class "Default")
      (node (ref "R248") (pin "P$1") (pinfunction "1_P$1") (pintype "passive"))
      (node (ref "R249") (pin "P$1") (pinfunction "1_P$1") (pintype "passive"))
      (node (ref "R250") (pin "P$1") (pinfunction "1_P$1") (pintype "passive"))
      (node (ref "R251") (pin "P$1") (pinfunction "1_P$1") (pintype "passive"))
      (node (ref "R252") (pin "P$1") (pinfunction "1_P$1") (pintype "passive"))
      (node (ref "R253") (pin "P$1") (pinfunction "1_P$1") (pintype "passive"))
      (node (ref "R254") (pin "P$1") (pinfunction "1_P$1") (pintype "passive"))
      (node (ref "R255") (pin "P$1") (pinfunction "1_P$1") (pintype "passive"))
      (node (ref "R281") (pin "P$2") (pinfunction "2_P$2") (pintype "passive"))
      (node (ref "R286") (pin "P$1") (pinfunction "1_P$1") (pintype "passive"))
    )
    (net (code "85") (name "MOSI") (class "Default")
      (node (ref "IC2") (pin "19") (pinfunction "(MOSI/DI/SDA/~{OC1A}/PCINT8)PB0_19") (pintype "bidirectional"))
      (node (ref "TP3") (pin "P$1") (pinfunction "P$1_P$1") (pintype "bidirectional"))
    )
    (net (code "86") (name "Net-(IC1-IREF)") (class "Default")
      (node (ref "IC1") (pin "23") (pinfunction "IREF_23") (pintype "output"))
      (node (ref "R5") (pin "P$2") (pinfunction "2_P$2") (pintype "passive"))
    )
    (net (code "87") (name "Net-(IC2-(AREF{slash}PCINT3)PA3)") (class "Default")
      (node (ref "IC2") (pin "15") (pinfunction "(AREF/PCINT3)PA3_15") (pintype "bidirectional"))
      (node (ref "R287") (pin "P$2") (pinfunction "2_P$2") (pintype "passive"))
    )
    (net (code "88") (name "Net-(IC2-(DO{slash}ADC1{slash}PCINT1)PA1)") (class "Default")
      (node (ref "IC2") (pin "17") (pinfunction "(DO/ADC1/PCINT1)PA1_17") (pintype "bidirectional"))
      (node (ref "Q1") (pin "2") (pinfunction "B_2") (pintype "passive"))
    )
    (net (code "89") (name "Net-(IC2-(SCL{slash}USCK{slash}INT1{slash}ADC2{slash}PCINT2)PA2)") (class "Default")
      (node (ref "IC2") (pin "16") (pinfunction "(SCL/USCK/INT1/ADC2/PCINT2)PA2_16") (pintype "bidirectional"))
      (node (ref "R286") (pin "P$2") (pinfunction "2_P$2") (pintype "passive"))
    )
    (net (code "90") (name "Net-(LED61-CA2)") (class "Default")
      (node (ref "LED61") (pin "6") (pinfunction "CA2_6") (pintype "passive"))
      (node (ref "R8") (pin "P$1") (pinfunction "1_P$1") (pintype "passive"))
    )
    (net (code "91") (name "Net-(LED62-CA2)") (class "Default")
      (node (ref "LED62") (pin "6") (pinfunction "CA2_6") (pintype "passive"))
      (node (ref "R7") (pin "P$1") (pinfunction "1_P$1") (pintype "passive"))
    )
    (net (code "92") (name "Net-(Q1A-C)") (class "Default")
      (node (ref "Q1") (pin "5") (pinfunction "B_5") (pintype "passive"))
      (node (ref "Q1") (pin "6") (pinfunction "C_6") (pintype "passive"))
      (node (ref "R285") (pin "P$2") (pinfunction "2_P$2") (pintype "passive"))
    )
    (net (code "93") (name "Net-(R2-1)") (class "Default")
      (node (ref "R2") (pin "P$1") (pinfunction "1_P$1") (pintype "passive"))
      (node (ref "R270") (pin "P$1") (pinfunction "1_P$1") (pintype "passive"))
      (node (ref "R271") (pin "P$1") (pinfunction "1_P$1") (pintype "passive"))
      (node (ref "R282") (pin "P$1") (pinfunction "1_P$1") (pintype "passive"))
      (node (ref "R283") (pin "P$2") (pinfunction "2_P$2") (pintype "passive"))
    )
    (net (code "94") (name "Net-(R2-2)") (class "Default")
      (node (ref "R2") (pin "P$2") (pinfunction "2_P$2") (pintype "passive"))
      (node (ref "R216") (pin "P$1") (pinfunction "1_P$1") (pintype "passive"))
      (node (ref "R217") (pin "P$1") (pinfunction "1_P$1") (pintype "passive"))
      (node (ref "R218") (pin "P$1") (pinfunction "1_P$1") (pintype "passive"))
      (node (ref "R219") (pin "P$1") (pinfunction "1_P$1") (pintype "passive"))
      (node (ref "R220") (pin "P$1") (pinfunction "1_P$1") (pintype "passive"))
      (node (ref "R221") (pin "P$1") (pinfunction "1_P$1") (pintype "passive"))
      (node (ref "R222") (pin "P$1") (pinfunction "1_P$1") (pintype "passive"))
      (node (ref "R223") (pin "P$1") (pinfunction "1_P$1") (pintype "passive"))
    )
    (net (code "95") (name "Net-(R224-1)") (class "Default")
      (node (ref "R224") (pin "P$1") (pinfunction "1_P$1") (pintype "passive"))
      (node (ref "R225") (pin "P$1") (pinfunction "1_P$1") (pintype "passive"))
      (node (ref "R226") (pin "P$1") (pinfunction "1_P$1") (pintype "passive"))
      (node (ref "R227") (pin "P$1") (pinfunction "1_P$1") (pintype "passive"))
      (node (ref "R228") (pin "P$1") (pinfunction "1_P$1") (pintype "passive"))
      (node (ref "R229") (pin "P$1") (pinfunction "1_P$1") (pintype "passive"))
      (node (ref "R230") (pin "P$1") (pinfunction "1_P$1") (pintype "passive"))
      (node (ref "R231") (pin "P$1") (pinfunction "1_P$1") (pintype "passive"))
      (node (ref "R270") (pin "P$2") (pinfunction "2_P$2") (pintype "passive"))
    )
    (net (code "96") (name "Net-(R232-1)") (class "Default")
      (node (ref "R232") (pin "P$1") (pinfunction "1_P$1") (pintype "passive"))
      (node (ref "R233") (pin "P$1") (pinfunction "1_P$1") (pintype "passive"))
      (node (ref "R234") (pin "P$1") (pinfunction "1_P$1") (pintype "passive"))
      (node (ref "R235") (pin "P$1") (pinfunction "1_P$1") (pintype "passive"))
      (node (ref "R236") (pin "P$1") (pinfunction "1_P$1") (pintype "passive"))
      (node (ref "R237") (pin "P$1") (pinfunction "1_P$1") (pintype "passive"))
      (node (ref "R238") (pin "P$1") (pinfunction "1_P$1") (pintype "passive"))
      (node (ref "R239") (pin "P$1") (pinfunction "1_P$1") (pintype "passive"))
      (node (ref "R271") (pin "P$2") (pinfunction "2_P$2") (pintype "passive"))
    )
    (net (code "97") (name "Net-(R240-1)") (class "Default")
      (node (ref "R240") (pin "P$1") (pinfunction "1_P$1") (pintype "passive"))
      (node (ref "R241") (pin "P$1") (pinfunction "1_P$1") (pintype "passive"))
      (node (ref "R242") (pin "P$1") (pinfunction "1_P$1") (pintype "passive"))
      (node (ref "R243") (pin "P$1") (pinfunction "1_P$1") (pintype "passive"))
      (node (ref "R244") (pin "P$1") (pinfunction "1_P$1") (pintype "passive"))
      (node (ref "R245") (pin "P$1") (pinfunction "1_P$1") (pintype "passive"))
      (node (ref "R246") (pin "P$1") (pinfunction "1_P$1") (pintype "passive"))
      (node (ref "R247") (pin "P$1") (pinfunction "1_P$1") (pintype "passive"))
      (node (ref "R282") (pin "P$2") (pinfunction "2_P$2") (pintype "passive"))
    )
    (net (code "98") (name "Net-(R256-1)") (class "Default")
      (node (ref "R256") (pin "P$1") (pinfunction "1_P$1") (pintype "passive"))
      (node (ref "R257") (pin "P$1") (pinfunction "1_P$1") (pintype "passive"))
      (node (ref "R258") (pin "P$1") (pinfunction "1_P$1") (pintype "passive"))
      (node (ref "R259") (pin "P$1") (pinfunction "1_P$1") (pintype "passive"))
      (node (ref "R260") (pin "P$1") (pinfunction "1_P$1") (pintype "passive"))
      (node (ref "R261") (pin "P$1") (pinfunction "1_P$1") (pintype "passive"))
      (node (ref "R262") (pin "P$1") (pinfunction "1_P$1") (pintype "passive"))
      (node (ref "R263") (pin "P$1") (pinfunction "1_P$1") (pintype "passive"))
      (node (ref "R280") (pin "P$2") (pinfunction "2_P$2") (pintype "passive"))
    )
    (net (code "99") (name "Net-(R264-1)") (class "Default")
      (node (ref "R264") (pin "P$1") (pinfunction "1_P$1") (pintype "passive"))
      (node (ref "R265") (pin "P$1") (pinfunction "1_P$1") (pintype "passive"))
      (node (ref "R266") (pin "P$1") (pinfunction "1_P$1") (pintype "passive"))
      (node (ref "R267") (pin "P$1") (pinfunction "1_P$1") (pintype "passive"))
      (node (ref "R268") (pin "P$1") (pinfunction "1_P$1") (pintype "passive"))
      (node (ref "R269") (pin "P$1") (pinfunction "1_P$1") (pintype "passive"))
      (node (ref "R279") (pin "P$2") (pinfunction "2_P$2") (pintype "passive"))
    )
    (net (code "100") (name "Net-(R272-1)") (class "Default")
      (node (ref "R272") (pin "P$1") (pinfunction "1_P$1") (pintype "passive"))
      (node (ref "R273") (pin "P$1") (pinfunction "1_P$1") (pintype "passive"))
      (node (ref "R274") (pin "P$1") (pinfunction "1_P$1") (pintype "passive"))
      (node (ref "R275") (pin "P$1") (pinfunction "1_P$1") (pintype "passive"))
      (node (ref "R276") (pin "P$1") (pinfunction "1_P$1") (pintype "passive"))
      (node (ref "R277") (pin "P$1") (pinfunction "1_P$1") (pintype "passive"))
      (node (ref "R278") (pin "P$2") (pinfunction "2_P$2") (pintype "passive"))
    )
    (net (code "101") (name "Net-(R278-1)") (class "Default")
      (node (ref "R278") (pin "P$1") (pinfunction "1_P$1") (pintype "passive"))
      (node (ref "R279") (pin "P$1") (pinfunction "1_P$1") (pintype "passive"))
      (node (ref "R280") (pin "P$1") (pinfunction "1_P$1") (pintype "passive"))
      (node (ref "R281") (pin "P$1") (pinfunction "1_P$1") (pintype "passive"))
      (node (ref "R284") (pin "P$2") (pinfunction "2_P$2") (pintype "passive"))
    )
    (net (code "102") (name "Net-(R288-1)") (class "Default")
      (node (ref "R288") (pin "P$1") (pinfunction "1_P$1") (pintype "passive"))
      (node (ref "R289") (pin "P$1") (pinfunction "1_P$1") (pintype "passive"))
      (node (ref "R290") (pin "P$1") (pinfunction "1_P$1") (pintype "passive"))
      (node (ref "R291") (pin "P$1") (pinfunction "1_P$1") (pintype "passive"))
      (node (ref "R292") (pin "P$1") (pinfunction "1_P$1") (pintype "passive"))
      (node (ref "R293") (pin "P$1") (pinfunction "1_P$1") (pintype "passive"))
      (node (ref "R294") (pin "P$1") (pinfunction "1_P$1") (pintype "passive"))
      (node (ref "R295") (pin "P$1") (pinfunction "1_P$1") (pintype "passive"))
      (node (ref "R348") (pin "P$2") (pinfunction "2_P$2") (pintype "passive"))
    )
    (net (code "103") (name "Net-(R296-1)") (class "Default")
      (node (ref "R296") (pin "P$1") (pinfunction "1_P$1") (pintype "passive"))
      (node (ref "R297") (pin "P$1") (pinfunction "1_P$1") (pintype "passive"))
      (node (ref "R298") (pin "P$1") (pinfunction "1_P$1") (pintype "passive"))
      (node (ref "R299") (pin "P$1") (pinfunction "1_P$1") (pintype "passive"))
      (node (ref "R300") (pin "P$1") (pinfunction "1_P$1") (pintype "passive"))
      (node (ref "R301") (pin "P$1") (pinfunction "1_P$1") (pintype "passive"))
      (node (ref "R302") (pin "P$1") (pinfunction "1_P$1") (pintype "passive"))
      (node (ref "R303") (pin "P$1") (pinfunction "1_P$1") (pintype "passive"))
      (node (ref "R349") (pin "P$2") (pinfunction "2_P$2") (pintype "passive"))
    )
    (net (code "104") (name "Net-(R304-1)") (class "Default")
      (node (ref "R304") (pin "P$1") (pinfunction "1_P$1") (pintype "passive"))
      (node (ref "R305") (pin "P$1") (pinfunction "1_P$1") (pintype "passive"))
      (node (ref "R306") (pin "P$1") (pinfunction "1_P$1") (pintype "passive"))
      (node (ref "R307") (pin "P$1") (pinfunction "1_P$1") (pintype "passive"))
      (node (ref "R308") (pin "P$1") (pinfunction "1_P$1") (pintype "passive"))
      (node (ref "R309") (pin "P$1") (pinfunction "1_P$1") (pintype "passive"))
      (node (ref "R310") (pin "P$1") (pinfunction "1_P$1") (pintype "passive"))
      (node (ref "R311") (pin "P$1") (pinfunction "1_P$1") (pintype "passive"))
      (node (ref "R350") (pin "P$2") (pinfunction "2_P$2") (pintype "passive"))
    )
    (net (code "105") (name "Net-(R312-1)") (class "Default")
      (node (ref "R312") (pin "P$1") (pinfunction "1_P$1") (pintype "passive"))
      (node (ref "R313") (pin "P$1") (pinfunction "1_P$1") (pintype "passive"))
      (node (ref "R314") (pin "P$1") (pinfunction "1_P$1") (pintype "passive"))
      (node (ref "R315") (pin "P$1") (pinfunction "1_P$1") (pintype "passive"))
      (node (ref "R316") (pin "P$1") (pinfunction "1_P$1") (pintype "passive"))
      (node (ref "R317") (pin "P$1") (pinfunction "1_P$1") (pintype "passive"))
      (node (ref "R318") (pin "P$1") (pinfunction "1_P$1") (pintype "passive"))
      (node (ref "R319") (pin "P$1") (pinfunction "1_P$1") (pintype "passive"))
      (node (ref "R355") (pin "P$2") (pinfunction "2_P$2") (pintype "passive"))
    )
    (net (code "106") (name "Net-(R320-1)") (class "Default")
      (node (ref "R320") (pin "P$1") (pinfunction "1_P$1") (pintype "passive"))
      (node (ref "R321") (pin "P$1") (pinfunction "1_P$1") (pintype "passive"))
      (node (ref "R322") (pin "P$1") (pinfunction "1_P$1") (pintype "passive"))
      (node (ref "R323") (pin "P$1") (pinfunction "1_P$1") (pintype "passive"))
      (node (ref "R324") (pin "P$1") (pinfunction "1_P$1") (pintype "passive"))
      (node (ref "R325") (pin "P$1") (pinfunction "1_P$1") (pintype "passive"))
      (node (ref "R326") (pin "P$1") (pinfunction "1_P$1") (pintype "passive"))
      (node (ref "R327") (pin "P$1") (pinfunction "1_P$1") (pintype "passive"))
      (node (ref "R354") (pin "P$2") (pinfunction "2_P$2") (pintype "passive"))
    )
    (net (code "107") (name "Net-(R336-1)") (class "Default")
      (node (ref "R336") (pin "P$1") (pinfunction "1_P$1") (pintype "passive"))
      (node (ref "R337") (pin "P$1") (pinfunction "1_P$1") (pintype "passive"))
      (node (ref "R338") (pin "P$1") (pinfunction "1_P$1") (pintype "passive"))
      (node (ref "R339") (pin "P$1") (pinfunction "1_P$1") (pintype "passive"))
      (node (ref "R340") (pin "P$1") (pinfunction "1_P$1") (pintype "passive"))
      (node (ref "R341") (pin "P$1") (pinfunction "1_P$1") (pintype "passive"))
      (node (ref "R352") (pin "P$2") (pinfunction "2_P$2") (pintype "passive"))
    )
    (net (code "108") (name "Net-(R342-1)") (class "Default")
      (node (ref "R342") (pin "P$1") (pinfunction "1_P$1") (pintype "passive"))
      (node (ref "R343") (pin "P$1") (pinfunction "1_P$1") (pintype "passive"))
      (node (ref "R344") (pin "P$1") (pinfunction "1_P$1") (pintype "passive"))
      (node (ref "R345") (pin "P$1") (pinfunction "1_P$1") (pintype "passive"))
      (node (ref "R346") (pin "P$1") (pinfunction "1_P$1") (pintype "passive"))
      (node (ref "R347") (pin "P$1") (pinfunction "1_P$1") (pintype "passive"))
      (node (ref "R351") (pin "P$2") (pinfunction "2_P$2") (pintype "passive"))
    )
    (net (code "109") (name "Net-(R348-1)") (class "Default")
      (node (ref "R348") (pin "P$1") (pinfunction "1_P$1") (pintype "passive"))
      (node (ref "R349") (pin "P$1") (pinfunction "1_P$1") (pintype "passive"))
      (node (ref "R350") (pin "P$1") (pinfunction "1_P$1") (pintype "passive"))
      (node (ref "R355") (pin "P$1") (pinfunction "1_P$1") (pintype "passive"))
      (node (ref "R356") (pin "P$2") (pinfunction "2_P$2") (pintype "passive"))
    )
    (net (code "110") (name "Net-(R351-1)") (class "Default")
      (node (ref "R351") (pin "P$1") (pinfunction "1_P$1") (pintype "passive"))
      (node (ref "R352") (pin "P$1") (pinfunction "1_P$1") (pintype "passive"))
      (node (ref "R353") (pin "P$1") (pinfunction "1_P$1") (pintype "passive"))
      (node (ref "R354") (pin "P$1") (pinfunction "1_P$1") (pintype "passive"))
      (node (ref "R357") (pin "P$2") (pinfunction "2_P$2") (pintype "passive"))
    )
    (net (code "111") (name "OUT1") (class "Default")
      (node (ref "LED1") (pin "DOUT") (pinfunction "DOUT_DOUT") (pintype "output"))
      (node (ref "R18") (pin "P$1") (pinfunction "1_P$1") (pintype "passive"))
      (node (ref "R28") (pin "P$1") (pinfunction "1_P$1") (pintype "passive"))
      (node (ref "R347") (pin "P$2") (pinfunction "2_P$2") (pintype "passive"))
    )
    (net (code "112") (name "OUT2") (class "Default")
      (node (ref "LED2") (pin "DOUT") (pinfunction "DOUT_DOUT") (pintype "output"))
      (node (ref "R13") (pin "P$1") (pinfunction "1_P$1") (pintype "passive"))
      (node (ref "R17") (pin "P$1") (pinfunction "1_P$1") (pintype "passive"))
      (node (ref "R19") (pin "P$1") (pinfunction "1_P$1") (pintype "passive"))
      (node (ref "R346") (pin "P$2") (pinfunction "2_P$2") (pintype "passive"))
    )
    (net (code "113") (name "OUT3") (class "Default")
      (node (ref "LED3") (pin "DOUT") (pinfunction "DOUT_DOUT") (pintype "output"))
      (node (ref "R345") (pin "P$2") (pinfunction "2_P$2") (pintype "passive"))
      (node (ref "R35") (pin "P$1") (pinfunction "1_P$1") (pintype "passive"))
      (node (ref "R36") (pin "P$1") (pinfunction "1_P$1") (pintype "passive"))
      (node (ref "R37") (pin "P$1") (pinfunction "1_P$1") (pintype "passive"))
    )
    (net (code "114") (name "OUT4") (class "Default")
      (node (ref "LED4") (pin "DOUT") (pinfunction "DOUT_DOUT") (pintype "output"))
      (node (ref "R344") (pin "P$2") (pinfunction "2_P$2") (pintype "passive"))
      (node (ref "R38") (pin "P$1") (pinfunction "1_P$1") (pintype "passive"))
      (node (ref "R39") (pin "P$1") (pinfunction "1_P$1") (pintype "passive"))
      (node (ref "R40") (pin "P$1") (pinfunction "1_P$1") (pintype "passive"))
    )
    (net (code "115") (name "OUT5") (class "Default")
      (node (ref "LED5") (pin "DOUT") (pinfunction "DOUT_DOUT") (pintype "output"))
      (node (ref "R343") (pin "P$2") (pinfunction "2_P$2") (pintype "passive"))
      (node (ref "R41") (pin "P$1") (pinfunction "1_P$1") (pintype "passive"))
      (node (ref "R42") (pin "P$1") (pinfunction "1_P$1") (pintype "passive"))
      (node (ref "R43") (pin "P$1") (pinfunction "1_P$1") (pintype "passive"))
    )
    (net (code "116") (name "OUT6") (class "Default")
      (node (ref "LED6") (pin "DOUT") (pinfunction "DOUT_DOUT") (pintype "output"))
      (node (ref "R342") (pin "P$2") (pinfunction "2_P$2") (pintype "passive"))
      (node (ref "R44") (pin "P$1") (pinfunction "1_P$1") (pintype "passive"))
      (node (ref "R45") (pin "P$1") (pinfunction "1_P$1") (pintype "passive"))
    )
    (net (code "117") (name "OUT7") (class "Default")
      (node (ref "LED7") (pin "DOUT") (pinfunction "DOUT_DOUT") (pintype "output"))
      (node (ref "R14") (pin "P$1") (pinfunction "1_P$1") (pintype "passive"))
      (node (ref "R15") (pin "P$1") (pinfunction "1_P$1") (pintype "passive"))
      (node (ref "R16") (pin "P$1") (pinfunction "1_P$1") (pintype "passive"))
      (node (ref "R341") (pin "P$2") (pinfunction "2_P$2") (pintype "passive"))
    )
    (net (code "118") (name "OUT8") (class "Default")
      (node (ref "LED8") (pin "DOUT") (pinfunction "DOUT_DOUT") (pintype "output"))
      (node (ref "R10") (pin "P$1") (pinfunction "1_P$1") (pintype "passive"))
      (node (ref "R11") (pin "P$1") (pinfunction "1_P$1") (pintype "passive"))
      (node (ref "R12") (pin "P$1") (pinfunction "1_P$1") (pintype "passive"))
      (node (ref "R340") (pin "P$2") (pinfunction "2_P$2") (pintype "passive"))
      (node (ref "R9") (pin "P$1") (pinfunction "1_P$1") (pintype "passive"))
    )
    (net (code "119") (name "OUT9") (class "Default")
      (node (ref "LED9") (pin "DOUT") (pinfunction "DOUT_DOUT") (pintype "output"))
      (node (ref "R20") (pin "P$1") (pinfunction "1_P$1") (pintype "passive"))
      (node (ref "R21") (pin "P$1") (pinfunction "1_P$1") (pintype "passive"))
      (node (ref "R22") (pin "P$1") (pinfunction "1_P$1") (pintype "passive"))
      (node (ref "R23") (pin "P$1") (pinfunction "1_P$1") (pintype "passive"))
      (node (ref "R339") (pin "P$2") (pinfunction "2_P$2") (pintype "passive"))
    )
    (net (code "120") (name "OUT10") (class "Default")
      (node (ref "LED10") (pin "DOUT") (pinfunction "DOUT_DOUT") (pintype "output"))
      (node (ref "R29") (pin "P$1") (pinfunction "1_P$1") (pintype "passive"))
      (node (ref "R30") (pin "P$1") (pinfunction "1_P$1") (pintype "passive"))
      (node (ref "R31") (pin "P$1") (pinfunction "1_P$1") (pintype "passive"))
      (node (ref "R338") (pin "P$2") (pinfunction "2_P$2") (pintype "passive"))
      (node (ref "R4") (pin "P$1") (pinfunction "1_P$1") (pintype "passive"))
    )
    (net (code "121") (name "OUT11") (class "Default")
      (node (ref "LED11") (pin "DOUT") (pinfunction "DOUT_DOUT") (pintype "output"))
      (node (ref "R337") (pin "P$2") (pinfunction "2_P$2") (pintype "passive"))
      (node (ref "R46") (pin "P$1") (pinfunction "1_P$1") (pintype "passive"))
      (node (ref "R47") (pin "P$1") (pinfunction "1_P$1") (pintype "passive"))
      (node (ref "R48") (pin "P$1") (pinfunction "1_P$1") (pintype "passive"))
      (node (ref "R49") (pin "P$1") (pinfunction "1_P$1") (pintype "passive"))
    )
    (net (code "122") (name "OUT12") (class "Default")
      (node (ref "LED12") (pin "DOUT") (pinfunction "DOUT_DOUT") (pintype "output"))
      (node (ref "R336") (pin "P$2") (pinfunction "2_P$2") (pintype "passive"))
      (node (ref "R50") (pin "P$1") (pinfunction "1_P$1") (pintype "passive"))
      (node (ref "R51") (pin "P$1") (pinfunction "1_P$1") (pintype "passive"))
      (node (ref "R52") (pin "P$1") (pinfunction "1_P$1") (pintype "passive"))
    )
    (net (code "123") (name "OUT13") (class "Default")
      (node (ref "LED13") (pin "DOUT") (pinfunction "DOUT_DOUT") (pintype "output"))
      (node (ref "R32") (pin "P$1") (pinfunction "1_P$1") (pintype "passive"))
      (node (ref "R33") (pin "P$1") (pinfunction "1_P$1") (pintype "passive"))
      (node (ref "R335") (pin "P$2") (pinfunction "2_P$2") (pintype "passive"))
      (node (ref "R34") (pin "P$1") (pinfunction "1_P$1") (pintype "passive"))
    )
    (net (code "124") (name "OUT14") (class "Default")
      (node (ref "LED14") (pin "DOUT") (pinfunction "DOUT_DOUT") (pintype "output"))
      (node (ref "R24") (pin "P$1") (pinfunction "1_P$1") (pintype "passive"))
      (node (ref "R25") (pin "P$1") (pinfunction "1_P$1") (pintype "passive"))
      (node (ref "R26") (pin "P$1") (pinfunction "1_P$1") (pintype "passive"))
      (node (ref "R27") (pin "P$1") (pinfunction "1_P$1") (pintype "passive"))
      (node (ref "R334") (pin "P$2") (pinfunction "2_P$2") (pintype "passive"))
    )
    (net (code "125") (name "OUT15") (class "Default")
      (node (ref "LED15") (pin "DOUT") (pinfunction "DOUT_DOUT") (pintype "output"))
      (node (ref "R333") (pin "P$2") (pinfunction "2_P$2") (pintype "passive"))
      (node (ref "R65") (pin "P$1") (pinfunction "1_P$1") (pintype "passive"))
      (node (ref "R68") (pin "P$1") (pinfunction "1_P$1") (pintype "passive"))
      (node (ref "R69") (pin "P$1") (pinfunction "1_P$1") (pintype "passive"))
      (node (ref "R70") (pin "P$1") (pinfunction "1_P$1") (pintype "passive"))
    )
    (net (code "126") (name "OUT16") (class "Default")
      (node (ref "LED16") (pin "DOUT") (pinfunction "DOUT_DOUT") (pintype "output"))
      (node (ref "R332") (pin "P$2") (pinfunction "2_P$2") (pintype "passive"))
      (node (ref "R71") (pin "P$1") (pinfunction "1_P$1") (pintype "passive"))
      (node (ref "R72") (pin "P$1") (pinfunction "1_P$1") (pintype "passive"))
      (node (ref "R73") (pin "P$1") (pinfunction "1_P$1") (pintype "passive"))
      (node (ref "R74") (pin "P$1") (pinfunction "1_P$1") (pintype "passive"))
    )
    (net (code "127") (name "OUT17") (class "Default")
      (node (ref "LED17") (pin "DOUT") (pinfunction "DOUT_DOUT") (pintype "output"))
      (node (ref "R331") (pin "P$2") (pinfunction "2_P$2") (pintype "passive"))
      (node (ref "R75") (pin "P$1") (pinfunction "1_P$1") (pintype "passive"))
      (node (ref "R76") (pin "P$1") (pinfunction "1_P$1") (pintype "passive"))
      (node (ref "R77") (pin "P$1") (pinfunction "1_P$1") (pintype "passive"))
      (node (ref "R78") (pin "P$1") (pinfunction "1_P$1") (pintype "passive"))
    )
    (net (code "128") (name "OUT18") (class "Default")
      (node (ref "LED18") (pin "DOUT") (pinfunction "DOUT_DOUT") (pintype "output"))
      (node (ref "R330") (pin "P$2") (pinfunction "2_P$2") (pintype "passive"))
      (node (ref "R79") (pin "P$1") (pinfunction "1_P$1") (pintype "passive"))
      (node (ref "R80") (pin "P$1") (pinfunction "1_P$1") (pintype "passive"))
      (node (ref "R81") (pin "P$1") (pinfunction "1_P$1") (pintype "passive"))
      (node (ref "R82") (pin "P$1") (pinfunction "1_P$1") (pintype "passive"))
    )
    (net (code "129") (name "OUT19") (class "Default")
      (node (ref "LED19") (pin "DOUT") (pinfunction "DOUT_DOUT") (pintype "output"))
      (node (ref "R329") (pin "P$2") (pinfunction "2_P$2") (pintype "passive"))
      (node (ref "R83") (pin "P$1") (pinfunction "1_P$1") (pintype "passive"))
      (node (ref "R84") (pin "P$1") (pinfunction "1_P$1") (pintype "passive"))
      (node (ref "R86") (pin "P$1") (pinfunction "1_P$1") (pintype "passive"))
    )
    (net (code "130") (name "OUT20") (class "Default")
      (node (ref "LED20") (pin "DOUT") (pinfunction "DOUT_DOUT") (pintype "output"))
      (node (ref "R328") (pin "P$2") (pinfunction "2_P$2") (pintype "passive"))
      (node (ref "R87") (pin "P$1") (pinfunction "1_P$1") (pintype "passive"))
      (node (ref "R88") (pin "P$1") (pinfunction "1_P$1") (pintype "passive"))
    )
    (net (code "131") (name "OUT21") (class "Default")
      (node (ref "LED21") (pin "DOUT") (pinfunction "DOUT_DOUT") (pintype "output"))
      (node (ref "R327") (pin "P$2") (pinfunction "2_P$2") (pintype "passive"))
      (node (ref "R53") (pin "P$1") (pinfunction "1_P$1") (pintype "passive"))
      (node (ref "R54") (pin "P$1") (pinfunction "1_P$1") (pintype "passive"))
      (node (ref "R55") (pin "P$1") (pinfunction "1_P$1") (pintype "passive"))
    )
    (net (code "132") (name "OUT22") (class "Default")
      (node (ref "LED22") (pin "DOUT") (pinfunction "DOUT_DOUT") (pintype "output"))
      (node (ref "R326") (pin "P$2") (pinfunction "2_P$2") (pintype "passive"))
      (node (ref "R85") (pin "P$1") (pinfunction "1_P$1") (pintype "passive"))
      (node (ref "R89") (pin "P$1") (pinfunction "1_P$1") (pintype "passive"))
      (node (ref "R90") (pin "P$1") (pinfunction "1_P$1") (pintype "passive"))
      (node (ref "R91") (pin "P$1") (pinfunction "1_P$1") (pintype "passive"))
    )
    (net (code "133") (name "OUT23") (class "Default")
      (node (ref "LED23") (pin "DOUT") (pinfunction "DOUT_DOUT") (pintype "output"))
      (node (ref "R107") (pin "P$1") (pinfunction "1_P$1") (pintype "passive"))
      (node (ref "R108") (pin "P$1") (pinfunction "1_P$1") (pintype "passive"))
      (node (ref "R109") (pin "P$1") (pinfunction "1_P$1") (pintype "passive"))
      (node (ref "R110") (pin "P$1") (pinfunction "1_P$1") (pintype "passive"))
      (node (ref "R325") (pin "P$2") (pinfunction "2_P$2") (pintype "passive"))
    )
    (net (code "134") (name "OUT24") (class "Default")
      (node (ref "LED24") (pin "DOUT") (pinfunction "DOUT_DOUT") (pintype "output"))
      (node (ref "R111") (pin "P$1") (pinfunction "1_P$1") (pintype "passive"))
      (node (ref "R112") (pin "P$1") (pinfunction "1_P$1") (pintype "passive"))
      (node (ref "R113") (pin "P$1") (pinfunction "1_P$1") (pintype "passive"))
      (node (ref "R114") (pin "P$1") (pinfunction "1_P$1") (pintype "passive"))
      (node (ref "R324") (pin "P$2") (pinfunction "2_P$2") (pintype "passive"))
    )
    (net (code "135") (name "OUT25") (class "Default")
      (node (ref "LED25") (pin "DOUT") (pinfunction "DOUT_DOUT") (pintype "output"))
      (node (ref "R115") (pin "P$1") (pinfunction "1_P$1") (pintype "passive"))
      (node (ref "R116") (pin "P$1") (pinfunction "1_P$1") (pintype "passive"))
      (node (ref "R117") (pin "P$1") (pinfunction "1_P$1") (pintype "passive"))
      (node (ref "R118") (pin "P$1") (pinfunction "1_P$1") (pintype "passive"))
      (node (ref "R323") (pin "P$2") (pinfunction "2_P$2") (pintype "passive"))
    )
    (net (code "136") (name "OUT26") (class "Default")
      (node (ref "LED26") (pin "DOUT") (pinfunction "DOUT_DOUT") (pintype "output"))
      (node (ref "R119") (pin "P$1") (pinfunction "1_P$1") (pintype "passive"))
      (node (ref "R120") (pin "P$1") (pinfunction "1_P$1") (pintype "passive"))
      (node (ref "R121") (pin "P$1") (pinfunction "1_P$1") (pintype "passive"))
      (node (ref "R122") (pin "P$1") (pinfunction "1_P$1") (pintype "passive"))
      (node (ref "R322") (pin "P$2") (pinfunction "2_P$2") (pintype "passive"))
    )
    (net (code "137") (name "OUT27") (class "Default")
      (node (ref "LED27") (pin "DOUT") (pinfunction "DOUT_DOUT") (pintype "output"))
      (node (ref "R123") (pin "P$1") (pinfunction "1_P$1") (pintype "passive"))
      (node (ref "R124") (pin "P$1") (pinfunction "1_P$1") (pintype "passive"))
      (node (ref "R125") (pin "P$1") (pinfunction "1_P$1") (pintype "passive"))
      (node (ref "R126") (pin "P$1") (pinfunction "1_P$1") (pintype "passive"))
      (node (ref "R321") (pin "P$2") (pinfunction "2_P$2") (pintype "passive"))
    )
    (net (code "138") (name "OUT28") (class "Default")
      (node (ref "LED28") (pin "DOUT") (pinfunction "DOUT_DOUT") (pintype "output"))
      (node (ref "R127") (pin "P$1") (pinfunction "1_P$1") (pintype "passive"))
      (node (ref "R128") (pin "P$1") (pinfunction "1_P$1") (pintype "passive"))
      (node (ref "R129") (pin "P$1") (pinfunction "1_P$1") (pintype "passive"))
      (node (ref "R320") (pin "P$2") (pinfunction "2_P$2") (pintype "passive"))
    )
    (net (code "139") (name "OUT29") (class "Default")
      (node (ref "LED29") (pin "DOUT") (pinfunction "DOUT_DOUT") (pintype "output"))
      (node (ref "R319") (pin "P$2") (pinfunction "2_P$2") (pintype "passive"))
      (node (ref "R56") (pin "P$1") (pinfunction "1_P$1") (pintype "passive"))
      (node (ref "R57") (pin "P$1") (pinfunction "1_P$1") (pintype "passive"))
      (node (ref "R58") (pin "P$1") (pinfunction "1_P$1") (pintype "passive"))
    )
    (net (code "140") (name "OUT30") (class "Default")
      (node (ref "LED30") (pin "DOUT") (pinfunction "DOUT_DOUT") (pintype "output"))
      (node (ref "R318") (pin "P$2") (pinfunction "2_P$2") (pintype "passive"))
      (node (ref "R92") (pin "P$1") (pinfunction "1_P$1") (pintype "passive"))
      (node (ref "R93") (pin "P$1") (pinfunction "1_P$1") (pintype "passive"))
      (node (ref "R94") (pin "P$1") (pinfunction "1_P$1") (pintype "passive"))
      (node (ref "R95") (pin "P$1") (pinfunction "1_P$1") (pintype "passive"))
    )
    (net (code "141") (name "OUT31") (class "Default")
      (node (ref "LED31") (pin "DOUT") (pinfunction "DOUT_DOUT") (pintype "output"))
      (node (ref "R130") (pin "P$1") (pinfunction "1_P$1") (pintype "passive"))
      (node (ref "R131") (pin "P$1") (pinfunction "1_P$1") (pintype "passive"))
      (node (ref "R132") (pin "P$1") (pinfunction "1_P$1") (pintype "passive"))
      (node (ref "R133") (pin "P$1") (pinfunction "1_P$1") (pintype "passive"))
      (node (ref "R317") (pin "P$2") (pinfunction "2_P$2") (pintype "passive"))
    )
    (net (code "142") (name "OUT32") (class "Default")
      (node (ref "LED32") (pin "DOUT") (pinfunction "DOUT_DOUT") (pintype "output"))
      (node (ref "R134") (pin "P$1") (pinfunction "1_P$1") (pintype "passive"))
      (node (ref "R135") (pin "P$1") (pinfunction "1_P$1") (pintype "passive"))
      (node (ref "R136") (pin "P$1") (pinfunction "1_P$1") (pintype "passive"))
      (node (ref "R137") (pin "P$1") (pinfunction "1_P$1") (pintype "passive"))
      (node (ref "R316") (pin "P$2") (pinfunction "2_P$2") (pintype "passive"))
    )
    (net (code "143") (name "OUT33") (class "Default")
      (node (ref "LED33") (pin "DOUT") (pinfunction "DOUT_DOUT") (pintype "output"))
      (node (ref "R138") (pin "P$1") (pinfunction "1_P$1") (pintype "passive"))
      (node (ref "R139") (pin "P$1") (pinfunction "1_P$1") (pintype "passive"))
      (node (ref "R140") (pin "P$1") (pinfunction "1_P$1") (pintype "passive"))
      (node (ref "R141") (pin "P$1") (pinfunction "1_P$1") (pintype "passive"))
      (node (ref "R315") (pin "P$2") (pinfunction "2_P$2") (pintype "passive"))
    )
    (net (code "144") (name "OUT34") (class "Default")
      (node (ref "LED34") (pin "DOUT") (pinfunction "DOUT_DOUT") (pintype "output"))
      (node (ref "R142") (pin "P$1") (pinfunction "1_P$1") (pintype "passive"))
      (node (ref "R143") (pin "P$1") (pinfunction "1_P$1") (pintype "passive"))
      (node (ref "R144") (pin "P$1") (pinfunction "1_P$1") (pintype "passive"))
      (node (ref "R145") (pin "P$1") (pinfunction "1_P$1") (pintype "passive"))
      (node (ref "R314") (pin "P$2") (pinfunction "2_P$2") (pintype "passive"))
    )
    (net (code "145") (name "OUT35") (class "Default")
      (node (ref "LED35") (pin "DOUT") (pinfunction "DOUT_DOUT") (pintype "output"))
      (node (ref "R146") (pin "P$1") (pinfunction "1_P$1") (pintype "passive"))
      (node (ref "R147") (pin "P$1") (pinfunction "1_P$1") (pintype "passive"))
      (node (ref "R148") (pin "P$1") (pinfunction "1_P$1") (pintype "passive"))
      (node (ref "R149") (pin "P$1") (pinfunction "1_P$1") (pintype "passive"))
      (node (ref "R313") (pin "P$2") (pinfunction "2_P$2") (pintype "passive"))
    )
    (net (code "146") (name "OUT36") (class "Default")
      (node (ref "LED36") (pin "DOUT") (pinfunction "DOUT_DOUT") (pintype "output"))
      (node (ref "R150") (pin "P$1") (pinfunction "1_P$1") (pintype "passive"))
      (node (ref "R151") (pin "P$1") (pinfunction "1_P$1") (pintype "passive"))
      (node (ref "R152") (pin "P$1") (pinfunction "1_P$1") (pintype "passive"))
      (node (ref "R312") (pin "P$2") (pinfunction "2_P$2") (pintype "passive"))
    )
    (net (code "147") (name "OUT37") (class "Default")
      (node (ref "LED37") (pin "DOUT") (pinfunction "DOUT_DOUT") (pintype "output"))
      (node (ref "R311") (pin "P$2") (pinfunction "2_P$2") (pintype "passive"))
      (node (ref "R59") (pin "P$1") (pinfunction "1_P$1") (pintype "passive"))
      (node (ref "R60") (pin "P$1") (pinfunction "1_P$1") (pintype "passive"))
      (node (ref "R61") (pin "P$1") (pinfunction "1_P$1") (pintype "passive"))
    )
    (net (code "148") (name "OUT38") (class "Default")
      (node (ref "LED38") (pin "DOUT") (pinfunction "DOUT_DOUT") (pintype "output"))
      (node (ref "R310") (pin "P$2") (pinfunction "2_P$2") (pintype "passive"))
      (node (ref "R96") (pin "P$1") (pinfunction "1_P$1") (pintype "passive"))
      (node (ref "R97") (pin "P$1") (pinfunction "1_P$1") (pintype "passive"))
      (node (ref "R98") (pin "P$1") (pinfunction "1_P$1") (pintype "passive"))
      (node (ref "R99") (pin "P$1") (pinfunction "1_P$1") (pintype "passive"))
    )
    (net (code "149") (name "OUT39") (class "Default")
      (node (ref "LED39") (pin "DOUT") (pinfunction "DOUT_DOUT") (pintype "output"))
      (node (ref "R153") (pin "P$1") (pinfunction "1_P$1") (pintype "passive"))
      (node (ref "R154") (pin "P$1") (pinfunction "1_P$1") (pintype "passive"))
      (node (ref "R155") (pin "P$1") (pinfunction "1_P$1") (pintype "passive"))
      (node (ref "R156") (pin "P$1") (pinfunction "1_P$1") (pintype "passive"))
      (node (ref "R309") (pin "P$2") (pinfunction "2_P$2") (pintype "passive"))
    )
    (net (code "150") (name "OUT40") (class "Default")
      (node (ref "LED40") (pin "DOUT") (pinfunction "DOUT_DOUT") (pintype "output"))
      (node (ref "R157") (pin "P$1") (pinfunction "1_P$1") (pintype "passive"))
      (node (ref "R158") (pin "P$1") (pinfunction "1_P$1") (pintype "passive"))
      (node (ref "R159") (pin "P$1") (pinfunction "1_P$1") (pintype "passive"))
      (node (ref "R160") (pin "P$1") (pinfunction "1_P$1") (pintype "passive"))
      (node (ref "R308") (pin "P$2") (pinfunction "2_P$2") (pintype "passive"))
    )
    (net (code "151") (name "OUT41") (class "Default")
      (node (ref "LED41") (pin "DOUT") (pinfunction "DOUT_DOUT") (pintype "output"))
      (node (ref "R161") (pin "P$1") (pinfunction "1_P$1") (pintype "passive"))
      (node (ref "R162") (pin "P$1") (pinfunction "1_P$1") (pintype "passive"))
      (node (ref "R163") (pin "P$1") (pinfunction "1_P$1") (pintype "passive"))
      (node (ref "R164") (pin "P$1") (pinfunction "1_P$1") (pintype "passive"))
      (node (ref "R307") (pin "P$2") (pinfunction "2_P$2") (pintype "passive"))
    )
    (net (code "152") (name "OUT42") (class "Default")
      (node (ref "LED42") (pin "DOUT") (pinfunction "DOUT_DOUT") (pintype "output"))
      (node (ref "R165") (pin "P$1") (pinfunction "1_P$1") (pintype "passive"))
      (node (ref "R166") (pin "P$1") (pinfunction "1_P$1") (pintype "passive"))
      (node (ref "R167") (pin "P$1") (pinfunction "1_P$1") (pintype "passive"))
      (node (ref "R168") (pin "P$1") (pinfunction "1_P$1") (pintype "passive"))
      (node (ref "R306") (pin "P$2") (pinfunction "2_P$2") (pintype "passive"))
    )
    (net (code "153") (name "OUT43") (class "Default")
      (node (ref "LED43") (pin "DOUT") (pinfunction "DOUT_DOUT") (pintype "output"))
      (node (ref "R169") (pin "P$1") (pinfunction "1_P$1") (pintype "passive"))
      (node (ref "R170") (pin "P$1") (pinfunction "1_P$1") (pintype "passive"))
      (node (ref "R171") (pin "P$1") (pinfunction "1_P$1") (pintype "passive"))
      (node (ref "R172") (pin "P$1") (pinfunction "1_P$1") (pintype "passive"))
      (node (ref "R305") (pin "P$2") (pinfunction "2_P$2") (pintype "passive"))
    )
    (net (code "154") (name "OUT44") (class "Default")
      (node (ref "LED44") (pin "DOUT") (pinfunction "DOUT_DOUT") (pintype "output"))
      (node (ref "R173") (pin "P$1") (pinfunction "1_P$1") (pintype "passive"))
      (node (ref "R174") (pin "P$1") (pinfunction "1_P$1") (pintype "passive"))
      (node (ref "R175") (pin "P$1") (pinfunction "1_P$1") (pintype "passive"))
      (node (ref "R304") (pin "P$2") (pinfunction "2_P$2") (pintype "passive"))
    )
    (net (code "155") (name "OUT45") (class "Default")
      (node (ref "LED45") (pin "DOUT") (pinfunction "DOUT_DOUT") (pintype "output"))
      (node (ref "R303") (pin "P$2") (pinfunction "2_P$2") (pintype "passive"))
      (node (ref "R62") (pin "P$1") (pinfunction "1_P$1") (pintype "passive"))
      (node (ref "R63") (pin "P$1") (pinfunction "1_P$1") (pintype "passive"))
      (node (ref "R64") (pin "P$1") (pinfunction "1_P$1") (pintype "passive"))
    )
    (net (code "156") (name "OUT46") (class "Default")
      (node (ref "LED46") (pin "DOUT") (pinfunction "DOUT_DOUT") (pintype "output"))
      (node (ref "R100") (pin "P$1") (pinfunction "1_P$1") (pintype "passive"))
      (node (ref "R101") (pin "P$1") (pinfunction "1_P$1") (pintype "passive"))
      (node (ref "R102") (pin "P$1") (pinfunction "1_P$1") (pintype "passive"))
      (node (ref "R103") (pin "P$1") (pinfunction "1_P$1") (pintype "passive"))
      (node (ref "R302") (pin "P$2") (pinfunction "2_P$2") (pintype "passive"))
    )
    (net (code "157") (name "OUT47") (class "Default")
      (node (ref "LED47") (pin "DOUT") (pinfunction "DOUT_DOUT") (pintype "output"))
      (node (ref "R176") (pin "P$1") (pinfunction "1_P$1") (pintype "passive"))
      (node (ref "R177") (pin "P$1") (pinfunction "1_P$1") (pintype "passive"))
      (node (ref "R178") (pin "P$1") (pinfunction "1_P$1") (pintype "passive"))
      (node (ref "R179") (pin "P$1") (pinfunction "1_P$1") (pintype "passive"))
      (node (ref "R301") (pin "P$2") (pinfunction "2_P$2") (pintype "passive"))
    )
    (net (code "158") (name "OUT48") (class "Default")
      (node (ref "LED48") (pin "DOUT") (pinfunction "DOUT_DOUT") (pintype "output"))
      (node (ref "R180") (pin "P$1") (pinfunction "1_P$1") (pintype "passive"))
      (node (ref "R181") (pin "P$1") (pinfunction "1_P$1") (pintype "passive"))
      (node (ref "R182") (pin "P$1") (pinfunction "1_P$1") (pintype "passive"))
      (node (ref "R183") (pin "P$1") (pinfunction "1_P$1") (pintype "passive"))
      (node (ref "R300") (pin "P$2") (pinfunction "2_P$2") (pintype "passive"))
    )
    (net (code "159") (name "OUT49") (class "Default")
      (node (ref "LED49") (pin "DOUT") (pinfunction "DOUT_DOUT") (pintype "output"))
      (node (ref "R184") (pin "P$1") (pinfunction "1_P$1") (pintype "passive"))
      (node (ref "R185") (pin "P$1") (pinfunction "1_P$1") (pintype "passive"))
      (node (ref "R186") (pin "P$1") (pinfunction "1_P$1") (pintype "passive"))
      (node (ref "R187") (pin "P$1") (pinfunction "1_P$1") (pintype "passive"))
      (node (ref "R299") (pin "P$2") (pinfunction "2_P$2") (pintype "passive"))
    )
    (net (code "160") (name "OUT50") (class "Default")
      (node (ref "LED50") (pin "DOUT") (pinfunction "DOUT_DOUT") (pintype "output"))
      (node (ref "R188") (pin "P$1") (pinfunction "1_P$1") (pintype "passive"))
      (node (ref "R189") (pin "P$1") (pinfunction "1_P$1") (pintype "passive"))
      (node (ref "R190") (pin "P$1") (pinfunction "1_P$1") (pintype "passive"))
      (node (ref "R191") (pin "P$1") (pinfunction "1_P$1") (pintype "passive"))
      (node (ref "R298") (pin "P$2") (pinfunction "2_P$2") (pintype "passive"))
    )
    (net (code "161") (name "OUT51") (class "Default")
      (node (ref "LED51") (pin "DOUT") (pinfunction "DOUT_DOUT") (pintype "output"))
      (node (ref "R192") (pin "P$1") (pinfunction "1_P$1") (pintype "passive"))
      (node (ref "R193") (pin "P$1") (pinfunction "1_P$1") (pintype "passive"))
      (node (ref "R194") (pin "P$1") (pinfunction "1_P$1") (pintype "passive"))
      (node (ref "R195") (pin "P$1") (pinfunction "1_P$1") (pintype "passive"))
      (node (ref "R297") (pin "P$2") (pinfunction "2_P$2") (pintype "passive"))
    )
    (net (code "162") (name "OUT52") (class "Default")
      (node (ref "LED52") (pin "DOUT") (pinfunction "DOUT_DOUT") (pintype "output"))
      (node (ref "R196") (pin "P$1") (pinfunction "1_P$1") (pintype "passive"))
      (node (ref "R197") (pin "P$1") (pinfunction "1_P$1") (pintype "passive"))
      (node (ref "R198") (pin "P$1") (pinfunction "1_P$1") (pintype "passive"))
      (node (ref "R296") (pin "P$2") (pinfunction "2_P$2") (pintype "passive"))
    )
    (net (code "163") (name "OUT53") (class "Default")
      (node (ref "LED53") (pin "DOUT") (pinfunction "DOUT_DOUT") (pintype "output"))
      (node (ref "R295") (pin "P$2") (pinfunction "2_P$2") (pintype "passive"))
      (node (ref "R66") (pin "P$1") (pinfunction "1_P$1") (pintype "passive"))
      (node (ref "R67") (pin "P$1") (pinfunction "1_P$1") (pintype "passive"))
    )
    (net (code "164") (name "OUT54") (class "Default")
      (node (ref "LED54") (pin "DOUT") (pinfunction "DOUT_DOUT") (pintype "output"))
      (node (ref "R104") (pin "P$1") (pinfunction "1_P$1") (pintype "passive"))
      (node (ref "R105") (pin "P$1") (pinfunction "1_P$1") (pintype "passive"))
      (node (ref "R106") (pin "P$1") (pinfunction "1_P$1") (pintype "passive"))
      (node (ref "R294") (pin "P$2") (pinfunction "2_P$2") (pintype "passive"))
    )
    (net (code "165") (name "OUT55") (class "Default")
      (node (ref "LED55") (pin "DOUT") (pinfunction "DOUT_DOUT") (pintype "output"))
      (node (ref "R199") (pin "P$1") (pinfunction "1_P$1") (pintype "passive"))
      (node (ref "R200") (pin "P$1") (pinfunction "1_P$1") (pintype "passive"))
      (node (ref "R201") (pin "P$1") (pinfunction "1_P$1") (pintype "passive"))
      (node (ref "R293") (pin "P$2") (pinfunction "2_P$2") (pintype "passive"))
    )
    (net (code "166") (name "OUT56") (class "Default")
      (node (ref "LED56") (pin "DOUT") (pinfunction "DOUT_DOUT") (pintype "output"))
      (node (ref "R202") (pin "P$1") (pinfunction "1_P$1") (pintype "passive"))
      (node (ref "R203") (pin "P$1") (pinfunction "1_P$1") (pintype "passive"))
      (node (ref "R204") (pin "P$1") (pinfunction "1_P$1") (pintype "passive"))
      (node (ref "R292") (pin "P$2") (pinfunction "2_P$2") (pintype "passive"))
    )
    (net (code "167") (name "OUT57") (class "Default")
      (node (ref "LED57") (pin "DOUT") (pinfunction "DOUT_DOUT") (pintype "output"))
      (node (ref "R205") (pin "P$1") (pinfunction "1_P$1") (pintype "passive"))
      (node (ref "R206") (pin "P$1") (pinfunction "1_P$1") (pintype "passive"))
      (node (ref "R207") (pin "P$1") (pinfunction "1_P$1") (pintype "passive"))
      (node (ref "R291") (pin "P$2") (pinfunction "2_P$2") (pintype "passive"))
    )
    (net (code "168") (name "OUT58") (class "Default")
      (node (ref "LED58") (pin "DOUT") (pinfunction "DOUT_DOUT") (pintype "output"))
      (node (ref "R208") (pin "P$1") (pinfunction "1_P$1") (pintype "passive"))
      (node (ref "R209") (pin "P$1") (pinfunction "1_P$1") (pintype "passive"))
      (node (ref "R210") (pin "P$1") (pinfunction "1_P$1") (pintype "passive"))
      (node (ref "R290") (pin "P$2") (pinfunction "2_P$2") (pintype "passive"))
    )
    (net (code "169") (name "OUT59") (class "Default")
      (node (ref "LED59") (pin "DOUT") (pinfunction "DOUT_DOUT") (pintype "output"))
      (node (ref "R211") (pin "P$1") (pinfunction "1_P$1") (pintype "passive"))
      (node (ref "R212") (pin "P$1") (pinfunction "1_P$1") (pintype "passive"))
      (node (ref "R213") (pin "P$1") (pinfunction "1_P$1") (pintype "passive"))
      (node (ref "R289") (pin "P$2") (pinfunction "2_P$2") (pintype "passive"))
    )
    (net (code "170") (name "OUT60") (class "Default")
      (node (ref "LED60") (pin "DOUT") (pinfunction "DOUT_DOUT") (pintype "output"))
      (node (ref "R214") (pin "P$1") (pinfunction "1_P$1") (pintype "passive"))
      (node (ref "R215") (pin "P$1") (pinfunction "1_P$1") (pintype "passive"))
      (node (ref "R288") (pin "P$2") (pinfunction "2_P$2") (pintype "passive"))
    )
    (net (code "171") (name "RST") (class "Default")
      (node (ref "IC2") (pin "8") (pinfunction "(~{RESET}/ADC10/PCINT15)PB7_8") (pintype "bidirectional"))
      (node (ref "R6") (pin "P$1") (pinfunction "1_P$1") (pintype "passive"))
      (node (ref "TP2") (pin "P$1") (pinfunction "P$1_P$1") (pintype "bidirectional"))
    )
    (net (code "172") (name "SCKI") (class "Default")
      (node (ref "IC1") (pin "3") (pinfunction "SCKI_3") (pintype "input"))
      (node (ref "IC2") (pin "1") (pinfunction "(SCK/USCK/SCL/~{OC1B}/PCINT10)PB2_1") (pintype "bidirectional"))
      (node (ref "TP5") (pin "P$1") (pinfunction "P$1_P$1") (pintype "bidirectional"))
    )
    (net (code "173") (name "SDTI") (class "Default")
      (node (ref "IC1") (pin "2") (pinfunction "SDTI_2") (pintype "input"))
      (node (ref "IC2") (pin "2") (pinfunction "(OC1B/PCINT11)PB3_2") (pintype "bidirectional"))
    )
    (net (code "174") (name "SDTO") (class "Default")
      (node (ref "IC1") (pin "22") (pinfunction "SDTO_22") (pintype "output"))
      (node (ref "IC2") (pin "7") (pinfunction "(T0/INT0/ADC9/PCINT14)PB6_7") (pintype "bidirectional"))
    )
    (net (code "175") (name "SERIAL-BUS") (class "Default")
      (node (ref "IC2") (pin "18") (pinfunction "(SDA/DI/ADC0/PCINT0)PA0_18") (pintype "bidirectional"))
      (node (ref "Q1") (pin "3") (pinfunction "C_3") (pintype "passive"))
      (node (ref "X2") (pin "5") (pinfunction "5_5") (pintype "passive"))
    )
    (net (code "176") (name "VCC") (class "Default")
      (node (ref "C1") (pin "P$1") (pinfunction "1_P$1") (pintype "passive"))
      (node (ref "C10") (pin "P$1") (pinfunction "1_P$1") (pintype "passive"))
      (node (ref "C11") (pin "P$1") (pinfunction "1_P$1") (pintype "passive"))
      (node (ref "C12") (pin "P$1") (pinfunction "1_P$1") (pintype "passive"))
      (node (ref "C13") (pin "P$1") (pinfunction "1_P$1") (pintype "passive"))
      (node (ref "C14") (pin "P$1") (pinfunction "1_P$1") (pintype "passive"))
      (node (ref "C15") (pin "P$1") (pinfunction "1_P$1") (pintype "passive"))
      (node (ref "C16") (pin "P$1") (pinfunction "1_P$1") (pintype "passive"))
      (node (ref "C17") (pin "P$1") (pinfunction "1_P$1") (pintype "passive"))
      (node (ref "C18") (pin "P$1") (pinfunction "1_P$1") (pintype "passive"))
      (node (ref "C19") (pin "P$1") (pinfunction "1_P$1") (pintype "passive"))
      (node (ref "C2") (pin "P$1") (pinfunction "1_P$1") (pintype "passive"))
      (node (ref "C20") (pin "P$1") (pinfunction "1_P$1") (pintype "passive"))
      (node (ref "C21") (pin "P$1") (pinfunction "1_P$1") (pintype "passive"))
      (node (ref "C22") (pin "P$1") (pinfunction "1_P$1") (pintype "passive"))
      (node (ref "C23") (pin "P$1") (pinfunction "1_P$1") (pintype "passive"))
      (node (ref "C24") (pin "P$1") (pinfunction "1_P$1") (pintype "passive"))
      (node (ref "C25") (pin "P$1") (pinfunction "1_P$1") (pintype "passive"))
      (node (ref "C26") (pin "P$1") (pinfunction "1_P$1") (pintype "passive"))
      (node (ref "C27") (pin "P$1") (pinfunction "1_P$1") (pintype "passive"))
      (node (ref "C28") (pin "P$1") (pinfunction "1_P$1") (pintype "passive"))
      (node (ref "C29") (pin "P$1") (pinfunction "1_P$1") (pintype "passive"))
      (node (ref "C3") (pin "P$1") (pinfunction "1_P$1") (pintype "passive"))
      (node (ref "C30") (pin "P$1") (pinfunction "1_P$1") (pintype "passive"))
      (node (ref "C31") (pin "P$1") (pinfunction "1_P$1") (pintype "passive"))
      (node (ref "C32") (pin "P$1") (pinfunction "1_P$1") (pintype "passive"))
      (node (ref "C33") (pin "P$1") (pinfunction "1_P$1") (pintype "passive"))
      (node (ref "C34") (pin "P$1") (pinfunction "1_P$1") (pintype "passive"))
      (node (ref "C35") (pin "P$1") (pinfunction "1_P$1") (pintype "passive"))
      (node (ref "C36") (pin "P$1") (pinfunction "1_P$1") (pintype "passive"))
      (node (ref "C37") (pin "P$1") (pinfunction "1_P$1") (pintype "passive"))
      (node (ref "C38") (pin "P$1") (pinfunction "1_P$1") (pintype "passive"))
      (node (ref "C39") (pin "P$1") (pinfunction "1_P$1") (pintype "passive"))
      (node (ref "C4") (pin "P$1") (pinfunction "1_P$1") (pintype "passive"))
      (node (ref "C40") (pin "P$1") (pinfunction "1_P$1") (pintype "passive"))
      (node (ref "C41") (pin "P$1") (pinfunction "1_P$1") (pintype "passive"))
      (node (ref "C42") (pin "P$1") (pinfunction "1_P$1") (pintype "passive"))
      (node (ref "C43") (pin "P$1") (pinfunction "1_P$1") (pintype "passive"))
      (node (ref "C44") (pin "P$1") (pinfunction "1_P$1") (pintype "passive"))
      (node (ref "C45") (pin "P$1") (pinfunction "1_P$1") (pintype "passive"))
      (node (ref "C46") (pin "P$1") (pinfunction "1_P$1") (pintype "passive"))
      (node (ref "C47") (pin "P$1") (pinfunction "1_P$1") (pintype "passive"))
      (node (ref "C48") (pin "P$1") (pinfunction "1_P$1") (pintype "passive"))
      (node (ref "C49") (pin "P$1") (pinfunction "1_P$1") (pintype "passive"))
      (node (ref "C5") (pin "P$1") (pinfunction "1_P$1") (pintype "passive"))
      (node (ref "C50") (pin "P$1") (pinfunction "1_P$1") (pintype "passive"))
      (node (ref "C51") (pin "P$1") (pinfunction "1_P$1") (pintype "passive"))
      (node (ref "C52") (pin "P$1") (pinfunction "1_P$1") (pintype "passive"))
      (node (ref "C53") (pin "P$1") (pinfunction "1_P$1") (pintype "passive"))
      (node (ref "C54") (pin "P$1") (pinfunction "1_P$1") (pintype "passive"))
      (node (ref "C55") (pin "P$1") (pinfunction "1_P$1") (pintype "passive"))
      (node (ref "C56") (pin "P$1") (pinfunction "1_P$1") (pintype "passive"))
      (node (ref "C57") (pin "P$1") (pinfunction "1_P$1") (pintype "passive"))
      (node (ref "C58") (pin "P$1") (pinfunction "1_P$1") (pintype "passive"))
      (node (ref "C59") (pin "P$1") (pinfunction "1_P$1") (pintype "passive"))
      (node (ref "C6") (pin "P$1") (pinfunction "1_P$1") (pintype "passive"))
      (node (ref "C60") (pin "P$1") (pinfunction "1_P$1") (pintype "passive"))
      (node (ref "C61") (pin "P$1") (pinfunction "1_P$1") (pintype "passive"))
      (node (ref "C62") (pin "P$1") (pinfunction "1_P$1") (pintype "passive"))
      (node (ref "C63") (pin "P$1") (pinfunction "1_P$1") (pintype "passive"))
      (node (ref "C7") (pin "P$1") (pinfunction "1_P$1") (pintype "passive"))
      (node (ref "C8") (pin "P$1") (pinfunction "1_P$1") (pintype "passive"))
      (node (ref "C9") (pin "P$1") (pinfunction "1_P$1") (pintype "passive"))
      (node (ref "IC1") (pin "24") (pinfunction "VCC_24") (pintype "power_in"))
      (node (ref "IC2") (pin "13") (pinfunction "AVCC_13") (pintype "bidirectional"))
      (node (ref "IC2") (pin "3") (pinfunction "VCC_3") (pintype "bidirectional"))
      (node (ref "LED1") (pin "VDD") (pinfunction "VCC_VDD") (pintype "power_in"))
      (node (ref "LED10") (pin "VDD") (pinfunction "VCC_VDD") (pintype "power_in"))
      (node (ref "LED11") (pin "VDD") (pinfunction "VCC_VDD") (pintype "power_in"))
      (node (ref "LED12") (pin "VDD") (pinfunction "VCC_VDD") (pintype "power_in"))
      (node (ref "LED13") (pin "VDD") (pinfunction "VCC_VDD") (pintype "power_in"))
      (node (ref "LED14") (pin "VDD") (pinfunction "VCC_VDD") (pintype "power_in"))
      (node (ref "LED15") (pin "VDD") (pinfunction "VCC_VDD") (pintype "power_in"))
      (node (ref "LED16") (pin "VDD") (pinfunction "VCC_VDD") (pintype "power_in"))
      (node (ref "LED17") (pin "VDD") (pinfunction "VCC_VDD") (pintype "power_in"))
      (node (ref "LED18") (pin "VDD") (pinfunction "VCC_VDD") (pintype "power_in"))
      (node (ref "LED19") (pin "VDD") (pinfunction "VCC_VDD") (pintype "power_in"))
      (node (ref "LED2") (pin "VDD") (pinfunction "VCC_VDD") (pintype "power_in"))
      (node (ref "LED20") (pin "VDD") (pinfunction "VCC_VDD") (pintype "power_in"))
      (node (ref "LED21") (pin "VDD") (pinfunction "VCC_VDD") (pintype "power_in"))
      (node (ref "LED22") (pin "VDD") (pinfunction "VCC_VDD") (pintype "power_in"))
      (node (ref "LED23") (pin "VDD") (pinfunction "VCC_VDD") (pintype "power_in"))
      (node (ref "LED24") (pin "VDD") (pinfunction "VCC_VDD") (pintype "power_in"))
      (node (ref "LED25") (pin "VDD") (pinfunction "VCC_VDD") (pintype "power_in"))
      (node (ref "LED26") (pin "VDD") (pinfunction "VCC_VDD") (pintype "power_in"))
      (node (ref "LED27") (pin "VDD") (pinfunction "VCC_VDD") (pintype "power_in"))
      (node (ref "LED28") (pin "VDD") (pinfunction "VCC_VDD") (pintype "power_in"))
      (node (ref "LED29") (pin "VDD") (pinfunction "VCC_VDD") (pintype "power_in"))
      (node (ref "LED3") (pin "VDD") (pinfunction "VCC_VDD") (pintype "power_in"))
      (node (ref "LED30") (pin "VDD") (pinfunction "VCC_VDD") (pintype "power_in"))
      (node (ref "LED31") (pin "VDD") (pinfunction "VCC_VDD") (pintype "power_in"))
      (node (ref "LED32") (pin "VDD") (pinfunction "VCC_VDD") (pintype "power_in"))
      (node (ref "LED33") (pin "VDD") (pinfunction "VCC_VDD") (pintype "power_in"))
      (node (ref "LED34") (pin "VDD") (pinfunction "VCC_VDD") (pintype "power_in"))
      (node (ref "LED35") (pin "VDD") (pinfunction "VCC_VDD") (pintype "power_in"))
      (node (ref "LED36") (pin "VDD") (pinfunction "VCC_VDD") (pintype "power_in"))
      (node (ref "LED37") (pin "VDD") (pinfunction "VCC_VDD") (pintype "power_in"))
      (node (ref "LED38") (pin "VDD") (pinfunction "VCC_VDD") (pintype "power_in"))
      (node (ref "LED39") (pin "VDD") (pinfunction "VCC_VDD") (pintype "power_in"))
      (node (ref "LED4") (pin "VDD") (pinfunction "VCC_VDD") (pintype "power_in"))
      (node (ref "LED40") (pin "VDD") (pinfunction "VCC_VDD") (pintype "power_in"))
      (node (ref "LED41") (pin "VDD") (pinfunction "VCC_VDD") (pintype "power_in"))
      (node (ref "LED42") (pin "VDD") (pinfunction "VCC_VDD") (pintype "power_in"))
      (node (ref "LED43") (pin "VDD") (pinfunction "VCC_VDD") (pintype "power_in"))
      (node (ref "LED44") (pin "VDD") (pinfunction "VCC_VDD") (pintype "power_in"))
      (node (ref "LED45") (pin "VDD") (pinfunction "VCC_VDD") (pintype "power_in"))
      (node (ref "LED46") (pin "VDD") (pinfunction "VCC_VDD") (pintype "power_in"))
      (node (ref "LED47") (pin "VDD") (pinfunction "VCC_VDD") (pintype "power_in"))
      (node (ref "LED48") (pin "VDD") (pinfunction "VCC_VDD") (pintype "power_in"))
      (node (ref "LED49") (pin "VDD") (pinfunction "VCC_VDD") (pintype "power_in"))
      (node (ref "LED5") (pin "VDD") (pinfunction "VCC_VDD") (pintype "power_in"))
      (node (ref "LED50") (pin "VDD") (pinfunction "VCC_VDD") (pintype "power_in"))
      (node (ref "LED51") (pin "VDD") (pinfunction "VCC_VDD") (pintype "power_in"))
      (node (ref "LED52") (pin "VDD") (pinfunction "VCC_VDD") (pintype "power_in"))
      (node (ref "LED53") (pin "VDD") (pinfunction "VCC_VDD") (pintype "power_in"))
      (node (ref "LED54") (pin "VDD") (pinfunction "VCC_VDD") (pintype "power_in"))
      (node (ref "LED55") (pin "VDD") (pinfunction "VCC_VDD") (pintype "power_in"))
      (node (ref "LED56") (pin "VDD") (pinfunction "VCC_VDD") (pintype "power_in"))
      (node (ref "LED57") (pin "VDD") (pinfunction "VCC_VDD") (pintype "power_in"))
      (node (ref "LED58") (pin "VDD") (pinfunction "VCC_VDD") (pintype "power_in"))
      (node (ref "LED59") (pin "VDD") (pinfunction "VCC_VDD") (pintype "power_in"))
      (node (ref "LED6") (pin "VDD") (pinfunction "VCC_VDD") (pintype "power_in"))
      (node (ref "LED60") (pin "VDD") (pinfunction "VCC_VDD") (pintype "power_in"))
      (node (ref "LED7") (pin "VDD") (pinfunction "VCC_VDD") (pintype "power_in"))
      (node (ref "LED8") (pin "VDD") (pinfunction "VCC_VDD") (pintype "power_in"))
      (node (ref "LED9") (pin "VDD") (pinfunction "VCC_VDD") (pintype "power_in"))
      (node (ref "R285") (pin "P$1") (pinfunction "1_P$1") (pintype "passive"))
      (node (ref "R6") (pin "P$2") (pinfunction "2_P$2") (pintype "passive"))
      (node (ref "R7") (pin "P$2") (pinfunction "2_P$2") (pintype "passive"))
      (node (ref "R8") (pin "P$2") (pinfunction "2_P$2") (pintype "passive"))
      (node (ref "TP1") (pin "P$1") (pinfunction "P$1_P$1") (pintype "bidirectional"))
      (node (ref "X2") (pin "1") (pinfunction "1_1") (pintype "passive"))
      (node (ref "X2") (pin "2") (pinfunction "2_2") (pintype "passive"))
    )
    (net (code "177") (name "unconnected-(IC2-(AIN0{slash}ADC5{slash}PCINT6)PA6-Pad10)") (class "Default")
      (node (ref "IC2") (pin "10") (pinfunction "(AIN0/ADC5/PCINT6)PA6_10") (pintype "bidirectional"))
    )
    (net (code "178") (name "unconnected-(IC2-(AIN1{slash}ADC6{slash}PCINT7)PA7-Pad9)") (class "Default")
      (node (ref "IC2") (pin "9") (pinfunction "(AIN1/ADC6/PCINT7)PA7_9") (pintype "bidirectional"))
    )
    (net (code "179") (name "unconnected-(IC2-(AIN2{slash}ADC4{slash}PCINT5)PA5-Pad11)") (class "Default")
      (node (ref "IC2") (pin "11") (pinfunction "(AIN2/ADC4/PCINT5)PA5_11") (pintype "bidirectional"))
    )
    (net (code "180") (name "unconnected-(IC2-(ICP0{slash}ADC3{slash}PCINT4)PA4-Pad12)") (class "Default")
      (node (ref "IC2") (pin "12") (pinfunction "(ICP0/ADC3/PCINT4)PA4_12") (pintype "bidirectional"))
    )
  )
)
